# SCH_wordclocksmall_2023-02-03.net
KiCad netlist of a schematic drawn in EasyEDA
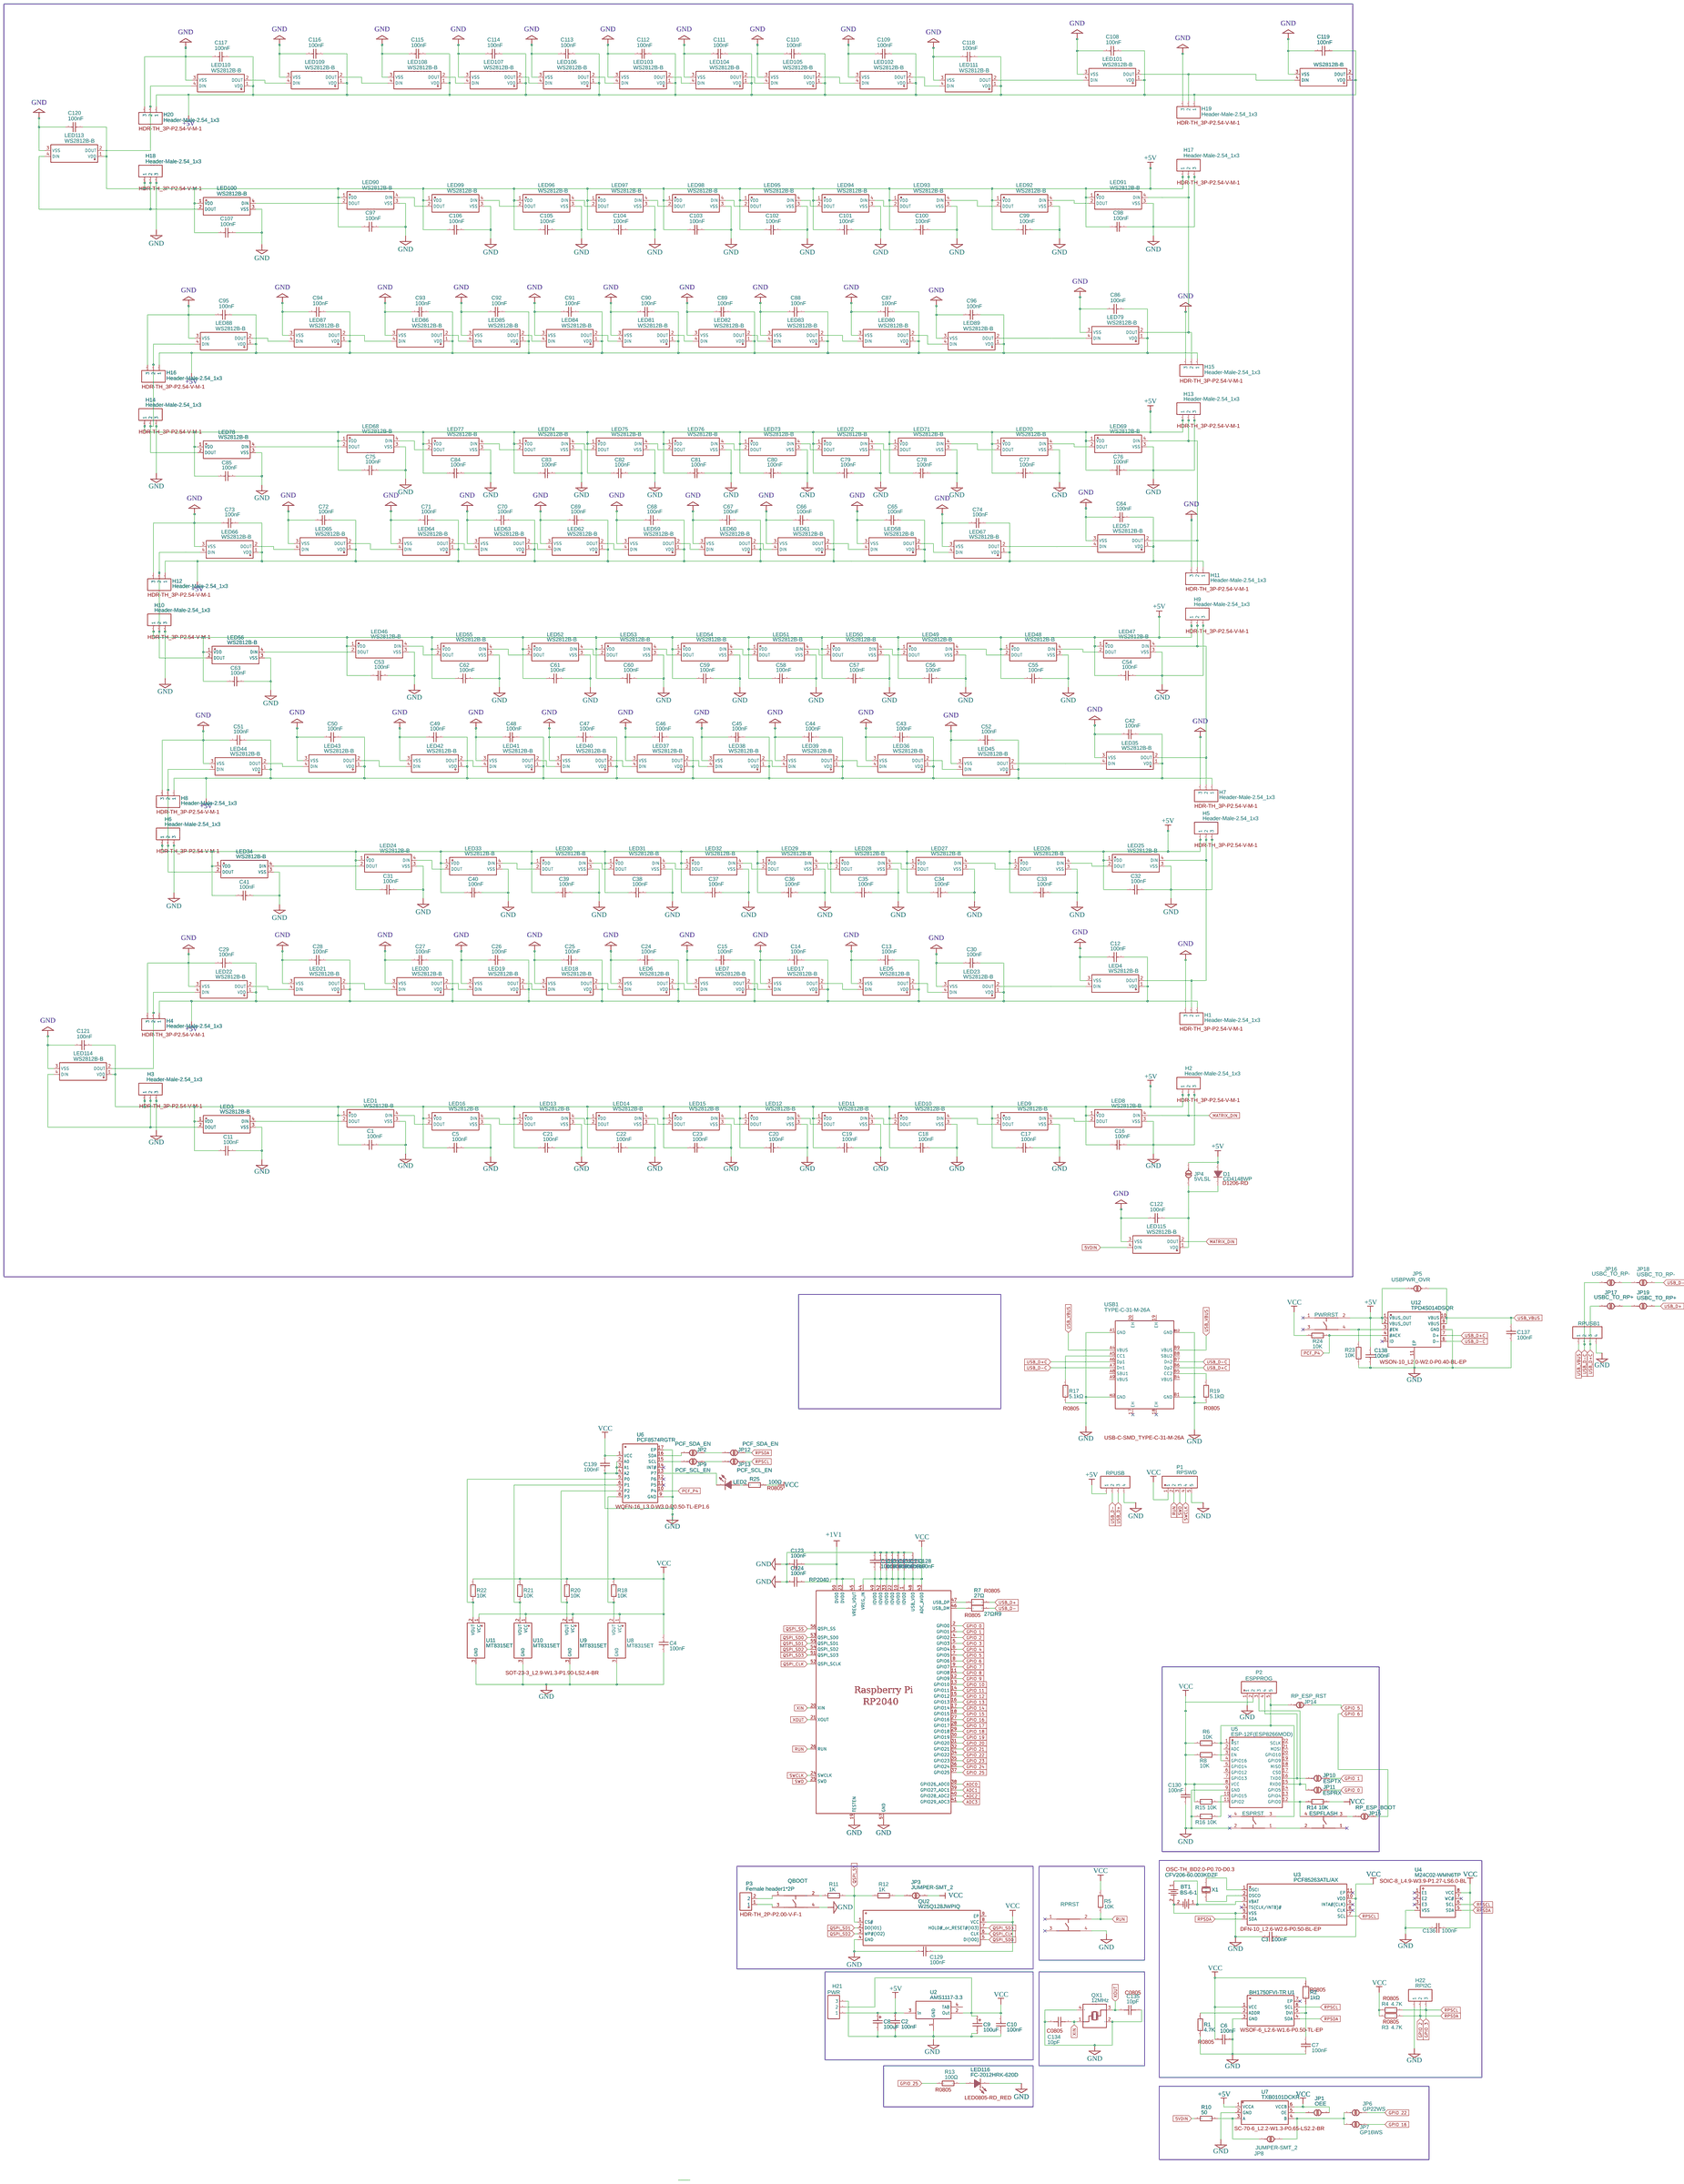
[diagram p0: schematic sheet]

(export (version "E")
  (design (tool "Eeschema 10.0.6"))
  (components
    (comp (ref "BT1")
      (value "BS-6-1")
      (fields (field (name "BOM_Supplier Part") "C969909"))
      (libsource (lib "") (part "BS-6-1_1"))
    )
    (comp (ref "BT2")
      (value "BS-6-1")
      (fields (field (name "BOM_Supplier Part") "C969909"))
      (libsource (lib "") (part "BS-6-1"))
    )
    (comp (ref "C1")
      (value "100nF")
      (fields
        (field (name "BOM_Manufacturer Part") "CC0805KRX7R9BB104")
        (field (name "BOM_Supplier Part") "C49678")
      )
      (libsource (lib "") (part "CC0805KRX7R9BB104_1"))
    )
    (comp (ref "C2")
      (value "100nF")
      (fields
        (field (name "BOM_Manufacturer Part") "CC0805KRX7R9BB104")
        (field (name "BOM_Supplier Part") "C49678")
      )
      (libsource (lib "") (part "CC0805KRX7R9BB104_3"))
    )
    (comp (ref "C3")
      (value "100nF")
      (fields
        (field (name "BOM_Manufacturer Part") "CC0805KRX7R9BB104")
        (field (name "BOM_Supplier Part") "C49678")
      )
      (libsource (lib "") (part "CC0805KRX7R9BB104"))
    )
    (comp (ref "C4")
      (value "100nF")
      (fields
        (field (name "BOM_Manufacturer Part") "CC0805KRX7R9BB104")
        (field (name "BOM_Supplier Part") "C49678")
      )
      (libsource (lib "") (part "CC0805KRX7R9BB104_2"))
    )
    (comp (ref "C5")
      (value "100nF")
      (fields
        (field (name "BOM_Manufacturer Part") "CC0805KRX7R9BB104")
        (field (name "BOM_Supplier Part") "C49678")
      )
      (libsource (lib "") (part "CC0805KRX7R9BB104_1"))
    )
    (comp (ref "C6")
      (value "100nF")
      (fields
        (field (name "BOM_Manufacturer Part") "CC0805KRX7R9BB104")
        (field (name "BOM_Supplier Part") "C49678")
      )
      (libsource (lib "") (part "CC0805KRX7R9BB104"))
    )
    (comp (ref "C7")
      (value "100nF")
      (fields
        (field (name "BOM_Manufacturer Part") "CC0805KRX7R9BB104")
        (field (name "BOM_Supplier Part") "C49678")
      )
      (libsource (lib "") (part "CC0805KRX7R9BB104_2"))
    )
    (comp (ref "C8")
      (value "100uF")
      (fields
        (field (name "BOM_Manufacturer Part") "TAJB107K006RNJ")
        (field (name "BOM_Supplier Part") "C16133")
      )
      (libsource (lib "") (part "TAJB107K006RNJ"))
    )
    (comp (ref "C9")
      (value "100uF")
      (fields
        (field (name "BOM_Manufacturer Part") "TAJB107K006RNJ")
        (field (name "BOM_Supplier Part") "C16133")
      )
      (libsource (lib "") (part "TAJB107K006RNJ"))
    )
    (comp (ref "C10")
      (value "100nF")
      (fields
        (field (name "BOM_Manufacturer Part") "CC0805KRX7R9BB104")
        (field (name "BOM_Supplier Part") "C49678")
      )
      (libsource (lib "") (part "CC0805KRX7R9BB104_3"))
    )
    (comp (ref "C11")
      (value "100nF")
      (fields
        (field (name "BOM_Manufacturer Part") "CC0805KRX7R9BB104")
        (field (name "BOM_Supplier Part") "C49678")
      )
      (libsource (lib "") (part "CC0805KRX7R9BB104_1"))
    )
    (comp (ref "C12")
      (value "100nF")
      (fields
        (field (name "BOM_Manufacturer Part") "CC0805KRX7R9BB104")
        (field (name "BOM_Supplier Part") "C49678")
      )
      (libsource (lib "") (part "CC0805KRX7R9BB104"))
    )
    (comp (ref "C13")
      (value "100nF")
      (fields
        (field (name "BOM_Manufacturer Part") "CC0805KRX7R9BB104")
        (field (name "BOM_Supplier Part") "C49678")
      )
      (libsource (lib "") (part "CC0805KRX7R9BB104"))
    )
    (comp (ref "C14")
      (value "100nF")
      (fields
        (field (name "BOM_Manufacturer Part") "CC0805KRX7R9BB104")
        (field (name "BOM_Supplier Part") "C49678")
      )
      (libsource (lib "") (part "CC0805KRX7R9BB104"))
    )
    (comp (ref "C15")
      (value "100nF")
      (fields
        (field (name "BOM_Manufacturer Part") "CC0805KRX7R9BB104")
        (field (name "BOM_Supplier Part") "C49678")
      )
      (libsource (lib "") (part "CC0805KRX7R9BB104"))
    )
    (comp (ref "C16")
      (value "100nF")
      (fields
        (field (name "BOM_Manufacturer Part") "CC0805KRX7R9BB104")
        (field (name "BOM_Supplier Part") "C49678")
      )
      (libsource (lib "") (part "CC0805KRX7R9BB104_1"))
    )
    (comp (ref "C17")
      (value "100nF")
      (fields
        (field (name "BOM_Manufacturer Part") "CC0805KRX7R9BB104")
        (field (name "BOM_Supplier Part") "C49678")
      )
      (libsource (lib "") (part "CC0805KRX7R9BB104_1"))
    )
    (comp (ref "C18")
      (value "100nF")
      (fields
        (field (name "BOM_Manufacturer Part") "CC0805KRX7R9BB104")
        (field (name "BOM_Supplier Part") "C49678")
      )
      (libsource (lib "") (part "CC0805KRX7R9BB104_1"))
    )
    (comp (ref "C19")
      (value "100nF")
      (fields
        (field (name "BOM_Manufacturer Part") "CC0805KRX7R9BB104")
        (field (name "BOM_Supplier Part") "C49678")
      )
      (libsource (lib "") (part "CC0805KRX7R9BB104_1"))
    )
    (comp (ref "C20")
      (value "100nF")
      (fields
        (field (name "BOM_Manufacturer Part") "CC0805KRX7R9BB104")
        (field (name "BOM_Supplier Part") "C49678")
      )
      (libsource (lib "") (part "CC0805KRX7R9BB104_1"))
    )
    (comp (ref "C21")
      (value "100nF")
      (fields
        (field (name "BOM_Manufacturer Part") "CC0805KRX7R9BB104")
        (field (name "BOM_Supplier Part") "C49678")
      )
      (libsource (lib "") (part "CC0805KRX7R9BB104_1"))
    )
    (comp (ref "C22")
      (value "100nF")
      (fields
        (field (name "BOM_Manufacturer Part") "CC0805KRX7R9BB104")
        (field (name "BOM_Supplier Part") "C49678")
      )
      (libsource (lib "") (part "CC0805KRX7R9BB104_1"))
    )
    (comp (ref "C23")
      (value "100nF")
      (fields
        (field (name "BOM_Manufacturer Part") "CC0805KRX7R9BB104")
        (field (name "BOM_Supplier Part") "C49678")
      )
      (libsource (lib "") (part "CC0805KRX7R9BB104_1"))
    )
    (comp (ref "C24")
      (value "100nF")
      (fields
        (field (name "BOM_Manufacturer Part") "CC0805KRX7R9BB104")
        (field (name "BOM_Supplier Part") "C49678")
      )
      (libsource (lib "") (part "CC0805KRX7R9BB104"))
    )
    (comp (ref "C25")
      (value "100nF")
      (fields
        (field (name "BOM_Manufacturer Part") "CC0805KRX7R9BB104")
        (field (name "BOM_Supplier Part") "C49678")
      )
      (libsource (lib "") (part "CC0805KRX7R9BB104"))
    )
    (comp (ref "C26")
      (value "100nF")
      (fields
        (field (name "BOM_Manufacturer Part") "CC0805KRX7R9BB104")
        (field (name "BOM_Supplier Part") "C49678")
      )
      (libsource (lib "") (part "CC0805KRX7R9BB104"))
    )
    (comp (ref "C27")
      (value "100nF")
      (fields
        (field (name "BOM_Manufacturer Part") "CC0805KRX7R9BB104")
        (field (name "BOM_Supplier Part") "C49678")
      )
      (libsource (lib "") (part "CC0805KRX7R9BB104"))
    )
    (comp (ref "C28")
      (value "100nF")
      (fields
        (field (name "BOM_Manufacturer Part") "CC0805KRX7R9BB104")
        (field (name "BOM_Supplier Part") "C49678")
      )
      (libsource (lib "") (part "CC0805KRX7R9BB104"))
    )
    (comp (ref "C29")
      (value "100nF")
      (fields
        (field (name "BOM_Manufacturer Part") "CC0805KRX7R9BB104")
        (field (name "BOM_Supplier Part") "C49678")
      )
      (libsource (lib "") (part "CC0805KRX7R9BB104"))
    )
    (comp (ref "C30")
      (value "100nF")
      (fields
        (field (name "BOM_Manufacturer Part") "CC0805KRX7R9BB104")
        (field (name "BOM_Supplier Part") "C49678")
      )
      (libsource (lib "") (part "CC0805KRX7R9BB104"))
    )
    (comp (ref "C31")
      (value "100nF")
      (fields
        (field (name "BOM_Manufacturer Part") "CC0805KRX7R9BB104")
        (field (name "BOM_Supplier Part") "C49678")
      )
      (libsource (lib "") (part "CC0805KRX7R9BB104_1"))
    )
    (comp (ref "C32")
      (value "100nF")
      (fields
        (field (name "BOM_Manufacturer Part") "CC0805KRX7R9BB104")
        (field (name "BOM_Supplier Part") "C49678")
      )
      (libsource (lib "") (part "CC0805KRX7R9BB104_1"))
    )
    (comp (ref "C33")
      (value "100nF")
      (fields
        (field (name "BOM_Manufacturer Part") "CC0805KRX7R9BB104")
        (field (name "BOM_Supplier Part") "C49678")
      )
      (libsource (lib "") (part "CC0805KRX7R9BB104_1"))
    )
    (comp (ref "C34")
      (value "100nF")
      (fields
        (field (name "BOM_Manufacturer Part") "CC0805KRX7R9BB104")
        (field (name "BOM_Supplier Part") "C49678")
      )
      (libsource (lib "") (part "CC0805KRX7R9BB104_1"))
    )
    (comp (ref "C35")
      (value "100nF")
      (fields
        (field (name "BOM_Manufacturer Part") "CC0805KRX7R9BB104")
        (field (name "BOM_Supplier Part") "C49678")
      )
      (libsource (lib "") (part "CC0805KRX7R9BB104_1"))
    )
    (comp (ref "C36")
      (value "100nF")
      (fields
        (field (name "BOM_Manufacturer Part") "CC0805KRX7R9BB104")
        (field (name "BOM_Supplier Part") "C49678")
      )
      (libsource (lib "") (part "CC0805KRX7R9BB104_1"))
    )
    (comp (ref "C37")
      (value "100nF")
      (fields
        (field (name "BOM_Manufacturer Part") "CC0805KRX7R9BB104")
        (field (name "BOM_Supplier Part") "C49678")
      )
      (libsource (lib "") (part "CC0805KRX7R9BB104_1"))
    )
    (comp (ref "C38")
      (value "100nF")
      (fields
        (field (name "BOM_Manufacturer Part") "CC0805KRX7R9BB104")
        (field (name "BOM_Supplier Part") "C49678")
      )
      (libsource (lib "") (part "CC0805KRX7R9BB104_1"))
    )
    (comp (ref "C39")
      (value "100nF")
      (fields
        (field (name "BOM_Manufacturer Part") "CC0805KRX7R9BB104")
        (field (name "BOM_Supplier Part") "C49678")
      )
      (libsource (lib "") (part "CC0805KRX7R9BB104_1"))
    )
    (comp (ref "C40")
      (value "100nF")
      (fields
        (field (name "BOM_Manufacturer Part") "CC0805KRX7R9BB104")
        (field (name "BOM_Supplier Part") "C49678")
      )
      (libsource (lib "") (part "CC0805KRX7R9BB104_1"))
    )
    (comp (ref "C41")
      (value "100nF")
      (fields
        (field (name "BOM_Manufacturer Part") "CC0805KRX7R9BB104")
        (field (name "BOM_Supplier Part") "C49678")
      )
      (libsource (lib "") (part "CC0805KRX7R9BB104_1"))
    )
    (comp (ref "C42")
      (value "100nF")
      (fields
        (field (name "BOM_Manufacturer Part") "CC0805KRX7R9BB104")
        (field (name "BOM_Supplier Part") "C49678")
      )
      (libsource (lib "") (part "CC0805KRX7R9BB104"))
    )
    (comp (ref "C43")
      (value "100nF")
      (fields
        (field (name "BOM_Manufacturer Part") "CC0805KRX7R9BB104")
        (field (name "BOM_Supplier Part") "C49678")
      )
      (libsource (lib "") (part "CC0805KRX7R9BB104"))
    )
    (comp (ref "C44")
      (value "100nF")
      (fields
        (field (name "BOM_Manufacturer Part") "CC0805KRX7R9BB104")
        (field (name "BOM_Supplier Part") "C49678")
      )
      (libsource (lib "") (part "CC0805KRX7R9BB104"))
    )
    (comp (ref "C45")
      (value "100nF")
      (fields
        (field (name "BOM_Manufacturer Part") "CC0805KRX7R9BB104")
        (field (name "BOM_Supplier Part") "C49678")
      )
      (libsource (lib "") (part "CC0805KRX7R9BB104"))
    )
    (comp (ref "C46")
      (value "100nF")
      (fields
        (field (name "BOM_Manufacturer Part") "CC0805KRX7R9BB104")
        (field (name "BOM_Supplier Part") "C49678")
      )
      (libsource (lib "") (part "CC0805KRX7R9BB104"))
    )
    (comp (ref "C47")
      (value "100nF")
      (fields
        (field (name "BOM_Manufacturer Part") "CC0805KRX7R9BB104")
        (field (name "BOM_Supplier Part") "C49678")
      )
      (libsource (lib "") (part "CC0805KRX7R9BB104"))
    )
    (comp (ref "C48")
      (value "100nF")
      (fields
        (field (name "BOM_Manufacturer Part") "CC0805KRX7R9BB104")
        (field (name "BOM_Supplier Part") "C49678")
      )
      (libsource (lib "") (part "CC0805KRX7R9BB104"))
    )
    (comp (ref "C49")
      (value "100nF")
      (fields
        (field (name "BOM_Manufacturer Part") "CC0805KRX7R9BB104")
        (field (name "BOM_Supplier Part") "C49678")
      )
      (libsource (lib "") (part "CC0805KRX7R9BB104"))
    )
    (comp (ref "C50")
      (value "100nF")
      (fields
        (field (name "BOM_Manufacturer Part") "CC0805KRX7R9BB104")
        (field (name "BOM_Supplier Part") "C49678")
      )
      (libsource (lib "") (part "CC0805KRX7R9BB104"))
    )
    (comp (ref "C51")
      (value "100nF")
      (fields
        (field (name "BOM_Manufacturer Part") "CC0805KRX7R9BB104")
        (field (name "BOM_Supplier Part") "C49678")
      )
      (libsource (lib "") (part "CC0805KRX7R9BB104"))
    )
    (comp (ref "C52")
      (value "100nF")
      (fields
        (field (name "BOM_Manufacturer Part") "CC0805KRX7R9BB104")
        (field (name "BOM_Supplier Part") "C49678")
      )
      (libsource (lib "") (part "CC0805KRX7R9BB104"))
    )
    (comp (ref "C53")
      (value "100nF")
      (fields
        (field (name "BOM_Manufacturer Part") "CC0805KRX7R9BB104")
        (field (name "BOM_Supplier Part") "C49678")
      )
      (libsource (lib "") (part "CC0805KRX7R9BB104_1"))
    )
    (comp (ref "C54")
      (value "100nF")
      (fields
        (field (name "BOM_Manufacturer Part") "CC0805KRX7R9BB104")
        (field (name "BOM_Supplier Part") "C49678")
      )
      (libsource (lib "") (part "CC0805KRX7R9BB104_1"))
    )
    (comp (ref "C55")
      (value "100nF")
      (fields
        (field (name "BOM_Manufacturer Part") "CC0805KRX7R9BB104")
        (field (name "BOM_Supplier Part") "C49678")
      )
      (libsource (lib "") (part "CC0805KRX7R9BB104_1"))
    )
    (comp (ref "C56")
      (value "100nF")
      (fields
        (field (name "BOM_Manufacturer Part") "CC0805KRX7R9BB104")
        (field (name "BOM_Supplier Part") "C49678")
      )
      (libsource (lib "") (part "CC0805KRX7R9BB104_1"))
    )
    (comp (ref "C57")
      (value "100nF")
      (fields
        (field (name "BOM_Manufacturer Part") "CC0805KRX7R9BB104")
        (field (name "BOM_Supplier Part") "C49678")
      )
      (libsource (lib "") (part "CC0805KRX7R9BB104_1"))
    )
    (comp (ref "C58")
      (value "100nF")
      (fields
        (field (name "BOM_Manufacturer Part") "CC0805KRX7R9BB104")
        (field (name "BOM_Supplier Part") "C49678")
      )
      (libsource (lib "") (part "CC0805KRX7R9BB104_1"))
    )
    (comp (ref "C59")
      (value "100nF")
      (fields
        (field (name "BOM_Manufacturer Part") "CC0805KRX7R9BB104")
        (field (name "BOM_Supplier Part") "C49678")
      )
      (libsource (lib "") (part "CC0805KRX7R9BB104_1"))
    )
    (comp (ref "C60")
      (value "100nF")
      (fields
        (field (name "BOM_Manufacturer Part") "CC0805KRX7R9BB104")
        (field (name "BOM_Supplier Part") "C49678")
      )
      (libsource (lib "") (part "CC0805KRX7R9BB104_1"))
    )
    (comp (ref "C61")
      (value "100nF")
      (fields
        (field (name "BOM_Manufacturer Part") "CC0805KRX7R9BB104")
        (field (name "BOM_Supplier Part") "C49678")
      )
      (libsource (lib "") (part "CC0805KRX7R9BB104_1"))
    )
    (comp (ref "C62")
      (value "100nF")
      (fields
        (field (name "BOM_Manufacturer Part") "CC0805KRX7R9BB104")
        (field (name "BOM_Supplier Part") "C49678")
      )
      (libsource (lib "") (part "CC0805KRX7R9BB104_1"))
    )
    (comp (ref "C63")
      (value "100nF")
      (fields
        (field (name "BOM_Manufacturer Part") "CC0805KRX7R9BB104")
        (field (name "BOM_Supplier Part") "C49678")
      )
      (libsource (lib "") (part "CC0805KRX7R9BB104_1"))
    )
    (comp (ref "C64")
      (value "100nF")
      (fields
        (field (name "BOM_Manufacturer Part") "CC0805KRX7R9BB104")
        (field (name "BOM_Supplier Part") "C49678")
      )
      (libsource (lib "") (part "CC0805KRX7R9BB104"))
    )
    (comp (ref "C65")
      (value "100nF")
      (fields
        (field (name "BOM_Manufacturer Part") "CC0805KRX7R9BB104")
        (field (name "BOM_Supplier Part") "C49678")
      )
      (libsource (lib "") (part "CC0805KRX7R9BB104"))
    )
    (comp (ref "C66")
      (value "100nF")
      (fields
        (field (name "BOM_Manufacturer Part") "CC0805KRX7R9BB104")
        (field (name "BOM_Supplier Part") "C49678")
      )
      (libsource (lib "") (part "CC0805KRX7R9BB104"))
    )
    (comp (ref "C67")
      (value "100nF")
      (fields
        (field (name "BOM_Manufacturer Part") "CC0805KRX7R9BB104")
        (field (name "BOM_Supplier Part") "C49678")
      )
      (libsource (lib "") (part "CC0805KRX7R9BB104"))
    )
    (comp (ref "C68")
      (value "100nF")
      (fields
        (field (name "BOM_Manufacturer Part") "CC0805KRX7R9BB104")
        (field (name "BOM_Supplier Part") "C49678")
      )
      (libsource (lib "") (part "CC0805KRX7R9BB104"))
    )
    (comp (ref "C69")
      (value "100nF")
      (fields
        (field (name "BOM_Manufacturer Part") "CC0805KRX7R9BB104")
        (field (name "BOM_Supplier Part") "C49678")
      )
      (libsource (lib "") (part "CC0805KRX7R9BB104"))
    )
    (comp (ref "C70")
      (value "100nF")
      (fields
        (field (name "BOM_Manufacturer Part") "CC0805KRX7R9BB104")
        (field (name "BOM_Supplier Part") "C49678")
      )
      (libsource (lib "") (part "CC0805KRX7R9BB104"))
    )
    (comp (ref "C71")
      (value "100nF")
      (fields
        (field (name "BOM_Manufacturer Part") "CC0805KRX7R9BB104")
        (field (name "BOM_Supplier Part") "C49678")
      )
      (libsource (lib "") (part "CC0805KRX7R9BB104"))
    )
    (comp (ref "C72")
      (value "100nF")
      (fields
        (field (name "BOM_Manufacturer Part") "CC0805KRX7R9BB104")
        (field (name "BOM_Supplier Part") "C49678")
      )
      (libsource (lib "") (part "CC0805KRX7R9BB104"))
    )
    (comp (ref "C73")
      (value "100nF")
      (fields
        (field (name "BOM_Manufacturer Part") "CC0805KRX7R9BB104")
        (field (name "BOM_Supplier Part") "C49678")
      )
      (libsource (lib "") (part "CC0805KRX7R9BB104"))
    )
    (comp (ref "C74")
      (value "100nF")
      (fields
        (field (name "BOM_Manufacturer Part") "CC0805KRX7R9BB104")
        (field (name "BOM_Supplier Part") "C49678")
      )
      (libsource (lib "") (part "CC0805KRX7R9BB104"))
    )
    (comp (ref "C75")
      (value "100nF")
      (fields
        (field (name "BOM_Manufacturer Part") "CC0805KRX7R9BB104")
        (field (name "BOM_Supplier Part") "C49678")
      )
      (libsource (lib "") (part "CC0805KRX7R9BB104_1"))
    )
    (comp (ref "C76")
      (value "100nF")
      (fields
        (field (name "BOM_Manufacturer Part") "CC0805KRX7R9BB104")
        (field (name "BOM_Supplier Part") "C49678")
      )
      (libsource (lib "") (part "CC0805KRX7R9BB104_1"))
    )
    (comp (ref "C77")
      (value "100nF")
      (fields
        (field (name "BOM_Manufacturer Part") "CC0805KRX7R9BB104")
        (field (name "BOM_Supplier Part") "C49678")
      )
      (libsource (lib "") (part "CC0805KRX7R9BB104_1"))
    )
    (comp (ref "C78")
      (value "100nF")
      (fields
        (field (name "BOM_Manufacturer Part") "CC0805KRX7R9BB104")
        (field (name "BOM_Supplier Part") "C49678")
      )
      (libsource (lib "") (part "CC0805KRX7R9BB104_1"))
    )
    (comp (ref "C79")
      (value "100nF")
      (fields
        (field (name "BOM_Manufacturer Part") "CC0805KRX7R9BB104")
        (field (name "BOM_Supplier Part") "C49678")
      )
      (libsource (lib "") (part "CC0805KRX7R9BB104_1"))
    )
    (comp (ref "C80")
      (value "100nF")
      (fields
        (field (name "BOM_Manufacturer Part") "CC0805KRX7R9BB104")
        (field (name "BOM_Supplier Part") "C49678")
      )
      (libsource (lib "") (part "CC0805KRX7R9BB104_1"))
    )
    (comp (ref "C81")
      (value "100nF")
      (fields
        (field (name "BOM_Manufacturer Part") "CC0805KRX7R9BB104")
        (field (name "BOM_Supplier Part") "C49678")
      )
      (libsource (lib "") (part "CC0805KRX7R9BB104_1"))
    )
    (comp (ref "C82")
      (value "100nF")
      (fields
        (field (name "BOM_Manufacturer Part") "CC0805KRX7R9BB104")
        (field (name "BOM_Supplier Part") "C49678")
      )
      (libsource (lib "") (part "CC0805KRX7R9BB104_1"))
    )
    (comp (ref "C83")
      (value "100nF")
      (fields
        (field (name "BOM_Manufacturer Part") "CC0805KRX7R9BB104")
        (field (name "BOM_Supplier Part") "C49678")
      )
      (libsource (lib "") (part "CC0805KRX7R9BB104_1"))
    )
    (comp (ref "C84")
      (value "100nF")
      (fields
        (field (name "BOM_Manufacturer Part") "CC0805KRX7R9BB104")
        (field (name "BOM_Supplier Part") "C49678")
      )
      (libsource (lib "") (part "CC0805KRX7R9BB104_1"))
    )
    (comp (ref "C85")
      (value "100nF")
      (fields
        (field (name "BOM_Manufacturer Part") "CC0805KRX7R9BB104")
        (field (name "BOM_Supplier Part") "C49678")
      )
      (libsource (lib "") (part "CC0805KRX7R9BB104_1"))
    )
    (comp (ref "C86")
      (value "100nF")
      (fields
        (field (name "BOM_Manufacturer Part") "CC0805KRX7R9BB104")
        (field (name "BOM_Supplier Part") "C49678")
      )
      (libsource (lib "") (part "CC0805KRX7R9BB104"))
    )
    (comp (ref "C87")
      (value "100nF")
      (fields
        (field (name "BOM_Manufacturer Part") "CC0805KRX7R9BB104")
        (field (name "BOM_Supplier Part") "C49678")
      )
      (libsource (lib "") (part "CC0805KRX7R9BB104"))
    )
    (comp (ref "C88")
      (value "100nF")
      (fields
        (field (name "BOM_Manufacturer Part") "CC0805KRX7R9BB104")
        (field (name "BOM_Supplier Part") "C49678")
      )
      (libsource (lib "") (part "CC0805KRX7R9BB104"))
    )
    (comp (ref "C89")
      (value "100nF")
      (fields
        (field (name "BOM_Manufacturer Part") "CC0805KRX7R9BB104")
        (field (name "BOM_Supplier Part") "C49678")
      )
      (libsource (lib "") (part "CC0805KRX7R9BB104"))
    )
    (comp (ref "C90")
      (value "100nF")
      (fields
        (field (name "BOM_Manufacturer Part") "CC0805KRX7R9BB104")
        (field (name "BOM_Supplier Part") "C49678")
      )
      (libsource (lib "") (part "CC0805KRX7R9BB104"))
    )
    (comp (ref "C91")
      (value "100nF")
      (fields
        (field (name "BOM_Manufacturer Part") "CC0805KRX7R9BB104")
        (field (name "BOM_Supplier Part") "C49678")
      )
      (libsource (lib "") (part "CC0805KRX7R9BB104"))
    )
    (comp (ref "C92")
      (value "100nF")
      (fields
        (field (name "BOM_Manufacturer Part") "CC0805KRX7R9BB104")
        (field (name "BOM_Supplier Part") "C49678")
      )
      (libsource (lib "") (part "CC0805KRX7R9BB104"))
    )
    (comp (ref "C93")
      (value "100nF")
      (fields
        (field (name "BOM_Manufacturer Part") "CC0805KRX7R9BB104")
        (field (name "BOM_Supplier Part") "C49678")
      )
      (libsource (lib "") (part "CC0805KRX7R9BB104"))
    )
    (comp (ref "C94")
      (value "100nF")
      (fields
        (field (name "BOM_Manufacturer Part") "CC0805KRX7R9BB104")
        (field (name "BOM_Supplier Part") "C49678")
      )
      (libsource (lib "") (part "CC0805KRX7R9BB104"))
    )
    (comp (ref "C95")
      (value "100nF")
      (fields
        (field (name "BOM_Manufacturer Part") "CC0805KRX7R9BB104")
        (field (name "BOM_Supplier Part") "C49678")
      )
      (libsource (lib "") (part "CC0805KRX7R9BB104"))
    )
    (comp (ref "C96")
      (value "100nF")
      (fields
        (field (name "BOM_Manufacturer Part") "CC0805KRX7R9BB104")
        (field (name "BOM_Supplier Part") "C49678")
      )
      (libsource (lib "") (part "CC0805KRX7R9BB104"))
    )
    (comp (ref "C97")
      (value "100nF")
      (fields
        (field (name "BOM_Manufacturer Part") "CC0805KRX7R9BB104")
        (field (name "BOM_Supplier Part") "C49678")
      )
      (libsource (lib "") (part "CC0805KRX7R9BB104_1"))
    )
    (comp (ref "C98")
      (value "100nF")
      (fields
        (field (name "BOM_Manufacturer Part") "CC0805KRX7R9BB104")
        (field (name "BOM_Supplier Part") "C49678")
      )
      (libsource (lib "") (part "CC0805KRX7R9BB104_1"))
    )
    (comp (ref "C99")
      (value "100nF")
      (fields
        (field (name "BOM_Manufacturer Part") "CC0805KRX7R9BB104")
        (field (name "BOM_Supplier Part") "C49678")
      )
      (libsource (lib "") (part "CC0805KRX7R9BB104_1"))
    )
    (comp (ref "C100")
      (value "100nF")
      (fields
        (field (name "BOM_Manufacturer Part") "CC0805KRX7R9BB104")
        (field (name "BOM_Supplier Part") "C49678")
      )
      (libsource (lib "") (part "CC0805KRX7R9BB104_1"))
    )
    (comp (ref "C101")
      (value "100nF")
      (fields
        (field (name "BOM_Manufacturer Part") "CC0805KRX7R9BB104")
        (field (name "BOM_Supplier Part") "C49678")
      )
      (libsource (lib "") (part "CC0805KRX7R9BB104_1"))
    )
    (comp (ref "C102")
      (value "100nF")
      (fields
        (field (name "BOM_Manufacturer Part") "CC0805KRX7R9BB104")
        (field (name "BOM_Supplier Part") "C49678")
      )
      (libsource (lib "") (part "CC0805KRX7R9BB104_1"))
    )
    (comp (ref "C103")
      (value "100nF")
      (fields
        (field (name "BOM_Manufacturer Part") "CC0805KRX7R9BB104")
        (field (name "BOM_Supplier Part") "C49678")
      )
      (libsource (lib "") (part "CC0805KRX7R9BB104_1"))
    )
    (comp (ref "C104")
      (value "100nF")
      (fields
        (field (name "BOM_Manufacturer Part") "CC0805KRX7R9BB104")
        (field (name "BOM_Supplier Part") "C49678")
      )
      (libsource (lib "") (part "CC0805KRX7R9BB104_1"))
    )
    (comp (ref "C105")
      (value "100nF")
      (fields
        (field (name "BOM_Manufacturer Part") "CC0805KRX7R9BB104")
        (field (name "BOM_Supplier Part") "C49678")
      )
      (libsource (lib "") (part "CC0805KRX7R9BB104_1"))
    )
    (comp (ref "C106")
      (value "100nF")
      (fields
        (field (name "BOM_Manufacturer Part") "CC0805KRX7R9BB104")
        (field (name "BOM_Supplier Part") "C49678")
      )
      (libsource (lib "") (part "CC0805KRX7R9BB104_1"))
    )
    (comp (ref "C107")
      (value "100nF")
      (fields
        (field (name "BOM_Manufacturer Part") "CC0805KRX7R9BB104")
        (field (name "BOM_Supplier Part") "C49678")
      )
      (libsource (lib "") (part "CC0805KRX7R9BB104_1"))
    )
    (comp (ref "C108")
      (value "100nF")
      (fields
        (field (name "BOM_Manufacturer Part") "CC0805KRX7R9BB104")
        (field (name "BOM_Supplier Part") "C49678")
      )
      (libsource (lib "") (part "CC0805KRX7R9BB104"))
    )
    (comp (ref "C109")
      (value "100nF")
      (fields
        (field (name "BOM_Manufacturer Part") "CC0805KRX7R9BB104")
        (field (name "BOM_Supplier Part") "C49678")
      )
      (libsource (lib "") (part "CC0805KRX7R9BB104"))
    )
    (comp (ref "C110")
      (value "100nF")
      (fields
        (field (name "BOM_Manufacturer Part") "CC0805KRX7R9BB104")
        (field (name "BOM_Supplier Part") "C49678")
      )
      (libsource (lib "") (part "CC0805KRX7R9BB104"))
    )
    (comp (ref "C111")
      (value "100nF")
      (fields
        (field (name "BOM_Manufacturer Part") "CC0805KRX7R9BB104")
        (field (name "BOM_Supplier Part") "C49678")
      )
      (libsource (lib "") (part "CC0805KRX7R9BB104"))
    )
    (comp (ref "C112")
      (value "100nF")
      (fields
        (field (name "BOM_Manufacturer Part") "CC0805KRX7R9BB104")
        (field (name "BOM_Supplier Part") "C49678")
      )
      (libsource (lib "") (part "CC0805KRX7R9BB104"))
    )
    (comp (ref "C113")
      (value "100nF")
      (fields
        (field (name "BOM_Manufacturer Part") "CC0805KRX7R9BB104")
        (field (name "BOM_Supplier Part") "C49678")
      )
      (libsource (lib "") (part "CC0805KRX7R9BB104"))
    )
    (comp (ref "C114")
      (value "100nF")
      (fields
        (field (name "BOM_Manufacturer Part") "CC0805KRX7R9BB104")
        (field (name "BOM_Supplier Part") "C49678")
      )
      (libsource (lib "") (part "CC0805KRX7R9BB104"))
    )
    (comp (ref "C115")
      (value "100nF")
      (fields
        (field (name "BOM_Manufacturer Part") "CC0805KRX7R9BB104")
        (field (name "BOM_Supplier Part") "C49678")
      )
      (libsource (lib "") (part "CC0805KRX7R9BB104"))
    )
    (comp (ref "C116")
      (value "100nF")
      (fields
        (field (name "BOM_Manufacturer Part") "CC0805KRX7R9BB104")
        (field (name "BOM_Supplier Part") "C49678")
      )
      (libsource (lib "") (part "CC0805KRX7R9BB104"))
    )
    (comp (ref "C117")
      (value "100nF")
      (fields
        (field (name "BOM_Manufacturer Part") "CC0805KRX7R9BB104")
        (field (name "BOM_Supplier Part") "C49678")
      )
      (libsource (lib "") (part "CC0805KRX7R9BB104"))
    )
    (comp (ref "C118")
      (value "100nF")
      (fields
        (field (name "BOM_Manufacturer Part") "CC0805KRX7R9BB104")
        (field (name "BOM_Supplier Part") "C49678")
      )
      (libsource (lib "") (part "CC0805KRX7R9BB104"))
    )
    (comp (ref "C119")
      (value "100nF")
      (fields
        (field (name "BOM_Manufacturer Part") "CC0805KRX7R9BB104")
        (field (name "BOM_Supplier Part") "C49678")
      )
      (libsource (lib "") (part "CC0805KRX7R9BB104"))
    )
    (comp (ref "C120")
      (value "100nF")
      (fields
        (field (name "BOM_Manufacturer Part") "CC0805KRX7R9BB104")
        (field (name "BOM_Supplier Part") "C49678")
      )
      (libsource (lib "") (part "CC0805KRX7R9BB104"))
    )
    (comp (ref "C121")
      (value "100nF")
      (fields
        (field (name "BOM_Manufacturer Part") "CC0805KRX7R9BB104")
        (field (name "BOM_Supplier Part") "C49678")
      )
      (libsource (lib "") (part "CC0805KRX7R9BB104"))
    )
    (comp (ref "C122")
      (value "100nF")
      (fields
        (field (name "BOM_Manufacturer Part") "CC0805KRX7R9BB104")
        (field (name "BOM_Supplier Part") "C49678")
      )
      (libsource (lib "") (part "CC0805KRX7R9BB104"))
    )
    (comp (ref "C123")
      (value "100nF")
      (fields
        (field (name "BOM_Manufacturer Part") "CC0805KRX7R9BB104")
        (field (name "BOM_Supplier Part") "C49678")
      )
      (libsource (lib "") (part "CC0805KRX7R9BB104"))
    )
    (comp (ref "C124")
      (value "100nF")
      (fields
        (field (name "BOM_Manufacturer Part") "CC0805KRX7R9BB104")
        (field (name "BOM_Supplier Part") "C49678")
      )
      (libsource (lib "") (part "CC0805KRX7R9BB104"))
    )
    (comp (ref "C125")
      (value "100nF")
      (fields
        (field (name "BOM_Manufacturer Part") "CC0805KRX7R9BB104")
        (field (name "BOM_Supplier Part") "C49678")
      )
      (libsource (lib "") (part "CC0805KRX7R9BB104_2"))
    )
    (comp (ref "C126")
      (value "100nF")
      (fields
        (field (name "BOM_Manufacturer Part") "CC0805KRX7R9BB104")
        (field (name "BOM_Supplier Part") "C49678")
      )
      (libsource (lib "") (part "CC0805KRX7R9BB104_2"))
    )
    (comp (ref "C127")
      (value "100nF")
      (fields
        (field (name "BOM_Manufacturer Part") "CC0805KRX7R9BB104")
        (field (name "BOM_Supplier Part") "C49678")
      )
      (libsource (lib "") (part "CC0805KRX7R9BB104_2"))
    )
    (comp (ref "C128")
      (value "100nF")
      (fields
        (field (name "BOM_Manufacturer Part") "CC0805KRX7R9BB104")
        (field (name "BOM_Supplier Part") "C49678")
      )
      (libsource (lib "") (part "CC0805KRX7R9BB104_2"))
    )
    (comp (ref "C129")
      (value "100nF")
      (fields
        (field (name "BOM_Manufacturer Part") "CC0805KRX7R9BB104")
        (field (name "BOM_Supplier Part") "C49678")
      )
      (libsource (lib "") (part "CC0805KRX7R9BB104"))
    )
    (comp (ref "C130")
      (value "100nF")
      (fields
        (field (name "BOM_Manufacturer Part") "CC0805KRX7R9BB104")
        (field (name "BOM_Supplier Part") "C49678")
      )
      (libsource (lib "") (part "CC0805KRX7R9BB104_2"))
    )
    (comp (ref "C131")
      (value "100nF")
      (fields
        (field (name "BOM_Manufacturer Part") "CC0805KRX7R9BB104")
        (field (name "BOM_Supplier Part") "C49678")
      )
      (libsource (lib "") (part "CC0805KRX7R9BB104_2"))
    )
    (comp (ref "C132")
      (value "100nF")
      (fields
        (field (name "BOM_Manufacturer Part") "CC0805KRX7R9BB104")
        (field (name "BOM_Supplier Part") "C49678")
      )
      (libsource (lib "") (part "CC0805KRX7R9BB104_2"))
    )
    (comp (ref "C133")
      (value "100nF")
      (fields
        (field (name "BOM_Manufacturer Part") "CC0805KRX7R9BB104")
        (field (name "BOM_Supplier Part") "C49678")
      )
      (libsource (lib "") (part "CC0805KRX7R9BB104_2"))
    )
    (comp (ref "C134")
      (value "10pF")
      (fields
        (field (name "BOM_Manufacturer Part") "CL21C100JBANNNC")
        (field (name "BOM_Supplier Part") "C1785")
      )
      (libsource (lib "") (part "CC0805JRNPOYBN100_1"))
    )
    (comp (ref "C135")
      (value "10pF")
      (fields
        (field (name "BOM_Manufacturer Part") "CL21C100JBANNNC")
        (field (name "BOM_Supplier Part") "C1785")
      )
      (libsource (lib "") (part "CC0805JRNPOYBN100"))
    )
    (comp (ref "C136")
      (value "100nF")
      (fields
        (field (name "BOM_Manufacturer Part") "CC0805KRX7R9BB104")
        (field (name "BOM_Supplier Part") "C49678")
      )
      (libsource (lib "") (part "CC0805KRX7R9BB104"))
    )
    (comp (ref "C137")
      (value "100nF")
      (fields
        (field (name "BOM_Manufacturer Part") "CC0805KRX7R9BB104")
        (field (name "BOM_Supplier Part") "C49678")
      )
      (libsource (lib "") (part "CC0805KRX7R9BB104_2"))
    )
    (comp (ref "C138")
      (value "100nF")
      (fields
        (field (name "BOM_Manufacturer Part") "CC0805KRX7R9BB104")
        (field (name "BOM_Supplier Part") "C49678")
      )
      (libsource (lib "") (part "CC0805KRX7R9BB104_2"))
    )
    (comp (ref "C139")
      (value "100nF")
      (fields
        (field (name "BOM_Manufacturer Part") "CC0805KRX7R9BB104")
        (field (name "BOM_Supplier Part") "C49678")
      )
      (libsource (lib "") (part "CC0805KRX7R9BB104_3"))
    )
    (comp (ref "D1")
      (value "CD4148WP")
      (fields (field (name "BOM_Supplier Part") "C109000"))
      (libsource (lib "") (part "CD4148WP"))
    )
    (comp (ref "ESPFLASH")
      (value "PTS810SJM250SMTRLFS")
      (fields (field (name "BOM_Supplier Part") "C116501"))
      (libsource (lib "") (part "PTS810SJM250SMTRLFS_1"))
    )
    (comp (ref "ESPRST")
      (value "PTS810SJM250SMTRLFS")
      (fields (field (name "BOM_Supplier Part") "C116501"))
      (libsource (lib "") (part "PTS810SJM250SMTRLFS"))
    )
    (comp (ref "H1")
      (value "Header-Male-2.54_1x3")
      (fields
        (field (name "BOM_Manufacturer Part") "Header2.54mm 1*3P")
        (field (name "BOM_Supplier Part") "C49257")
      )
      (libsource (lib "") (part "Header-Male-2.54_1x3_8"))
    )
    (comp (ref "H2")
      (value "Header-Male-2.54_1x3")
      (fields
        (field (name "BOM_Manufacturer Part") "Header2.54mm 1*3P")
        (field (name "BOM_Supplier Part") "C49257")
      )
      (libsource (lib "") (part "Header-Male-2.54_1x3_6"))
    )
    (comp (ref "H3")
      (value "Header-Male-2.54_1x3")
      (fields
        (field (name "BOM_Manufacturer Part") "Header2.54mm 1*3P")
        (field (name "BOM_Supplier Part") "C49257")
      )
      (libsource (lib "") (part "Header-Male-2.54_1x3_7"))
    )
    (comp (ref "H4")
      (value "Header-Male-2.54_1x3")
      (fields
        (field (name "BOM_Manufacturer Part") "Header2.54mm 1*3P")
        (field (name "BOM_Supplier Part") "C49257")
      )
      (libsource (lib "") (part "Header-Male-2.54_1x3_8"))
    )
    (comp (ref "H5")
      (value "Header-Male-2.54_1x3")
      (fields
        (field (name "BOM_Manufacturer Part") "Header2.54mm 1*3P")
        (field (name "BOM_Supplier Part") "C49257")
      )
      (libsource (lib "") (part "Header-Male-2.54_1x3_1"))
    )
    (comp (ref "H6")
      (value "Header-Male-2.54_1x3")
      (fields
        (field (name "BOM_Manufacturer Part") "Header2.54mm 1*3P")
        (field (name "BOM_Supplier Part") "C49257")
      )
      (libsource (lib "") (part "Header-Male-2.54_1x3_1"))
    )
    (comp (ref "H7")
      (value "Header-Male-2.54_1x3")
      (fields
        (field (name "BOM_Manufacturer Part") "Header2.54mm 1*3P")
        (field (name "BOM_Supplier Part") "C49257")
      )
      (libsource (lib "") (part "Header-Male-2.54_1x3"))
    )
    (comp (ref "H8")
      (value "Header-Male-2.54_1x3")
      (fields
        (field (name "BOM_Manufacturer Part") "Header2.54mm 1*3P")
        (field (name "BOM_Supplier Part") "C49257")
      )
      (libsource (lib "") (part "Header-Male-2.54_1x3"))
    )
    (comp (ref "H9")
      (value "Header-Male-2.54_1x3")
      (fields
        (field (name "BOM_Manufacturer Part") "Header2.54mm 1*3P")
        (field (name "BOM_Supplier Part") "C49257")
      )
      (libsource (lib "") (part "Header-Male-2.54_1x3_4"))
    )
    (comp (ref "H10")
      (value "Header-Male-2.54_1x3")
      (fields
        (field (name "BOM_Manufacturer Part") "Header2.54mm 1*3P")
        (field (name "BOM_Supplier Part") "C49257")
      )
      (libsource (lib "") (part "Header-Male-2.54_1x3_4"))
    )
    (comp (ref "H11")
      (value "Header-Male-2.54_1x3")
      (fields
        (field (name "BOM_Manufacturer Part") "Header2.54mm 1*3P")
        (field (name "BOM_Supplier Part") "C49257")
      )
      (libsource (lib "") (part "Header-Male-2.54_1x3"))
    )
    (comp (ref "H12")
      (value "Header-Male-2.54_1x3")
      (fields
        (field (name "BOM_Manufacturer Part") "Header2.54mm 1*3P")
        (field (name "BOM_Supplier Part") "C49257")
      )
      (libsource (lib "") (part "Header-Male-2.54_1x3"))
    )
    (comp (ref "H13")
      (value "Header-Male-2.54_1x3")
      (fields
        (field (name "BOM_Manufacturer Part") "Header2.54mm 1*3P")
        (field (name "BOM_Supplier Part") "C49257")
      )
      (libsource (lib "") (part "Header-Male-2.54_1x3_4"))
    )
    (comp (ref "H14")
      (value "Header-Male-2.54_1x3")
      (fields
        (field (name "BOM_Manufacturer Part") "Header2.54mm 1*3P")
        (field (name "BOM_Supplier Part") "C49257")
      )
      (libsource (lib "") (part "Header-Male-2.54_1x3_4"))
    )
    (comp (ref "H15")
      (value "Header-Male-2.54_1x3")
      (fields
        (field (name "BOM_Manufacturer Part") "Header2.54mm 1*3P")
        (field (name "BOM_Supplier Part") "C49257")
      )
      (libsource (lib "") (part "Header-Male-2.54_1x3_2"))
    )
    (comp (ref "H16")
      (value "Header-Male-2.54_1x3")
      (fields
        (field (name "BOM_Manufacturer Part") "Header2.54mm 1*3P")
        (field (name "BOM_Supplier Part") "C49257")
      )
      (libsource (lib "") (part "Header-Male-2.54_1x3_2"))
    )
    (comp (ref "H17")
      (value "Header-Male-2.54_1x3")
      (fields
        (field (name "BOM_Manufacturer Part") "Header2.54mm 1*3P")
        (field (name "BOM_Supplier Part") "C49257")
      )
      (libsource (lib "") (part "Header-Male-2.54_1x3_3"))
    )
    (comp (ref "H18")
      (value "Header-Male-2.54_1x3")
      (fields
        (field (name "BOM_Manufacturer Part") "Header2.54mm 1*3P")
        (field (name "BOM_Supplier Part") "C49257")
      )
      (libsource (lib "") (part "Header-Male-2.54_1x3_3"))
    )
    (comp (ref "H19")
      (value "Header-Male-2.54_1x3")
      (fields
        (field (name "BOM_Manufacturer Part") "Header2.54mm 1*3P")
        (field (name "BOM_Supplier Part") "C49257")
      )
      (libsource (lib "") (part "Header-Male-2.54_1x3_2"))
    )
    (comp (ref "H20")
      (value "Header-Male-2.54_1x3")
      (fields
        (field (name "BOM_Manufacturer Part") "Header2.54mm 1*3P")
        (field (name "BOM_Supplier Part") "C49257")
      )
      (libsource (lib "") (part "Header-Male-2.54_1x3_2"))
    )
    (comp (ref "H21")
      (value "PWR")
      (fields
        (field (name "BOM_Manufacturer Part") "Header2.54mm 1*3P")
        (field (name "BOM_Supplier Part") "C49257")
      )
      (libsource (lib "") (part "Header-Male-2.54_1x3_5"))
    )
    (comp (ref "H22")
      (value "RPI2C")
      (fields
        (field (name "BOM_Manufacturer Part") "Header2.54mm 1*3P")
        (field (name "BOM_Supplier Part") "C49257")
      )
      (libsource (lib "") (part "Header-Male-2.54_1x3_9"))
    )
    (comp (ref "JP1") (value "OEE") (libsource (lib "") (part "JUMPER-SMT_2_2")))
    (comp (ref "JP2") (value "PCF_SDA_EN") (libsource (lib "") (part "JUMPER-SMT_2")))
    (comp (ref "JP3") (value "JUMPER-SMT_2") (libsource (lib "") (part "JUMPER-SMT_2")))
    (comp (ref "JP4") (value "5VLSL") (libsource (lib "") (part "JUMPER-SMT_2_1")))
    (comp (ref "JP5") (value "USBPWR_OVR") (libsource (lib "") (part "JUMPER-SMT_2")))
    (comp (ref "JP6") (value "GP22WS") (libsource (lib "") (part "JUMPER-SMT_2_2")))
    (comp (ref "JP7") (value "GP16WS") (libsource (lib "") (part "JUMPER-SMT_2_2")))
    (comp (ref "JP8") (value "JUMPER-SMT_2") (libsource (lib "") (part "JUMPER-SMT_2")))
    (comp (ref "JP9") (value "PCF_SCL_EN") (libsource (lib "") (part "JUMPER-SMT_2")))
    (comp (ref "JP10") (value "ESPTX") (libsource (lib "") (part "JUMPER-SMT_2")))
    (comp (ref "JP11") (value "ESPRX") (libsource (lib "") (part "JUMPER-SMT_2")))
    (comp (ref "JP12") (value "PCF_SDA_EN") (libsource (lib "") (part "JUMPER-SMT_2")))
    (comp (ref "JP13") (value "PCF_SCL_EN") (libsource (lib "") (part "JUMPER-SMT_2")))
    (comp (ref "JP14") (value "RP_ESP_RST") (libsource (lib "") (part "JUMPER-SMT_2")))
    (comp (ref "JP15") (value "RP_ESP_BOOT") (libsource (lib "") (part "JUMPER-SMT_2")))
    (comp (ref "JP16") (value "USBC_TO_RP-") (libsource (lib "") (part "JUMPER-SMT_2")))
    (comp (ref "JP17") (value "USBC_TO_RP+") (libsource (lib "") (part "JUMPER-SMT_2")))
    (comp (ref "JP18") (value "USBC_TO_RP-") (libsource (lib "") (part "JUMPER-SMT_2")))
    (comp (ref "JP19") (value "USBC_TO_RP+") (libsource (lib "") (part "JUMPER-SMT_2")))
    (comp (ref "LED1")
      (value "WS2812B-B")
      (fields (field (name "BOM_Supplier Part") "C114586"))
      (libsource (lib "") (part "Unknown_1050_-1780"))
    )
    (comp (ref "LED2")
      (value "FC-2012HRK-620D")
      (fields (field (name "BOM_Supplier Part") "C84256"))
      (libsource (lib "") (part "FC-2012HRK-620D"))
    )
    (comp (ref "LED3")
      (value "WS2812B-B")
      (fields (field (name "BOM_Supplier Part") "C114586"))
      (libsource (lib "") (part "Unknown_805_-1770"))
    )
    (comp (ref "LED4")
      (value "WS2812B-B")
      (fields (field (name "BOM_Supplier Part") "C114586"))
      (libsource (lib "") (part "Unknown_2320_-2010"))
    )
    (comp (ref "LED5")
      (value "WS2812B-B")
      (fields (field (name "BOM_Supplier Part") "C114586"))
      (libsource (lib "") (part "Unknown_1930_-2005"))
    )
    (comp (ref "LED6")
      (value "WS2812B-B")
      (fields (field (name "BOM_Supplier Part") "C114586"))
      (libsource (lib "") (part "Unknown_1520_-2005"))
    )
    (comp (ref "LED7")
      (value "WS2812B-B")
      (fields (field (name "BOM_Supplier Part") "C114586"))
      (libsource (lib "") (part "Unknown_1650_-2005"))
    )
    (comp (ref "LED8")
      (value "WS2812B-B")
      (fields (field (name "BOM_Supplier Part") "C114586"))
      (libsource (lib "") (part "Unknown_2325_-1780"))
    )
    (comp (ref "LED9")
      (value "WS2812B-B")
      (fields (field (name "BOM_Supplier Part") "C114586"))
      (libsource (lib "") (part "Unknown_2165_-1775"))
    )
    (comp (ref "LED10")
      (value "WS2812B-B")
      (fields (field (name "BOM_Supplier Part") "C114586"))
      (libsource (lib "") (part "Unknown_1990_-1775"))
    )
    (comp (ref "LED11")
      (value "WS2812B-B")
      (fields (field (name "BOM_Supplier Part") "C114586"))
      (libsource (lib "") (part "Unknown_1860_-1775"))
    )
    (comp (ref "LED12")
      (value "WS2812B-B")
      (fields (field (name "BOM_Supplier Part") "C114586"))
      (libsource (lib "") (part "Unknown_1735_-1775"))
    )
    (comp (ref "LED13")
      (value "WS2812B-B")
      (fields (field (name "BOM_Supplier Part") "C114586"))
      (libsource (lib "") (part "Unknown_1350_-1775"))
    )
    (comp (ref "LED14")
      (value "WS2812B-B")
      (fields (field (name "BOM_Supplier Part") "C114586"))
      (libsource (lib "") (part "Unknown_1475_-1775"))
    )
    (comp (ref "LED15")
      (value "WS2812B-B")
      (fields (field (name "BOM_Supplier Part") "C114586"))
      (libsource (lib "") (part "Unknown_1605_-1775"))
    )
    (comp (ref "LED16")
      (value "WS2812B-B")
      (fields (field (name "BOM_Supplier Part") "C114586"))
      (libsource (lib "") (part "Unknown_1195_-1775"))
    )
    (comp (ref "LED17")
      (value "WS2812B-B")
      (fields (field (name "BOM_Supplier Part") "C114586"))
      (libsource (lib "") (part "Unknown_1775_-2005"))
    )
    (comp (ref "LED18")
      (value "WS2812B-B")
      (fields (field (name "BOM_Supplier Part") "C114586"))
      (libsource (lib "") (part "Unknown_1390_-2005"))
    )
    (comp (ref "LED19")
      (value "WS2812B-B")
      (fields (field (name "BOM_Supplier Part") "C114586"))
      (libsource (lib "") (part "Unknown_1265_-2005"))
    )
    (comp (ref "LED20")
      (value "WS2812B-B")
      (fields (field (name "BOM_Supplier Part") "C114586"))
      (libsource (lib "") (part "Unknown_1135_-2005"))
    )
    (comp (ref "LED21")
      (value "WS2812B-B")
      (fields (field (name "BOM_Supplier Part") "C114586"))
      (libsource (lib "") (part "Unknown_960_-2005"))
    )
    (comp (ref "LED22")
      (value "WS2812B-B")
      (fields (field (name "BOM_Supplier Part") "C114586"))
      (libsource (lib "") (part "Unknown_800_-2000"))
    )
    (comp (ref "LED23")
      (value "WS2812B-B")
      (fields (field (name "BOM_Supplier Part") "C114586"))
      (libsource (lib "") (part "Unknown_2075_-2000"))
    )
    (comp (ref "LED24")
      (value "WS2812B-B")
      (fields (field (name "BOM_Supplier Part") "C114586"))
      (libsource (lib "") (part "Unknown_1080_-2215"))
    )
    (comp (ref "LED25")
      (value "WS2812B-B")
      (fields (field (name "BOM_Supplier Part") "C114586"))
      (libsource (lib "") (part "Unknown_2355_-2215"))
    )
    (comp (ref "LED26")
      (value "WS2812B-B")
      (fields (field (name "BOM_Supplier Part") "C114586"))
      (libsource (lib "") (part "Unknown_2195_-2210"))
    )
    (comp (ref "LED27")
      (value "WS2812B-B")
      (fields (field (name "BOM_Supplier Part") "C114586"))
      (libsource (lib "") (part "Unknown_2020_-2210"))
    )
    (comp (ref "LED28")
      (value "WS2812B-B")
      (fields (field (name "BOM_Supplier Part") "C114586"))
      (libsource (lib "") (part "Unknown_1890_-2210"))
    )
    (comp (ref "LED29")
      (value "WS2812B-B")
      (fields (field (name "BOM_Supplier Part") "C114586"))
      (libsource (lib "") (part "Unknown_1765_-2210"))
    )
    (comp (ref "LED30")
      (value "WS2812B-B")
      (fields (field (name "BOM_Supplier Part") "C114586"))
      (libsource (lib "") (part "Unknown_1380_-2210"))
    )
    (comp (ref "LED31")
      (value "WS2812B-B")
      (fields (field (name "BOM_Supplier Part") "C114586"))
      (libsource (lib "") (part "Unknown_1505_-2210"))
    )
    (comp (ref "LED32")
      (value "WS2812B-B")
      (fields (field (name "BOM_Supplier Part") "C114586"))
      (libsource (lib "") (part "Unknown_1635_-2210"))
    )
    (comp (ref "LED33")
      (value "WS2812B-B")
      (fields (field (name "BOM_Supplier Part") "C114586"))
      (libsource (lib "") (part "Unknown_1225_-2210"))
    )
    (comp (ref "LED34")
      (value "WS2812B-B")
      (fields (field (name "BOM_Supplier Part") "C114586"))
      (libsource (lib "") (part "Unknown_835_-2205"))
    )
    (comp (ref "LED35")
      (value "WS2812B-B")
      (fields (field (name "BOM_Supplier Part") "C114586"))
      (libsource (lib "") (part "Unknown_2345_-2390"))
    )
    (comp (ref "LED36")
      (value "WS2812B-B")
      (fields (field (name "BOM_Supplier Part") "C114586"))
      (libsource (lib "") (part "Unknown_1955_-2385"))
    )
    (comp (ref "LED37")
      (value "WS2812B-B")
      (fields (field (name "BOM_Supplier Part") "C114586"))
      (libsource (lib "") (part "Unknown_1545_-2385"))
    )
    (comp (ref "LED38")
      (value "WS2812B-B")
      (fields (field (name "BOM_Supplier Part") "C114586"))
      (libsource (lib "") (part "Unknown_1675_-2385"))
    )
    (comp (ref "LED39")
      (value "WS2812B-B")
      (fields (field (name "BOM_Supplier Part") "C114586"))
      (libsource (lib "") (part "Unknown_1800_-2385"))
    )
    (comp (ref "LED40")
      (value "WS2812B-B")
      (fields (field (name "BOM_Supplier Part") "C114586"))
      (libsource (lib "") (part "Unknown_1415_-2385"))
    )
    (comp (ref "LED41")
      (value "WS2812B-B")
      (fields (field (name "BOM_Supplier Part") "C114586"))
      (libsource (lib "") (part "Unknown_1290_-2385"))
    )
    (comp (ref "LED42")
      (value "WS2812B-B")
      (fields (field (name "BOM_Supplier Part") "C114586"))
      (libsource (lib "") (part "Unknown_1160_-2385"))
    )
    (comp (ref "LED43")
      (value "WS2812B-B")
      (fields (field (name "BOM_Supplier Part") "C114586"))
      (libsource (lib "") (part "Unknown_985_-2385"))
    )
    (comp (ref "LED44")
      (value "WS2812B-B")
      (fields (field (name "BOM_Supplier Part") "C114586"))
      (libsource (lib "") (part "Unknown_825_-2380"))
    )
    (comp (ref "LED45")
      (value "WS2812B-B")
      (fields (field (name "BOM_Supplier Part") "C114586"))
      (libsource (lib "") (part "Unknown_2100_-2380"))
    )
    (comp (ref "LED46")
      (value "WS2812B-B")
      (fields (field (name "BOM_Supplier Part") "C114586"))
      (libsource (lib "") (part "Unknown_1065_-2580"))
    )
    (comp (ref "LED47")
      (value "WS2812B-B")
      (fields (field (name "BOM_Supplier Part") "C114586"))
      (libsource (lib "") (part "Unknown_2340_-2580"))
    )
    (comp (ref "LED48")
      (value "WS2812B-B")
      (fields (field (name "BOM_Supplier Part") "C114586"))
      (libsource (lib "") (part "Unknown_2180_-2575"))
    )
    (comp (ref "LED49")
      (value "WS2812B-B")
      (fields (field (name "BOM_Supplier Part") "C114586"))
      (libsource (lib "") (part "Unknown_2005_-2575"))
    )
    (comp (ref "LED50")
      (value "WS2812B-B")
      (fields (field (name "BOM_Supplier Part") "C114586"))
      (libsource (lib "") (part "Unknown_1875_-2575"))
    )
    (comp (ref "LED51")
      (value "WS2812B-B")
      (fields (field (name "BOM_Supplier Part") "C114586"))
      (libsource (lib "") (part "Unknown_1750_-2575"))
    )
    (comp (ref "LED52")
      (value "WS2812B-B")
      (fields (field (name "BOM_Supplier Part") "C114586"))
      (libsource (lib "") (part "Unknown_1365_-2575"))
    )
    (comp (ref "LED53")
      (value "WS2812B-B")
      (fields (field (name "BOM_Supplier Part") "C114586"))
      (libsource (lib "") (part "Unknown_1490_-2575"))
    )
    (comp (ref "LED54")
      (value "WS2812B-B")
      (fields (field (name "BOM_Supplier Part") "C114586"))
      (libsource (lib "") (part "Unknown_1620_-2575"))
    )
    (comp (ref "LED55")
      (value "WS2812B-B")
      (fields (field (name "BOM_Supplier Part") "C114586"))
      (libsource (lib "") (part "Unknown_1210_-2575"))
    )
    (comp (ref "LED56")
      (value "WS2812B-B")
      (fields (field (name "BOM_Supplier Part") "C114586"))
      (libsource (lib "") (part "Unknown_820_-2570"))
    )
    (comp (ref "LED57")
      (value "WS2812B-B")
      (fields (field (name "BOM_Supplier Part") "C114586"))
      (libsource (lib "") (part "Unknown_2330_-2760"))
    )
    (comp (ref "LED58")
      (value "WS2812B-B")
      (fields (field (name "BOM_Supplier Part") "C114586"))
      (libsource (lib "") (part "Unknown_1940_-2755"))
    )
    (comp (ref "LED59")
      (value "WS2812B-B")
      (fields (field (name "BOM_Supplier Part") "C114586"))
      (libsource (lib "") (part "Unknown_1530_-2755"))
    )
    (comp (ref "LED60")
      (value "WS2812B-B")
      (fields (field (name "BOM_Supplier Part") "C114586"))
      (libsource (lib "") (part "Unknown_1660_-2755"))
    )
    (comp (ref "LED61")
      (value "WS2812B-B")
      (fields (field (name "BOM_Supplier Part") "C114586"))
      (libsource (lib "") (part "Unknown_1785_-2755"))
    )
    (comp (ref "LED62")
      (value "WS2812B-B")
      (fields (field (name "BOM_Supplier Part") "C114586"))
      (libsource (lib "") (part "Unknown_1400_-2755"))
    )
    (comp (ref "LED63")
      (value "WS2812B-B")
      (fields (field (name "BOM_Supplier Part") "C114586"))
      (libsource (lib "") (part "Unknown_1275_-2755"))
    )
    (comp (ref "LED64")
      (value "WS2812B-B")
      (fields (field (name "BOM_Supplier Part") "C114586"))
      (libsource (lib "") (part "Unknown_1145_-2755"))
    )
    (comp (ref "LED65")
      (value "WS2812B-B")
      (fields (field (name "BOM_Supplier Part") "C114586"))
      (libsource (lib "") (part "Unknown_970_-2755"))
    )
    (comp (ref "LED66")
      (value "WS2812B-B")
      (fields (field (name "BOM_Supplier Part") "C114586"))
      (libsource (lib "") (part "Unknown_810_-2750"))
    )
    (comp (ref "LED67")
      (value "WS2812B-B")
      (fields (field (name "BOM_Supplier Part") "C114586"))
      (libsource (lib "") (part "Unknown_2085_-2750"))
    )
    (comp (ref "LED68")
      (value "WS2812B-B")
      (fields (field (name "BOM_Supplier Part") "C114586"))
      (libsource (lib "") (part "Unknown_1050_-2930"))
    )
    (comp (ref "LED69")
      (value "WS2812B-B")
      (fields (field (name "BOM_Supplier Part") "C114586"))
      (libsource (lib "") (part "Unknown_2325_-2930"))
    )
    (comp (ref "LED70")
      (value "WS2812B-B")
      (fields (field (name "BOM_Supplier Part") "C114586"))
      (libsource (lib "") (part "Unknown_2165_-2925"))
    )
    (comp (ref "LED71")
      (value "WS2812B-B")
      (fields (field (name "BOM_Supplier Part") "C114586"))
      (libsource (lib "") (part "Unknown_1990_-2925"))
    )
    (comp (ref "LED72")
      (value "WS2812B-B")
      (fields (field (name "BOM_Supplier Part") "C114586"))
      (libsource (lib "") (part "Unknown_1860_-2925"))
    )
    (comp (ref "LED73")
      (value "WS2812B-B")
      (fields (field (name "BOM_Supplier Part") "C114586"))
      (libsource (lib "") (part "Unknown_1735_-2925"))
    )
    (comp (ref "LED74")
      (value "WS2812B-B")
      (fields (field (name "BOM_Supplier Part") "C114586"))
      (libsource (lib "") (part "Unknown_1350_-2925"))
    )
    (comp (ref "LED75")
      (value "WS2812B-B")
      (fields (field (name "BOM_Supplier Part") "C114586"))
      (libsource (lib "") (part "Unknown_1475_-2925"))
    )
    (comp (ref "LED76")
      (value "WS2812B-B")
      (fields (field (name "BOM_Supplier Part") "C114586"))
      (libsource (lib "") (part "Unknown_1605_-2925"))
    )
    (comp (ref "LED77")
      (value "WS2812B-B")
      (fields (field (name "BOM_Supplier Part") "C114586"))
      (libsource (lib "") (part "Unknown_1195_-2925"))
    )
    (comp (ref "LED78")
      (value "WS2812B-B")
      (fields (field (name "BOM_Supplier Part") "C114586"))
      (libsource (lib "") (part "Unknown_805_-2920"))
    )
    (comp (ref "LED79")
      (value "WS2812B-B")
      (fields (field (name "BOM_Supplier Part") "C114586"))
      (libsource (lib "") (part "Unknown_2320_-3115"))
    )
    (comp (ref "LED80")
      (value "WS2812B-B")
      (fields (field (name "BOM_Supplier Part") "C114586"))
      (libsource (lib "") (part "Unknown_1930_-3110"))
    )
    (comp (ref "LED81")
      (value "WS2812B-B")
      (fields (field (name "BOM_Supplier Part") "C114586"))
      (libsource (lib "") (part "Unknown_1520_-3110"))
    )
    (comp (ref "LED82")
      (value "WS2812B-B")
      (fields (field (name "BOM_Supplier Part") "C114586"))
      (libsource (lib "") (part "Unknown_1650_-3110"))
    )
    (comp (ref "LED83")
      (value "WS2812B-B")
      (fields (field (name "BOM_Supplier Part") "C114586"))
      (libsource (lib "") (part "Unknown_1775_-3110"))
    )
    (comp (ref "LED84")
      (value "WS2812B-B")
      (fields (field (name "BOM_Supplier Part") "C114586"))
      (libsource (lib "") (part "Unknown_1390_-3110"))
    )
    (comp (ref "LED85")
      (value "WS2812B-B")
      (fields (field (name "BOM_Supplier Part") "C114586"))
      (libsource (lib "") (part "Unknown_1265_-3110"))
    )
    (comp (ref "LED86")
      (value "WS2812B-B")
      (fields (field (name "BOM_Supplier Part") "C114586"))
      (libsource (lib "") (part "Unknown_1135_-3110"))
    )
    (comp (ref "LED87")
      (value "WS2812B-B")
      (fields (field (name "BOM_Supplier Part") "C114586"))
      (libsource (lib "") (part "Unknown_960_-3110"))
    )
    (comp (ref "LED88")
      (value "WS2812B-B")
      (fields (field (name "BOM_Supplier Part") "C114586"))
      (libsource (lib "") (part "Unknown_800_-3105"))
    )
    (comp (ref "LED89")
      (value "WS2812B-B")
      (fields (field (name "BOM_Supplier Part") "C114586"))
      (libsource (lib "") (part "Unknown_2075_-3105"))
    )
    (comp (ref "LED90")
      (value "WS2812B-B")
      (fields (field (name "BOM_Supplier Part") "C114586"))
      (libsource (lib "") (part "Unknown_1050_-3345"))
    )
    (comp (ref "LED91")
      (value "WS2812B-B")
      (fields (field (name "BOM_Supplier Part") "C114586"))
      (libsource (lib "") (part "Unknown_2325_-3345"))
    )
    (comp (ref "LED92")
      (value "WS2812B-B")
      (fields (field (name "BOM_Supplier Part") "C114586"))
      (libsource (lib "") (part "Unknown_2165_-3340"))
    )
    (comp (ref "LED93")
      (value "WS2812B-B")
      (fields (field (name "BOM_Supplier Part") "C114586"))
      (libsource (lib "") (part "Unknown_1990_-3340"))
    )
    (comp (ref "LED94")
      (value "WS2812B-B")
      (fields (field (name "BOM_Supplier Part") "C114586"))
      (libsource (lib "") (part "Unknown_1860_-3340"))
    )
    (comp (ref "LED95")
      (value "WS2812B-B")
      (fields (field (name "BOM_Supplier Part") "C114586"))
      (libsource (lib "") (part "Unknown_1735_-3340"))
    )
    (comp (ref "LED96")
      (value "WS2812B-B")
      (fields (field (name "BOM_Supplier Part") "C114586"))
      (libsource (lib "") (part "Unknown_1350_-3340"))
    )
    (comp (ref "LED97")
      (value "WS2812B-B")
      (fields (field (name "BOM_Supplier Part") "C114586"))
      (libsource (lib "") (part "Unknown_1475_-3340"))
    )
    (comp (ref "LED98")
      (value "WS2812B-B")
      (fields (field (name "BOM_Supplier Part") "C114586"))
      (libsource (lib "") (part "Unknown_1605_-3340"))
    )
    (comp (ref "LED99")
      (value "WS2812B-B")
      (fields (field (name "BOM_Supplier Part") "C114586"))
      (libsource (lib "") (part "Unknown_1195_-3340"))
    )
    (comp (ref "LED100")
      (value "WS2812B-B")
      (fields (field (name "BOM_Supplier Part") "C114586"))
      (libsource (lib "") (part "Unknown_805_-3335"))
    )
    (comp (ref "LED101")
      (value "WS2812B-B")
      (fields (field (name "BOM_Supplier Part") "C114586"))
      (libsource (lib "") (part "Unknown_2315_-3555"))
    )
    (comp (ref "LED102")
      (value "WS2812B-B")
      (fields (field (name "BOM_Supplier Part") "C114586"))
      (libsource (lib "") (part "Unknown_1925_-3550"))
    )
    (comp (ref "LED103")
      (value "WS2812B-B")
      (fields (field (name "BOM_Supplier Part") "C114586"))
      (libsource (lib "") (part "Unknown_1515_-3550"))
    )
    (comp (ref "LED104")
      (value "WS2812B-B")
      (fields (field (name "BOM_Supplier Part") "C114586"))
      (libsource (lib "") (part "Unknown_1645_-3550"))
    )
    (comp (ref "LED105")
      (value "WS2812B-B")
      (fields (field (name "BOM_Supplier Part") "C114586"))
      (libsource (lib "") (part "Unknown_1770_-3550"))
    )
    (comp (ref "LED106")
      (value "WS2812B-B")
      (fields (field (name "BOM_Supplier Part") "C114586"))
      (libsource (lib "") (part "Unknown_1385_-3550"))
    )
    (comp (ref "LED107")
      (value "WS2812B-B")
      (fields (field (name "BOM_Supplier Part") "C114586"))
      (libsource (lib "") (part "Unknown_1260_-3550"))
    )
    (comp (ref "LED108")
      (value "WS2812B-B")
      (fields (field (name "BOM_Supplier Part") "C114586"))
      (libsource (lib "") (part "Unknown_1130_-3550"))
    )
    (comp (ref "LED109")
      (value "WS2812B-B")
      (fields (field (name "BOM_Supplier Part") "C114586"))
      (libsource (lib "") (part "Unknown_955_-3550"))
    )
    (comp (ref "LED110")
      (value "WS2812B-B")
      (fields (field (name "BOM_Supplier Part") "C114586"))
      (libsource (lib "") (part "Unknown_795_-3545"))
    )
    (comp (ref "LED111")
      (value "WS2812B-B")
      (fields (field (name "BOM_Supplier Part") "C114586"))
      (libsource (lib "") (part "Unknown_2070_-3545"))
    )
    (comp (ref "LED112")
      (value "WS2812B-B")
      (fields (field (name "BOM_Supplier Part") "C114586"))
      (libsource (lib "") (part "Unknown_2675_-3555"))
    )
    (comp (ref "LED113")
      (value "WS2812B-B")
      (fields (field (name "BOM_Supplier Part") "C114586"))
      (libsource (lib "") (part "Unknown_545_-3425"))
    )
    (comp (ref "LED114")
      (value "WS2812B-B")
      (fields (field (name "BOM_Supplier Part") "C114586"))
      (libsource (lib "") (part "Unknown_560_-1860"))
    )
    (comp (ref "LED115")
      (value "WS2812B-B")
      (fields (field (name "BOM_Supplier Part") "C114586"))
      (libsource (lib "") (part "Unknown_2390_-1565"))
    )
    (comp (ref "LED116")
      (value "FC-2012HRK-620D")
      (fields (field (name "BOM_Supplier Part") "C84256"))
      (libsource (lib "") (part "FC-2012HRK-620D_1"))
    )
    (comp (ref "P1")
      (value "RPSWD")
      (fields
        (field (name "BOM_Manufacturer Part") "Female header1*5P")
        (field (name "BOM_Supplier Part") "C66508")
      )
      (libsource (lib "") (part "Female header1*5P"))
    )
    (comp (ref "P2")
      (value "ESPPROG")
      (fields
        (field (name "BOM_Manufacturer Part") "Female header1*5P")
        (field (name "BOM_Supplier Part") "C66508")
      )
      (libsource (lib "") (part "Female header1*5P"))
    )
    (comp (ref "P3")
      (value "Female header1*2P")
      (fields (field (name "BOM_Supplier Part") "C66509"))
      (libsource (lib "") (part "Female header1*2P"))
    )
    (comp (ref "PWRRST")
      (value "PTS810SJM250SMTRLFS")
      (fields (field (name "BOM_Supplier Part") "C116501"))
      (libsource (lib "") (part "PTS810SJM250SMTRLFS_4"))
    )
    (comp (ref "QBOOT")
      (value "PTS810SJM250SMTRLFS")
      (fields (field (name "BOM_Supplier Part") "C116501"))
      (libsource (lib "") (part "PTS810SJM250SMTRLFS_3"))
    )
    (comp (ref "QU1")
      (value "RP2040")
      (fields (field (name "BOM_Supplier Part") "C2040"))
      (libsource (lib "") (part "RP2040"))
    )
    (comp (ref "QU2")
      (value "W25Q128JWPIQ")
      (fields (field (name "BOM_Supplier Part") "C2689660"))
      (libsource (lib "") (part "W25Q128JWPIQ"))
    )
    (comp (ref "QX1")
      (value "12MHz")
      (fields
        (field (name "BOM_Manufacturer Part") "X322512MSB4SI")
        (field (name "BOM_Supplier Part") "C9002")
      )
      (libsource (lib "") (part "SMD-3225_4P12M12PF10PPM"))
    )
    (comp (ref "R1")
      (value "4.7K")
      (fields
        (field (name "BOM_Manufacturer Part") "0805W8F4701T5E")
        (field (name "BOM_Supplier Part") "C17673")
      )
      (libsource (lib "") (part "CR0805F4K7P05_1"))
    )
    (comp (ref "R2")
      (value "1kΩ")
      (fields
        (field (name "BOM_Manufacturer Part") "0805W8F1001T5E")
        (field (name "BOM_Supplier Part") "C17513")
      )
      (libsource (lib "") (part "PTFR0805D1K00P9"))
    )
    (comp (ref "R3")
      (value "4.7K")
      (fields
        (field (name "BOM_Manufacturer Part") "0805W8F4701T5E")
        (field (name "BOM_Supplier Part") "C17673")
      )
      (libsource (lib "") (part "CR0805F4K7P05"))
    )
    (comp (ref "R4")
      (value "4.7K")
      (fields
        (field (name "BOM_Manufacturer Part") "0805W8F4701T5E")
        (field (name "BOM_Supplier Part") "C17673")
      )
      (libsource (lib "") (part "CR0805F4K7P05_2"))
    )
    (comp (ref "R5")
      (value "10K")
      (fields
        (field (name "BOM_Manufacturer Part") "0805W8F1002T5E")
        (field (name "BOM_Supplier Part") "C17414")
      )
      (libsource (lib "") (part "0805W8F1002T5E"))
    )
    (comp (ref "R6")
      (value "10K")
      (fields
        (field (name "BOM_Manufacturer Part") "0805W8F1002T5E")
        (field (name "BOM_Supplier Part") "C17414")
      )
      (libsource (lib "") (part "0805W8F1002T5E_2"))
    )
    (comp (ref "R7")
      (value "27Ω")
      (fields
        (field (name "BOM_Manufacturer Part") "0805W8F270JT5E")
        (field (name "BOM_Supplier Part") "C17594")
      )
      (libsource (lib "") (part "CR0805F24RP05_1"))
    )
    (comp (ref "R8")
      (value "10K")
      (fields
        (field (name "BOM_Manufacturer Part") "0805W8F1002T5E")
        (field (name "BOM_Supplier Part") "C17414")
      )
      (libsource (lib "") (part "0805W8F1002T5E_2"))
    )
    (comp (ref "R9")
      (value "27Ω")
      (fields
        (field (name "BOM_Manufacturer Part") "0805W8F270JT5E")
        (field (name "BOM_Supplier Part") "C17594")
      )
      (libsource (lib "") (part "CR0805F24RP05"))
    )
    (comp (ref "R10")
      (value "50")
      (fields
        (field (name "BOM_Manufacturer Part") "0805W8F1002T5E")
        (field (name "BOM_Supplier Part") "C17414")
      )
      (libsource (lib "") (part "0805W8F1002T5E_1"))
    )
    (comp (ref "R11")
      (value "1K")
      (fields
        (field (name "BOM_Manufacturer Part") "0805W8F1001T5E")
        (field (name "BOM_Supplier Part") "C17513")
      )
      (libsource (lib "") (part "0805W8F1002T5E_2"))
    )
    (comp (ref "R12")
      (value "1K")
      (fields
        (field (name "BOM_Manufacturer Part") "0805W8F1001T5E")
        (field (name "BOM_Supplier Part") "C17513")
      )
      (libsource (lib "") (part "0805W8F1002T5E_2"))
    )
    (comp (ref "R13")
      (value "100Ω")
      (fields
        (field (name "BOM_Manufacturer Part") "0805W8F1000T5E")
        (field (name "BOM_Supplier Part") "C17408")
      )
      (libsource (lib "") (part "PTFR0805B100RN9_1"))
    )
    (comp (ref "R14")
      (value "10K")
      (fields
        (field (name "BOM_Manufacturer Part") "0805W8F1002T5E")
        (field (name "BOM_Supplier Part") "C17414")
      )
      (libsource (lib "") (part "0805W8F1002T5E_2"))
    )
    (comp (ref "R15")
      (value "10K")
      (fields
        (field (name "BOM_Manufacturer Part") "0805W8F1002T5E")
        (field (name "BOM_Supplier Part") "C17414")
      )
      (libsource (lib "") (part "0805W8F1002T5E_1"))
    )
    (comp (ref "R16")
      (value "10K")
      (fields
        (field (name "BOM_Manufacturer Part") "0805W8F1002T5E")
        (field (name "BOM_Supplier Part") "C17414")
      )
      (libsource (lib "") (part "0805W8F1002T5E_1"))
    )
    (comp (ref "R17")
      (value "5.1kΩ")
      (fields
        (field (name "BOM_Manufacturer Part") "0805W8F5101T5E")
        (field (name "BOM_Supplier Part") "C27834")
      )
      (libsource (lib "") (part "0805W8F5101T5E"))
    )
    (comp (ref "R18")
      (value "10K")
      (fields
        (field (name "BOM_Manufacturer Part") "0805W8F1002T5E")
        (field (name "BOM_Supplier Part") "C17414")
      )
      (libsource (lib "") (part "0805W8F1002T5E"))
    )
    (comp (ref "R19")
      (value "5.1kΩ")
      (fields
        (field (name "BOM_Manufacturer Part") "0805W8F5101T5E")
        (field (name "BOM_Supplier Part") "C27834")
      )
      (libsource (lib "") (part "0805W8F5101T5E_1"))
    )
    (comp (ref "R20")
      (value "10K")
      (fields
        (field (name "BOM_Manufacturer Part") "0805W8F1002T5E")
        (field (name "BOM_Supplier Part") "C17414")
      )
      (libsource (lib "") (part "0805W8F1002T5E"))
    )
    (comp (ref "R21")
      (value "10K")
      (fields
        (field (name "BOM_Manufacturer Part") "0805W8F1002T5E")
        (field (name "BOM_Supplier Part") "C17414")
      )
      (libsource (lib "") (part "0805W8F1002T5E"))
    )
    (comp (ref "R22")
      (value "10K")
      (fields
        (field (name "BOM_Manufacturer Part") "0805W8F1002T5E")
        (field (name "BOM_Supplier Part") "C17414")
      )
      (libsource (lib "") (part "0805W8F1002T5E"))
    )
    (comp (ref "R23")
      (value "10K")
      (fields
        (field (name "BOM_Manufacturer Part") "0805W8F1002T5E")
        (field (name "BOM_Supplier Part") "C17414")
      )
      (libsource (lib "") (part "0805W8F1002T5E"))
    )
    (comp (ref "R24")
      (value "10K")
      (fields
        (field (name "BOM_Manufacturer Part") "0805W8F1002T5E")
        (field (name "BOM_Supplier Part") "C17414")
      )
      (libsource (lib "") (part "0805W8F1002T5E_2"))
    )
    (comp (ref "R25")
      (value "100Ω")
      (fields
        (field (name "BOM_Manufacturer Part") "0805W8F1000T5E")
        (field (name "BOM_Supplier Part") "C17408")
      )
      (libsource (lib "") (part "PTFR0805B100RN9"))
    )
    (comp (ref "RPRST")
      (value "PTS810SJM250SMTRLFS")
      (fields (field (name "BOM_Supplier Part") "C116501"))
      (libsource (lib "") (part "PTS810SJM250SMTRLFS_2"))
    )
    (comp (ref "RPUSB")
      (value "HDR-M-2.54_1x4")
      (fields (field (name "BOM_Supplier Part") "C124378"))
      (libsource (lib "") (part "HDR-M-2.54_1x4"))
    )
    (comp (ref "RPUSB1")
      (value "HDR-M-2.54_1x4")
      (fields (field (name "BOM_Supplier Part") "C124378"))
      (libsource (lib "") (part "HDR-M-2.54_1x4"))
    )
    (comp (ref "U1")
      (value "BH1750FVI-TR")
      (fields (field (name "BOM_Supplier Part") "C78960"))
      (libsource (lib "") (part "BH1750FVI-TR"))
    )
    (comp (ref "U2")
      (value "AMS1117-3.3")
      (fields (field (name "BOM_Supplier Part") "C6186"))
      (libsource (lib "") (part "Unknown_2010_-250"))
    )
    (comp (ref "U3")
      (value "PCF85263ATL/AX")
      (fields (field (name "BOM_Supplier Part") "C2651523"))
      (libsource (lib "") (part "PCF85263ATL/AX"))
    )
    (comp (ref "U4")
      (value "M24C02-WMN6TP")
      (fields (field (name "BOM_Supplier Part") "C7562"))
      (libsource (lib "") (part "M24C02-WMN6TP"))
    )
    (comp (ref "U5")
      (value "ESP-12F(ESP8266MOD)")
      (fields (field (name "BOM_Supplier Part") "C82891"))
      (libsource (lib "") (part "ESP-12F(ESP8266MOD)"))
    )
    (comp (ref "U6")
      (value "PCF8574RGTR")
      (fields (field (name "BOM_Supplier Part") "C2652270"))
      (libsource (lib "") (part "PCF8574RGTR"))
    )
    (comp (ref "U7")
      (value "TXB0101DCKR")
      (fields (field (name "BOM_Supplier Part") "C324081"))
      (libsource (lib "") (part "TXB0101DCKR"))
    )
    (comp (ref "U8")
      (value "MT8315ET")
      (fields (field (name "BOM_Supplier Part") "C879584"))
      (libsource (lib "") (part "MT8315ET_1"))
    )
    (comp (ref "U9")
      (value "MT8315ET")
      (fields (field (name "BOM_Supplier Part") "C879584"))
      (libsource (lib "") (part "MT8315ET_1"))
    )
    (comp (ref "U10")
      (value "MT8315ET")
      (fields (field (name "BOM_Supplier Part") "C879584"))
      (libsource (lib "") (part "MT8315ET"))
    )
    (comp (ref "U11")
      (value "MT8315ET")
      (fields (field (name "BOM_Supplier Part") "C879584"))
      (libsource (lib "") (part "MT8315ET_1"))
    )
    (comp (ref "U12")
      (value "TPD4S014DSQR")
      (fields (field (name "BOM_Supplier Part") "C202244"))
      (libsource (lib "") (part "TPD4S014DSQR"))
    )
    (comp (ref "USB1")
      (value "TYPE-C-31-M-26A")
      (fields (field (name "BOM_Supplier Part") "C2848621"))
      (libsource (lib "") (part "TYPE-C-31-M-26A"))
    )
    (comp (ref "X1")
      (value "CFV206-60.003KDZF")
      (fields (field (name "BOM_Supplier Part") "C389957"))
      (libsource (lib "") (part "CFV206-60.003KDZF"))
    )
  )
  (nets
    (net (code "1") (name "+1V1") (class "Default")
      (node (ref "C123") (pin "1") (pinfunction "1_1") (pintype "input"))
      (node (ref "C124") (pin "1") (pinfunction "1_1") (pintype "input"))
      (node (ref "QU1") (pin "23") (pinfunction "DVDD_23") (pintype "bidirectional"))
      (node (ref "QU1") (pin "45") (pinfunction "VREG_VOUT_45") (pintype "bidirectional"))
      (node (ref "QU1") (pin "50") (pinfunction "DVDD_50") (pintype "bidirectional"))
    )
    (net (code "2") (name "+5V") (class "Default")
      (node (ref "C1") (pin "1") (pinfunction "1_1") (pintype "input"))
      (node (ref "C100") (pin "1") (pinfunction "1_1") (pintype "input"))
      (node (ref "C101") (pin "1") (pinfunction "1_1") (pintype "input"))
      (node (ref "C102") (pin "1") (pinfunction "1_1") (pintype "input"))
      (node (ref "C103") (pin "1") (pinfunction "1_1") (pintype "input"))
      (node (ref "C104") (pin "1") (pinfunction "1_1") (pintype "input"))
      (node (ref "C105") (pin "1") (pinfunction "1_1") (pintype "input"))
      (node (ref "C106") (pin "1") (pinfunction "1_1") (pintype "input"))
      (node (ref "C107") (pin "1") (pinfunction "1_1") (pintype "input"))
      (node (ref "C108") (pin "1") (pinfunction "1_1") (pintype "input"))
      (node (ref "C109") (pin "1") (pinfunction "1_1") (pintype "input"))
      (node (ref "C11") (pin "1") (pinfunction "1_1") (pintype "input"))
      (node (ref "C110") (pin "1") (pinfunction "1_1") (pintype "input"))
      (node (ref "C111") (pin "1") (pinfunction "1_1") (pintype "input"))
      (node (ref "C112") (pin "1") (pinfunction "1_1") (pintype "input"))
      (node (ref "C113") (pin "1") (pinfunction "1_1") (pintype "input"))
      (node (ref "C114") (pin "1") (pinfunction "1_1") (pintype "input"))
      (node (ref "C115") (pin "1") (pinfunction "1_1") (pintype "input"))
      (node (ref "C116") (pin "1") (pinfunction "1_1") (pintype "input"))
      (node (ref "C117") (pin "1") (pinfunction "1_1") (pintype "input"))
      (node (ref "C118") (pin "1") (pinfunction "1_1") (pintype "input"))
      (node (ref "C119") (pin "1") (pinfunction "1_1") (pintype "input"))
      (node (ref "C12") (pin "1") (pinfunction "1_1") (pintype "input"))
      (node (ref "C120") (pin "1") (pinfunction "1_1") (pintype "input"))
      (node (ref "C121") (pin "1") (pinfunction "1_1") (pintype "input"))
      (node (ref "C13") (pin "1") (pinfunction "1_1") (pintype "input"))
      (node (ref "C138") (pin "1") (pinfunction "1_1") (pintype "input"))
      (node (ref "C14") (pin "1") (pinfunction "1_1") (pintype "input"))
      (node (ref "C15") (pin "1") (pinfunction "1_1") (pintype "input"))
      (node (ref "C16") (pin "1") (pinfunction "1_1") (pintype "input"))
      (node (ref "C17") (pin "1") (pinfunction "1_1") (pintype "input"))
      (node (ref "C18") (pin "1") (pinfunction "1_1") (pintype "input"))
      (node (ref "C19") (pin "1") (pinfunction "1_1") (pintype "input"))
      (node (ref "C2") (pin "2") (pinfunction "2_2") (pintype "input"))
      (node (ref "C20") (pin "1") (pinfunction "1_1") (pintype "input"))
      (node (ref "C21") (pin "1") (pinfunction "1_1") (pintype "input"))
      (node (ref "C22") (pin "1") (pinfunction "1_1") (pintype "input"))
      (node (ref "C23") (pin "1") (pinfunction "1_1") (pintype "input"))
      (node (ref "C24") (pin "1") (pinfunction "1_1") (pintype "input"))
      (node (ref "C25") (pin "1") (pinfunction "1_1") (pintype "input"))
      (node (ref "C26") (pin "1") (pinfunction "1_1") (pintype "input"))
      (node (ref "C27") (pin "1") (pinfunction "1_1") (pintype "input"))
      (node (ref "C28") (pin "1") (pinfunction "1_1") (pintype "input"))
      (node (ref "C29") (pin "1") (pinfunction "1_1") (pintype "input"))
      (node (ref "C30") (pin "1") (pinfunction "1_1") (pintype "input"))
      (node (ref "C31") (pin "1") (pinfunction "1_1") (pintype "input"))
      (node (ref "C32") (pin "1") (pinfunction "1_1") (pintype "input"))
      (node (ref "C33") (pin "1") (pinfunction "1_1") (pintype "input"))
      (node (ref "C34") (pin "1") (pinfunction "1_1") (pintype "input"))
      (node (ref "C35") (pin "1") (pinfunction "1_1") (pintype "input"))
      (node (ref "C36") (pin "1") (pinfunction "1_1") (pintype "input"))
      (node (ref "C37") (pin "1") (pinfunction "1_1") (pintype "input"))
      (node (ref "C38") (pin "1") (pinfunction "1_1") (pintype "input"))
      (node (ref "C39") (pin "1") (pinfunction "1_1") (pintype "input"))
      (node (ref "C40") (pin "1") (pinfunction "1_1") (pintype "input"))
      (node (ref "C41") (pin "1") (pinfunction "1_1") (pintype "input"))
      (node (ref "C42") (pin "1") (pinfunction "1_1") (pintype "input"))
      (node (ref "C43") (pin "1") (pinfunction "1_1") (pintype "input"))
      (node (ref "C44") (pin "1") (pinfunction "1_1") (pintype "input"))
      (node (ref "C45") (pin "1") (pinfunction "1_1") (pintype "input"))
      (node (ref "C46") (pin "1") (pinfunction "1_1") (pintype "input"))
      (node (ref "C47") (pin "1") (pinfunction "1_1") (pintype "input"))
      (node (ref "C48") (pin "1") (pinfunction "1_1") (pintype "input"))
      (node (ref "C49") (pin "1") (pinfunction "1_1") (pintype "input"))
      (node (ref "C5") (pin "1") (pinfunction "1_1") (pintype "input"))
      (node (ref "C50") (pin "1") (pinfunction "1_1") (pintype "input"))
      (node (ref "C51") (pin "1") (pinfunction "1_1") (pintype "input"))
      (node (ref "C52") (pin "1") (pinfunction "1_1") (pintype "input"))
      (node (ref "C53") (pin "1") (pinfunction "1_1") (pintype "input"))
      (node (ref "C54") (pin "1") (pinfunction "1_1") (pintype "input"))
      (node (ref "C55") (pin "1") (pinfunction "1_1") (pintype "input"))
      (node (ref "C56") (pin "1") (pinfunction "1_1") (pintype "input"))
      (node (ref "C57") (pin "1") (pinfunction "1_1") (pintype "input"))
      (node (ref "C58") (pin "1") (pinfunction "1_1") (pintype "input"))
      (node (ref "C59") (pin "1") (pinfunction "1_1") (pintype "input"))
      (node (ref "C60") (pin "1") (pinfunction "1_1") (pintype "input"))
      (node (ref "C61") (pin "1") (pinfunction "1_1") (pintype "input"))
      (node (ref "C62") (pin "1") (pinfunction "1_1") (pintype "input"))
      (node (ref "C63") (pin "1") (pinfunction "1_1") (pintype "input"))
      (node (ref "C64") (pin "1") (pinfunction "1_1") (pintype "input"))
      (node (ref "C65") (pin "1") (pinfunction "1_1") (pintype "input"))
      (node (ref "C66") (pin "1") (pinfunction "1_1") (pintype "input"))
      (node (ref "C67") (pin "1") (pinfunction "1_1") (pintype "input"))
      (node (ref "C68") (pin "1") (pinfunction "1_1") (pintype "input"))
      (node (ref "C69") (pin "1") (pinfunction "1_1") (pintype "input"))
      (node (ref "C70") (pin "1") (pinfunction "1_1") (pintype "input"))
      (node (ref "C71") (pin "1") (pinfunction "1_1") (pintype "input"))
      (node (ref "C72") (pin "1") (pinfunction "1_1") (pintype "input"))
      (node (ref "C73") (pin "1") (pinfunction "1_1") (pintype "input"))
      (node (ref "C74") (pin "1") (pinfunction "1_1") (pintype "input"))
      (node (ref "C75") (pin "1") (pinfunction "1_1") (pintype "input"))
      (node (ref "C76") (pin "1") (pinfunction "1_1") (pintype "input"))
      (node (ref "C77") (pin "1") (pinfunction "1_1") (pintype "input"))
      (node (ref "C78") (pin "1") (pinfunction "1_1") (pintype "input"))
      (node (ref "C79") (pin "1") (pinfunction "1_1") (pintype "input"))
      (node (ref "C8") (pin "1") (pinfunction "1_1") (pintype "input"))
      (node (ref "C80") (pin "1") (pinfunction "1_1") (pintype "input"))
      (node (ref "C81") (pin "1") (pinfunction "1_1") (pintype "input"))
      (node (ref "C82") (pin "1") (pinfunction "1_1") (pintype "input"))
      (node (ref "C83") (pin "1") (pinfunction "1_1") (pintype "input"))
      (node (ref "C84") (pin "1") (pinfunction "1_1") (pintype "input"))
      (node (ref "C85") (pin "1") (pinfunction "1_1") (pintype "input"))
      (node (ref "C86") (pin "1") (pinfunction "1_1") (pintype "input"))
      (node (ref "C87") (pin "1") (pinfunction "1_1") (pintype "input"))
      (node (ref "C88") (pin "1") (pinfunction "1_1") (pintype "input"))
      (node (ref "C89") (pin "1") (pinfunction "1_1") (pintype "input"))
      (node (ref "C90") (pin "1") (pinfunction "1_1") (pintype "input"))
      (node (ref "C91") (pin "1") (pinfunction "1_1") (pintype "input"))
      (node (ref "C92") (pin "1") (pinfunction "1_1") (pintype "input"))
      (node (ref "C93") (pin "1") (pinfunction "1_1") (pintype "input"))
      (node (ref "C94") (pin "1") (pinfunction "1_1") (pintype "input"))
      (node (ref "C95") (pin "1") (pinfunction "1_1") (pintype "input"))
      (node (ref "C96") (pin "1") (pinfunction "1_1") (pintype "input"))
      (node (ref "C97") (pin "1") (pinfunction "1_1") (pintype "input"))
      (node (ref "C98") (pin "1") (pinfunction "1_1") (pintype "input"))
      (node (ref "C99") (pin "1") (pinfunction "1_1") (pintype "input"))
      (node (ref "D1") (pin "2") (pinfunction "A_2") (pintype "unspecified"))
      (node (ref "H1") (pin "1") (pinfunction "1_1") (pintype "input"))
      (node (ref "H10") (pin "1") (pinfunction "1_1") (pintype "input"))
      (node (ref "H11") (pin "1") (pinfunction "1_1") (pintype "input"))
      (node (ref "H12") (pin "1") (pinfunction "1_1") (pintype "input"))
      (node (ref "H13") (pin "1") (pinfunction "1_1") (pintype "input"))
      (node (ref "H14") (pin "1") (pinfunction "1_1") (pintype "input"))
      (node (ref "H15") (pin "1") (pinfunction "1_1") (pintype "input"))
      (node (ref "H16") (pin "1") (pinfunction "1_1") (pintype "input"))
      (node (ref "H17") (pin "1") (pinfunction "1_1") (pintype "input"))
      (node (ref "H18") (pin "1") (pinfunction "1_1") (pintype "input"))
      (node (ref "H19") (pin "1") (pinfunction "1_1") (pintype "input"))
      (node (ref "H2") (pin "1") (pinfunction "1_1") (pintype "input"))
      (node (ref "H20") (pin "1") (pinfunction "1_1") (pintype "input"))
      (node (ref "H21") (pin "1") (pinfunction "1_1") (pintype "input"))
      (node (ref "H3") (pin "1") (pinfunction "1_1") (pintype "input"))
      (node (ref "H4") (pin "1") (pinfunction "1_1") (pintype "input"))
      (node (ref "H5") (pin "1") (pinfunction "1_1") (pintype "input"))
      (node (ref "H6") (pin "1") (pinfunction "1_1") (pintype "input"))
      (node (ref "H7") (pin "1") (pinfunction "1_1") (pintype "input"))
      (node (ref "H8") (pin "1") (pinfunction "1_1") (pintype "input"))
      (node (ref "H9") (pin "1") (pinfunction "1_1") (pintype "input"))
      (node (ref "JP4") (pin "1") (pinfunction "1_1") (pintype "bidirectional"))
      (node (ref "JP5") (pin "1") (pinfunction "1_1") (pintype "bidirectional"))
      (node (ref "LED1") (pin "1") (pinfunction "VDD_1") (pintype "unspecified"))
      (node (ref "LED10") (pin "1") (pinfunction "VDD_1") (pintype "unspecified"))
      (node (ref "LED100") (pin "1") (pinfunction "VDD_1") (pintype "unspecified"))
      (node (ref "LED101") (pin "1") (pinfunction "VDD_1") (pintype "unspecified"))
      (node (ref "LED102") (pin "1") (pinfunction "VDD_1") (pintype "unspecified"))
      (node (ref "LED103") (pin "1") (pinfunction "VDD_1") (pintype "unspecified"))
      (node (ref "LED104") (pin "1") (pinfunction "VDD_1") (pintype "unspecified"))
      (node (ref "LED105") (pin "1") (pinfunction "VDD_1") (pintype "unspecified"))
      (node (ref "LED106") (pin "1") (pinfunction "VDD_1") (pintype "unspecified"))
      (node (ref "LED107") (pin "1") (pinfunction "VDD_1") (pintype "unspecified"))
      (node (ref "LED108") (pin "1") (pinfunction "VDD_1") (pintype "unspecified"))
      (node (ref "LED109") (pin "1") (pinfunction "VDD_1") (pintype "unspecified"))
      (node (ref "LED11") (pin "1") (pinfunction "VDD_1") (pintype "unspecified"))
      (node (ref "LED110") (pin "1") (pinfunction "VDD_1") (pintype "unspecified"))
      (node (ref "LED111") (pin "1") (pinfunction "VDD_1") (pintype "unspecified"))
      (node (ref "LED112") (pin "1") (pinfunction "VDD_1") (pintype "unspecified"))
      (node (ref "LED113") (pin "1") (pinfunction "VDD_1") (pintype "unspecified"))
      (node (ref "LED114") (pin "1") (pinfunction "VDD_1") (pintype "unspecified"))
      (node (ref "LED12") (pin "1") (pinfunction "VDD_1") (pintype "unspecified"))
      (node (ref "LED13") (pin "1") (pinfunction "VDD_1") (pintype "unspecified"))
      (node (ref "LED14") (pin "1") (pinfunction "VDD_1") (pintype "unspecified"))
      (node (ref "LED15") (pin "1") (pinfunction "VDD_1") (pintype "unspecified"))
      (node (ref "LED16") (pin "1") (pinfunction "VDD_1") (pintype "unspecified"))
      (node (ref "LED17") (pin "1") (pinfunction "VDD_1") (pintype "unspecified"))
      (node (ref "LED18") (pin "1") (pinfunction "VDD_1") (pintype "unspecified"))
      (node (ref "LED19") (pin "1") (pinfunction "VDD_1") (pintype "unspecified"))
      (node (ref "LED20") (pin "1") (pinfunction "VDD_1") (pintype "unspecified"))
      (node (ref "LED21") (pin "1") (pinfunction "VDD_1") (pintype "unspecified"))
      (node (ref "LED22") (pin "1") (pinfunction "VDD_1") (pintype "unspecified"))
      (node (ref "LED23") (pin "1") (pinfunction "VDD_1") (pintype "unspecified"))
      (node (ref "LED24") (pin "1") (pinfunction "VDD_1") (pintype "unspecified"))
      (node (ref "LED25") (pin "1") (pinfunction "VDD_1") (pintype "unspecified"))
      (node (ref "LED26") (pin "1") (pinfunction "VDD_1") (pintype "unspecified"))
      (node (ref "LED27") (pin "1") (pinfunction "VDD_1") (pintype "unspecified"))
      (node (ref "LED28") (pin "1") (pinfunction "VDD_1") (pintype "unspecified"))
      (node (ref "LED29") (pin "1") (pinfunction "VDD_1") (pintype "unspecified"))
      (node (ref "LED3") (pin "1") (pinfunction "VDD_1") (pintype "unspecified"))
      (node (ref "LED30") (pin "1") (pinfunction "VDD_1") (pintype "unspecified"))
      (node (ref "LED31") (pin "1") (pinfunction "VDD_1") (pintype "unspecified"))
      (node (ref "LED32") (pin "1") (pinfunction "VDD_1") (pintype "unspecified"))
      (node (ref "LED33") (pin "1") (pinfunction "VDD_1") (pintype "unspecified"))
      (node (ref "LED34") (pin "1") (pinfunction "VDD_1") (pintype "unspecified"))
      (node (ref "LED35") (pin "1") (pinfunction "VDD_1") (pintype "unspecified"))
      (node (ref "LED36") (pin "1") (pinfunction "VDD_1") (pintype "unspecified"))
      (node (ref "LED37") (pin "1") (pinfunction "VDD_1") (pintype "unspecified"))
      (node (ref "LED38") (pin "1") (pinfunction "VDD_1") (pintype "unspecified"))
      (node (ref "LED39") (pin "1") (pinfunction "VDD_1") (pintype "unspecified"))
      (node (ref "LED4") (pin "1") (pinfunction "VDD_1") (pintype "unspecified"))
      (node (ref "LED40") (pin "1") (pinfunction "VDD_1") (pintype "unspecified"))
      (node (ref "LED41") (pin "1") (pinfunction "VDD_1") (pintype "unspecified"))
      (node (ref "LED42") (pin "1") (pinfunction "VDD_1") (pintype "unspecified"))
      (node (ref "LED43") (pin "1") (pinfunction "VDD_1") (pintype "unspecified"))
      (node (ref "LED44") (pin "1") (pinfunction "VDD_1") (pintype "unspecified"))
      (node (ref "LED45") (pin "1") (pinfunction "VDD_1") (pintype "unspecified"))
      (node (ref "LED46") (pin "1") (pinfunction "VDD_1") (pintype "unspecified"))
      (node (ref "LED47") (pin "1") (pinfunction "VDD_1") (pintype "unspecified"))
      (node (ref "LED48") (pin "1") (pinfunction "VDD_1") (pintype "unspecified"))
      (node (ref "LED49") (pin "1") (pinfunction "VDD_1") (pintype "unspecified"))
      (node (ref "LED5") (pin "1") (pinfunction "VDD_1") (pintype "unspecified"))
      (node (ref "LED50") (pin "1") (pinfunction "VDD_1") (pintype "unspecified"))
      (node (ref "LED51") (pin "1") (pinfunction "VDD_1") (pintype "unspecified"))
      (node (ref "LED52") (pin "1") (pinfunction "VDD_1") (pintype "unspecified"))
      (node (ref "LED53") (pin "1") (pinfunction "VDD_1") (pintype "unspecified"))
      (node (ref "LED54") (pin "1") (pinfunction "VDD_1") (pintype "unspecified"))
      (node (ref "LED55") (pin "1") (pinfunction "VDD_1") (pintype "unspecified"))
      (node (ref "LED56") (pin "1") (pinfunction "VDD_1") (pintype "unspecified"))
      (node (ref "LED57") (pin "1") (pinfunction "VDD_1") (pintype "unspecified"))
      (node (ref "LED58") (pin "1") (pinfunction "VDD_1") (pintype "unspecified"))
      (node (ref "LED59") (pin "1") (pinfunction "VDD_1") (pintype "unspecified"))
      (node (ref "LED6") (pin "1") (pinfunction "VDD_1") (pintype "unspecified"))
      (node (ref "LED60") (pin "1") (pinfunction "VDD_1") (pintype "unspecified"))
      (node (ref "LED61") (pin "1") (pinfunction "VDD_1") (pintype "unspecified"))
      (node (ref "LED62") (pin "1") (pinfunction "VDD_1") (pintype "unspecified"))
      (node (ref "LED63") (pin "1") (pinfunction "VDD_1") (pintype "unspecified"))
      (node (ref "LED64") (pin "1") (pinfunction "VDD_1") (pintype "unspecified"))
      (node (ref "LED65") (pin "1") (pinfunction "VDD_1") (pintype "unspecified"))
      (node (ref "LED66") (pin "1") (pinfunction "VDD_1") (pintype "unspecified"))
      (node (ref "LED67") (pin "1") (pinfunction "VDD_1") (pintype "unspecified"))
      (node (ref "LED68") (pin "1") (pinfunction "VDD_1") (pintype "unspecified"))
      (node (ref "LED69") (pin "1") (pinfunction "VDD_1") (pintype "unspecified"))
      (node (ref "LED7") (pin "1") (pinfunction "VDD_1") (pintype "unspecified"))
      (node (ref "LED70") (pin "1") (pinfunction "VDD_1") (pintype "unspecified"))
      (node (ref "LED71") (pin "1") (pinfunction "VDD_1") (pintype "unspecified"))
      (node (ref "LED72") (pin "1") (pinfunction "VDD_1") (pintype "unspecified"))
      (node (ref "LED73") (pin "1") (pinfunction "VDD_1") (pintype "unspecified"))
      (node (ref "LED74") (pin "1") (pinfunction "VDD_1") (pintype "unspecified"))
      (node (ref "LED75") (pin "1") (pinfunction "VDD_1") (pintype "unspecified"))
      (node (ref "LED76") (pin "1") (pinfunction "VDD_1") (pintype "unspecified"))
      (node (ref "LED77") (pin "1") (pinfunction "VDD_1") (pintype "unspecified"))
      (node (ref "LED78") (pin "1") (pinfunction "VDD_1") (pintype "unspecified"))
      (node (ref "LED79") (pin "1") (pinfunction "VDD_1") (pintype "unspecified"))
      (node (ref "LED8") (pin "1") (pinfunction "VDD_1") (pintype "unspecified"))
      (node (ref "LED80") (pin "1") (pinfunction "VDD_1") (pintype "unspecified"))
      (node (ref "LED81") (pin "1") (pinfunction "VDD_1") (pintype "unspecified"))
      (node (ref "LED82") (pin "1") (pinfunction "VDD_1") (pintype "unspecified"))
      (node (ref "LED83") (pin "1") (pinfunction "VDD_1") (pintype "unspecified"))
      (node (ref "LED84") (pin "1") (pinfunction "VDD_1") (pintype "unspecified"))
      (node (ref "LED85") (pin "1") (pinfunction "VDD_1") (pintype "unspecified"))
      (node (ref "LED86") (pin "1") (pinfunction "VDD_1") (pintype "unspecified"))
      (node (ref "LED87") (pin "1") (pinfunction "VDD_1") (pintype "unspecified"))
      (node (ref "LED88") (pin "1") (pinfunction "VDD_1") (pintype "unspecified"))
      (node (ref "LED89") (pin "1") (pinfunction "VDD_1") (pintype "unspecified"))
      (node (ref "LED9") (pin "1") (pinfunction "VDD_1") (pintype "unspecified"))
      (node (ref "LED90") (pin "1") (pinfunction "VDD_1") (pintype "unspecified"))
      (node (ref "LED91") (pin "1") (pinfunction "VDD_1") (pintype "unspecified"))
      (node (ref "LED92") (pin "1") (pinfunction "VDD_1") (pintype "unspecified"))
      (node (ref "LED93") (pin "1") (pinfunction "VDD_1") (pintype "unspecified"))
      (node (ref "LED94") (pin "1") (pinfunction "VDD_1") (pintype "unspecified"))
      (node (ref "LED95") (pin "1") (pinfunction "VDD_1") (pintype "unspecified"))
      (node (ref "LED96") (pin "1") (pinfunction "VDD_1") (pintype "unspecified"))
      (node (ref "LED97") (pin "1") (pinfunction "VDD_1") (pintype "unspecified"))
      (node (ref "LED98") (pin "1") (pinfunction "VDD_1") (pintype "unspecified"))
      (node (ref "LED99") (pin "1") (pinfunction "VDD_1") (pintype "unspecified"))
      (node (ref "PWRRST") (pin "2") (pinfunction "2_2") (pintype "unspecified"))
      (node (ref "RPUSB") (pin "1") (pinfunction "1_1") (pintype "unspecified"))
      (node (ref "U12") (pin "1") (pinfunction "VBUS_OUT_1") (pintype "unspecified"))
      (node (ref "U12") (pin "2") (pinfunction "VBUS_OUT_2") (pintype "unspecified"))
      (node (ref "U2") (pin "3") (pinfunction "In_3") (pintype "unspecified"))
      (node (ref "U7") (pin "1") (pinfunction "VCCA_1") (pintype "unspecified"))
    )
    (net (code "3") (name "5VDIN") (class "Default")
      (node (ref "LED115") (pin "4") (pinfunction "DIN_4") (pintype "unspecified"))
      (node (ref "R10") (pin "1") (pinfunction "1_1") (pintype "input"))
    )
    (net (code "4") (name "ADC0") (class "Default")
      (node (ref "QU1") (pin "38") (pinfunction "GPIO26_ADC0_38") (pintype "bidirectional"))
    )
    (net (code "5") (name "ADC1") (class "Default")
      (node (ref "QU1") (pin "39") (pinfunction "GPIO27_ADC1_39") (pintype "bidirectional"))
    )
    (net (code "6") (name "ADC2") (class "Default")
      (node (ref "QU1") (pin "40") (pinfunction "GPIO28_ADC2_40") (pintype "bidirectional"))
    )
    (net (code "7") (name "ADC3") (class "Default")
      (node (ref "QU1") (pin "41") (pinfunction "GPIO29_ADC3_41") (pintype "bidirectional"))
    )
    (net (code "8") (name "GND") (class "Default")
      (node (ref "BT1") (pin "2") (pinfunction "2_2") (pintype "input"))
      (node (ref "BT2") (pin "2") (pinfunction "2_2") (pintype "input"))
      (node (ref "C1") (pin "2") (pinfunction "2_2") (pintype "input"))
      (node (ref "C10") (pin "1") (pinfunction "1_1") (pintype "input"))
      (node (ref "C100") (pin "2") (pinfunction "2_2") (pintype "input"))
      (node (ref "C101") (pin "2") (pinfunction "2_2") (pintype "input"))
      (node (ref "C102") (pin "2") (pinfunction "2_2") (pintype "input"))
      (node (ref "C103") (pin "2") (pinfunction "2_2") (pintype "input"))
      (node (ref "C104") (pin "2") (pinfunction "2_2") (pintype "input"))
      (node (ref "C105") (pin "2") (pinfunction "2_2") (pintype "input"))
      (node (ref "C106") (pin "2") (pinfunction "2_2") (pintype "input"))
      (node (ref "C107") (pin "2") (pinfunction "2_2") (pintype "input"))
      (node (ref "C108") (pin "2") (pinfunction "2_2") (pintype "input"))
      (node (ref "C109") (pin "2") (pinfunction "2_2") (pintype "input"))
      (node (ref "C11") (pin "2") (pinfunction "2_2") (pintype "input"))
      (node (ref "C110") (pin "2") (pinfunction "2_2") (pintype "input"))
      (node (ref "C111") (pin "2") (pinfunction "2_2") (pintype "input"))
      (node (ref "C112") (pin "2") (pinfunction "2_2") (pintype "input"))
      (node (ref "C113") (pin "2") (pinfunction "2_2") (pintype "input"))
      (node (ref "C114") (pin "2") (pinfunction "2_2") (pintype "input"))
      (node (ref "C115") (pin "2") (pinfunction "2_2") (pintype "input"))
      (node (ref "C116") (pin "2") (pinfunction "2_2") (pintype "input"))
      (node (ref "C117") (pin "2") (pinfunction "2_2") (pintype "input"))
      (node (ref "C118") (pin "2") (pinfunction "2_2") (pintype "input"))
      (node (ref "C119") (pin "2") (pinfunction "2_2") (pintype "input"))
      (node (ref "C12") (pin "2") (pinfunction "2_2") (pintype "input"))
      (node (ref "C120") (pin "2") (pinfunction "2_2") (pintype "input"))
      (node (ref "C121") (pin "2") (pinfunction "2_2") (pintype "input"))
      (node (ref "C122") (pin "2") (pinfunction "2_2") (pintype "input"))
      (node (ref "C123") (pin "2") (pinfunction "2_2") (pintype "input"))
      (node (ref "C124") (pin "2") (pinfunction "2_2") (pintype "input"))
      (node (ref "C125") (pin "1") (pinfunction "1_1") (pintype "input"))
      (node (ref "C126") (pin "1") (pinfunction "1_1") (pintype "input"))
      (node (ref "C127") (pin "1") (pinfunction "1_1") (pintype "input"))
      (node (ref "C128") (pin "1") (pinfunction "1_1") (pintype "input"))
      (node (ref "C129") (pin "2") (pinfunction "2_2") (pintype "input"))
      (node (ref "C13") (pin "2") (pinfunction "2_2") (pintype "input"))
      (node (ref "C130") (pin "2") (pinfunction "2_2") (pintype "input"))
      (node (ref "C131") (pin "1") (pinfunction "1_1") (pintype "input"))
      (node (ref "C132") (pin "1") (pinfunction "1_1") (pintype "input"))
      (node (ref "C133") (pin "1") (pinfunction "1_1") (pintype "input"))
      (node (ref "C134") (pin "2") (pinfunction "2_2") (pintype "unspecified"))
      (node (ref "C135") (pin "1") (pinfunction "1_1") (pintype "unspecified"))
      (node (ref "C136") (pin "2") (pinfunction "2_2") (pintype "input"))
      (node (ref "C137") (pin "2") (pinfunction "2_2") (pintype "input"))
      (node (ref "C138") (pin "2") (pinfunction "2_2") (pintype "input"))
      (node (ref "C139") (pin "1") (pinfunction "1_1") (pintype "input"))
      (node (ref "C14") (pin "2") (pinfunction "2_2") (pintype "input"))
      (node (ref "C15") (pin "2") (pinfunction "2_2") (pintype "input"))
      (node (ref "C16") (pin "2") (pinfunction "2_2") (pintype "input"))
      (node (ref "C17") (pin "2") (pinfunction "2_2") (pintype "input"))
      (node (ref "C18") (pin "2") (pinfunction "2_2") (pintype "input"))
      (node (ref "C19") (pin "2") (pinfunction "2_2") (pintype "input"))
      (node (ref "C2") (pin "1") (pinfunction "1_1") (pintype "input"))
      (node (ref "C20") (pin "2") (pinfunction "2_2") (pintype "input"))
      (node (ref "C21") (pin "2") (pinfunction "2_2") (pintype "input"))
      (node (ref "C22") (pin "2") (pinfunction "2_2") (pintype "input"))
      (node (ref "C23") (pin "2") (pinfunction "2_2") (pintype "input"))
      (node (ref "C24") (pin "2") (pinfunction "2_2") (pintype "input"))
      (node (ref "C25") (pin "2") (pinfunction "2_2") (pintype "input"))
      (node (ref "C26") (pin "2") (pinfunction "2_2") (pintype "input"))
      (node (ref "C27") (pin "2") (pinfunction "2_2") (pintype "input"))
      (node (ref "C28") (pin "2") (pinfunction "2_2") (pintype "input"))
      (node (ref "C29") (pin "2") (pinfunction "2_2") (pintype "input"))
      (node (ref "C3") (pin "2") (pinfunction "2_2") (pintype "input"))
      (node (ref "C30") (pin "2") (pinfunction "2_2") (pintype "input"))
      (node (ref "C31") (pin "2") (pinfunction "2_2") (pintype "input"))
      (node (ref "C32") (pin "2") (pinfunction "2_2") (pintype "input"))
      (node (ref "C33") (pin "2") (pinfunction "2_2") (pintype "input"))
      (node (ref "C34") (pin "2") (pinfunction "2_2") (pintype "input"))
      (node (ref "C35") (pin "2") (pinfunction "2_2") (pintype "input"))
      (node (ref "C36") (pin "2") (pinfunction "2_2") (pintype "input"))
      (node (ref "C37") (pin "2") (pinfunction "2_2") (pintype "input"))
      (node (ref "C38") (pin "2") (pinfunction "2_2") (pintype "input"))
      (node (ref "C39") (pin "2") (pinfunction "2_2") (pintype "input"))
      (node (ref "C4") (pin "2") (pinfunction "2_2") (pintype "input"))
      (node (ref "C40") (pin "2") (pinfunction "2_2") (pintype "input"))
      (node (ref "C41") (pin "2") (pinfunction "2_2") (pintype "input"))
      (node (ref "C42") (pin "2") (pinfunction "2_2") (pintype "input"))
      (node (ref "C43") (pin "2") (pinfunction "2_2") (pintype "input"))
      (node (ref "C44") (pin "2") (pinfunction "2_2") (pintype "input"))
      (node (ref "C45") (pin "2") (pinfunction "2_2") (pintype "input"))
      (node (ref "C46") (pin "2") (pinfunction "2_2") (pintype "input"))
      (node (ref "C47") (pin "2") (pinfunction "2_2") (pintype "input"))
      (node (ref "C48") (pin "2") (pinfunction "2_2") (pintype "input"))
      (node (ref "C49") (pin "2") (pinfunction "2_2") (pintype "input"))
      (node (ref "C5") (pin "2") (pinfunction "2_2") (pintype "input"))
      (node (ref "C50") (pin "2") (pinfunction "2_2") (pintype "input"))
      (node (ref "C51") (pin "2") (pinfunction "2_2") (pintype "input"))
      (node (ref "C52") (pin "2") (pinfunction "2_2") (pintype "input"))
      (node (ref "C53") (pin "2") (pinfunction "2_2") (pintype "input"))
      (node (ref "C54") (pin "2") (pinfunction "2_2") (pintype "input"))
      (node (ref "C55") (pin "2") (pinfunction "2_2") (pintype "input"))
      (node (ref "C56") (pin "2") (pinfunction "2_2") (pintype "input"))
      (node (ref "C57") (pin "2") (pinfunction "2_2") (pintype "input"))
      (node (ref "C58") (pin "2") (pinfunction "2_2") (pintype "input"))
      (node (ref "C59") (pin "2") (pinfunction "2_2") (pintype "input"))
      (node (ref "C6") (pin "1") (pinfunction "1_1") (pintype "input"))
      (node (ref "C60") (pin "2") (pinfunction "2_2") (pintype "input"))
      (node (ref "C61") (pin "2") (pinfunction "2_2") (pintype "input"))
      (node (ref "C62") (pin "2") (pinfunction "2_2") (pintype "input"))
      (node (ref "C63") (pin "2") (pinfunction "2_2") (pintype "input"))
      (node (ref "C64") (pin "2") (pinfunction "2_2") (pintype "input"))
      (node (ref "C65") (pin "2") (pinfunction "2_2") (pintype "input"))
      (node (ref "C66") (pin "2") (pinfunction "2_2") (pintype "input"))
      (node (ref "C67") (pin "2") (pinfunction "2_2") (pintype "input"))
      (node (ref "C68") (pin "2") (pinfunction "2_2") (pintype "input"))
      (node (ref "C69") (pin "2") (pinfunction "2_2") (pintype "input"))
      (node (ref "C7") (pin "2") (pinfunction "2_2") (pintype "input"))
      (node (ref "C70") (pin "2") (pinfunction "2_2") (pintype "input"))
      (node (ref "C71") (pin "2") (pinfunction "2_2") (pintype "input"))
      (node (ref "C72") (pin "2") (pinfunction "2_2") (pintype "input"))
      (node (ref "C73") (pin "2") (pinfunction "2_2") (pintype "input"))
      (node (ref "C74") (pin "2") (pinfunction "2_2") (pintype "input"))
      (node (ref "C75") (pin "2") (pinfunction "2_2") (pintype "input"))
      (node (ref "C76") (pin "2") (pinfunction "2_2") (pintype "input"))
      (node (ref "C77") (pin "2") (pinfunction "2_2") (pintype "input"))
      (node (ref "C78") (pin "2") (pinfunction "2_2") (pintype "input"))
      (node (ref "C79") (pin "2") (pinfunction "2_2") (pintype "input"))
      (node (ref "C8") (pin "2") (pinfunction "2_2") (pintype "input"))
      (node (ref "C80") (pin "2") (pinfunction "2_2") (pintype "input"))
      (node (ref "C81") (pin "2") (pinfunction "2_2") (pintype "input"))
      (node (ref "C82") (pin "2") (pinfunction "2_2") (pintype "input"))
      (node (ref "C83") (pin "2") (pinfunction "2_2") (pintype "input"))
      (node (ref "C84") (pin "2") (pinfunction "2_2") (pintype "input"))
      (node (ref "C85") (pin "2") (pinfunction "2_2") (pintype "input"))
      (node (ref "C86") (pin "2") (pinfunction "2_2") (pintype "input"))
      (node (ref "C87") (pin "2") (pinfunction "2_2") (pintype "input"))
      (node (ref "C88") (pin "2") (pinfunction "2_2") (pintype "input"))
      (node (ref "C89") (pin "2") (pinfunction "2_2") (pintype "input"))
      (node (ref "C9") (pin "2") (pinfunction "2_2") (pintype "input"))
      (node (ref "C90") (pin "2") (pinfunction "2_2") (pintype "input"))
      (node (ref "C91") (pin "2") (pinfunction "2_2") (pintype "input"))
      (node (ref "C92") (pin "2") (pinfunction "2_2") (pintype "input"))
      (node (ref "C93") (pin "2") (pinfunction "2_2") (pintype "input"))
      (node (ref "C94") (pin "2") (pinfunction "2_2") (pintype "input"))
      (node (ref "C95") (pin "2") (pinfunction "2_2") (pintype "input"))
      (node (ref "C96") (pin "2") (pinfunction "2_2") (pintype "input"))
      (node (ref "C97") (pin "2") (pinfunction "2_2") (pintype "input"))
      (node (ref "C98") (pin "2") (pinfunction "2_2") (pintype "input"))
      (node (ref "C99") (pin "2") (pinfunction "2_2") (pintype "input"))
      (node (ref "ESPRST") (pin "2") (pinfunction "2_2") (pintype "unspecified"))
      (node (ref "H1") (pin "3") (pinfunction "3_3") (pintype "input"))
      (node (ref "H10") (pin "3") (pinfunction "3_3") (pintype "input"))
      (node (ref "H11") (pin "3") (pinfunction "3_3") (pintype "input"))
      (node (ref "H12") (pin "3") (pinfunction "3_3") (pintype "input"))
      (node (ref "H13") (pin "3") (pinfunction "3_3") (pintype "input"))
      (node (ref "H14") (pin "3") (pinfunction "3_3") (pintype "input"))
      (node (ref "H15") (pin "3") (pinfunction "3_3") (pintype "input"))
      (node (ref "H16") (pin "3") (pinfunction "3_3") (pintype "input"))
      (node (ref "H17") (pin "3") (pinfunction "3_3") (pintype "input"))
      (node (ref "H18") (pin "3") (pinfunction "3_3") (pintype "input"))
      (node (ref "H19") (pin "3") (pinfunction "3_3") (pintype "input"))
      (node (ref "H2") (pin "3") (pinfunction "3_3") (pintype "input"))
      (node (ref "H20") (pin "3") (pinfunction "3_3") (pintype "input"))
      (node (ref "H21") (pin "3") (pinfunction "3_3") (pintype "input"))
      (node (ref "H22") (pin "1") (pinfunction "1_1") (pintype "input"))
      (node (ref "H3") (pin "3") (pinfunction "3_3") (pintype "input"))
      (node (ref "H4") (pin "3") (pinfunction "3_3") (pintype "input"))
      (node (ref "H5") (pin "3") (pinfunction "3_3") (pintype "input"))
      (node (ref "H6") (pin "3") (pinfunction "3_3") (pintype "input"))
      (node (ref "H7") (pin "3") (pinfunction "3_3") (pintype "input"))
      (node (ref "H8") (pin "3") (pinfunction "3_3") (pintype "input"))
      (node (ref "H9") (pin "3") (pinfunction "3_3") (pintype "input"))
      (node (ref "LED1") (pin "3") (pinfunction "VSS_3") (pintype "unspecified"))
      (node (ref "LED10") (pin "3") (pinfunction "VSS_3") (pintype "unspecified"))
      (node (ref "LED100") (pin "3") (pinfunction "VSS_3") (pintype "unspecified"))
      (node (ref "LED101") (pin "3") (pinfunction "VSS_3") (pintype "unspecified"))
      (node (ref "LED102") (pin "3") (pinfunction "VSS_3") (pintype "unspecified"))
      (node (ref "LED103") (pin "3") (pinfunction "VSS_3") (pintype "unspecified"))
      (node (ref "LED104") (pin "3") (pinfunction "VSS_3") (pintype "unspecified"))
      (node (ref "LED105") (pin "3") (pinfunction "VSS_3") (pintype "unspecified"))
      (node (ref "LED106") (pin "3") (pinfunction "VSS_3") (pintype "unspecified"))
      (node (ref "LED107") (pin "3") (pinfunction "VSS_3") (pintype "unspecified"))
      (node (ref "LED108") (pin "3") (pinfunction "VSS_3") (pintype "unspecified"))
      (node (ref "LED109") (pin "3") (pinfunction "VSS_3") (pintype "unspecified"))
      (node (ref "LED11") (pin "3") (pinfunction "VSS_3") (pintype "unspecified"))
      (node (ref "LED110") (pin "3") (pinfunction "VSS_3") (pintype "unspecified"))
      (node (ref "LED111") (pin "3") (pinfunction "VSS_3") (pintype "unspecified"))
      (node (ref "LED112") (pin "3") (pinfunction "VSS_3") (pintype "unspecified"))
      (node (ref "LED113") (pin "3") (pinfunction "VSS_3") (pintype "unspecified"))
      (node (ref "LED114") (pin "3") (pinfunction "VSS_3") (pintype "unspecified"))
      (node (ref "LED115") (pin "3") (pinfunction "VSS_3") (pintype "unspecified"))
      (node (ref "LED116") (pin "1") (pinfunction "-_1") (pintype "unspecified"))
      (node (ref "LED12") (pin "3") (pinfunction "VSS_3") (pintype "unspecified"))
      (node (ref "LED13") (pin "3") (pinfunction "VSS_3") (pintype "unspecified"))
      (node (ref "LED14") (pin "3") (pinfunction "VSS_3") (pintype "unspecified"))
      (node (ref "LED15") (pin "3") (pinfunction "VSS_3") (pintype "unspecified"))
      (node (ref "LED16") (pin "3") (pinfunction "VSS_3") (pintype "unspecified"))
      (node (ref "LED17") (pin "3") (pinfunction "VSS_3") (pintype "unspecified"))
      (node (ref "LED18") (pin "3") (pinfunction "VSS_3") (pintype "unspecified"))
      (node (ref "LED19") (pin "3") (pinfunction "VSS_3") (pintype "unspecified"))
      (node (ref "LED20") (pin "3") (pinfunction "VSS_3") (pintype "unspecified"))
      (node (ref "LED21") (pin "3") (pinfunction "VSS_3") (pintype "unspecified"))
      (node (ref "LED22") (pin "3") (pinfunction "VSS_3") (pintype "unspecified"))
      (node (ref "LED23") (pin "3") (pinfunction "VSS_3") (pintype "unspecified"))
      (node (ref "LED24") (pin "3") (pinfunction "VSS_3") (pintype "unspecified"))
      (node (ref "LED25") (pin "3") (pinfunction "VSS_3") (pintype "unspecified"))
      (node (ref "LED26") (pin "3") (pinfunction "VSS_3") (pintype "unspecified"))
      (node (ref "LED27") (pin "3") (pinfunction "VSS_3") (pintype "unspecified"))
      (node (ref "LED28") (pin "3") (pinfunction "VSS_3") (pintype "unspecified"))
      (node (ref "LED29") (pin "3") (pinfunction "VSS_3") (pintype "unspecified"))
      (node (ref "LED3") (pin "3") (pinfunction "VSS_3") (pintype "unspecified"))
      (node (ref "LED30") (pin "3") (pinfunction "VSS_3") (pintype "unspecified"))
      (node (ref "LED31") (pin "3") (pinfunction "VSS_3") (pintype "unspecified"))
      (node (ref "LED32") (pin "3") (pinfunction "VSS_3") (pintype "unspecified"))
      (node (ref "LED33") (pin "3") (pinfunction "VSS_3") (pintype "unspecified"))
      (node (ref "LED34") (pin "3") (pinfunction "VSS_3") (pintype "unspecified"))
      (node (ref "LED35") (pin "3") (pinfunction "VSS_3") (pintype "unspecified"))
      (node (ref "LED36") (pin "3") (pinfunction "VSS_3") (pintype "unspecified"))
      (node (ref "LED37") (pin "3") (pinfunction "VSS_3") (pintype "unspecified"))
      (node (ref "LED38") (pin "3") (pinfunction "VSS_3") (pintype "unspecified"))
      (node (ref "LED39") (pin "3") (pinfunction "VSS_3") (pintype "unspecified"))
      (node (ref "LED4") (pin "3") (pinfunction "VSS_3") (pintype "unspecified"))
      (node (ref "LED40") (pin "3") (pinfunction "VSS_3") (pintype "unspecified"))
      (node (ref "LED41") (pin "3") (pinfunction "VSS_3") (pintype "unspecified"))
      (node (ref "LED42") (pin "3") (pinfunction "VSS_3") (pintype "unspecified"))
      (node (ref "LED43") (pin "3") (pinfunction "VSS_3") (pintype "unspecified"))
      (node (ref "LED44") (pin "3") (pinfunction "VSS_3") (pintype "unspecified"))
      (node (ref "LED45") (pin "3") (pinfunction "VSS_3") (pintype "unspecified"))
      (node (ref "LED46") (pin "3") (pinfunction "VSS_3") (pintype "unspecified"))
      (node (ref "LED47") (pin "3") (pinfunction "VSS_3") (pintype "unspecified"))
      (node (ref "LED48") (pin "3") (pinfunction "VSS_3") (pintype "unspecified"))
      (node (ref "LED49") (pin "3") (pinfunction "VSS_3") (pintype "unspecified"))
      (node (ref "LED5") (pin "3") (pinfunction "VSS_3") (pintype "unspecified"))
      (node (ref "LED50") (pin "3") (pinfunction "VSS_3") (pintype "unspecified"))
      (node (ref "LED51") (pin "3") (pinfunction "VSS_3") (pintype "unspecified"))
      (node (ref "LED52") (pin "3") (pinfunction "VSS_3") (pintype "unspecified"))
      (node (ref "LED53") (pin "3") (pinfunction "VSS_3") (pintype "unspecified"))
      (node (ref "LED54") (pin "3") (pinfunction "VSS_3") (pintype "unspecified"))
      (node (ref "LED55") (pin "3") (pinfunction "VSS_3") (pintype "unspecified"))
      (node (ref "LED56") (pin "3") (pinfunction "VSS_3") (pintype "unspecified"))
      (node (ref "LED57") (pin "3") (pinfunction "VSS_3") (pintype "unspecified"))
      (node (ref "LED58") (pin "3") (pinfunction "VSS_3") (pintype "unspecified"))
      (node (ref "LED59") (pin "3") (pinfunction "VSS_3") (pintype "unspecified"))
      (node (ref "LED6") (pin "3") (pinfunction "VSS_3") (pintype "unspecified"))
      (node (ref "LED60") (pin "3") (pinfunction "VSS_3") (pintype "unspecified"))
      (node (ref "LED61") (pin "3") (pinfunction "VSS_3") (pintype "unspecified"))
      (node (ref "LED62") (pin "3") (pinfunction "VSS_3") (pintype "unspecified"))
      (node (ref "LED63") (pin "3") (pinfunction "VSS_3") (pintype "unspecified"))
      (node (ref "LED64") (pin "3") (pinfunction "VSS_3") (pintype "unspecified"))
      (node (ref "LED65") (pin "3") (pinfunction "VSS_3") (pintype "unspecified"))
      (node (ref "LED66") (pin "3") (pinfunction "VSS_3") (pintype "unspecified"))
      (node (ref "LED67") (pin "3") (pinfunction "VSS_3") (pintype "unspecified"))
      (node (ref "LED68") (pin "3") (pinfunction "VSS_3") (pintype "unspecified"))
      (node (ref "LED69") (pin "3") (pinfunction "VSS_3") (pintype "unspecified"))
      (node (ref "LED7") (pin "3") (pinfunction "VSS_3") (pintype "unspecified"))
      (node (ref "LED70") (pin "3") (pinfunction "VSS_3") (pintype "unspecified"))
      (node (ref "LED71") (pin "3") (pinfunction "VSS_3") (pintype "unspecified"))
      (node (ref "LED72") (pin "3") (pinfunction "VSS_3") (pintype "unspecified"))
      (node (ref "LED73") (pin "3") (pinfunction "VSS_3") (pintype "unspecified"))
      (node (ref "LED74") (pin "3") (pinfunction "VSS_3") (pintype "unspecified"))
      (node (ref "LED75") (pin "3") (pinfunction "VSS_3") (pintype "unspecified"))
      (node (ref "LED76") (pin "3") (pinfunction "VSS_3") (pintype "unspecified"))
      (node (ref "LED77") (pin "3") (pinfunction "VSS_3") (pintype "unspecified"))
      (node (ref "LED78") (pin "3") (pinfunction "VSS_3") (pintype "unspecified"))
      (node (ref "LED79") (pin "3") (pinfunction "VSS_3") (pintype "unspecified"))
      (node (ref "LED8") (pin "3") (pinfunction "VSS_3") (pintype "unspecified"))
      (node (ref "LED80") (pin "3") (pinfunction "VSS_3") (pintype "unspecified"))
      (node (ref "LED81") (pin "3") (pinfunction "VSS_3") (pintype "unspecified"))
      (node (ref "LED82") (pin "3") (pinfunction "VSS_3") (pintype "unspecified"))
      (node (ref "LED83") (pin "3") (pinfunction "VSS_3") (pintype "unspecified"))
      (node (ref "LED84") (pin "3") (pinfunction "VSS_3") (pintype "unspecified"))
      (node (ref "LED85") (pin "3") (pinfunction "VSS_3") (pintype "unspecified"))
      (node (ref "LED86") (pin "3") (pinfunction "VSS_3") (pintype "unspecified"))
      (node (ref "LED87") (pin "3") (pinfunction "VSS_3") (pintype "unspecified"))
      (node (ref "LED88") (pin "3") (pinfunction "VSS_3") (pintype "unspecified"))
      (node (ref "LED89") (pin "3") (pinfunction "VSS_3") (pintype "unspecified"))
      (node (ref "LED9") (pin "3") (pinfunction "VSS_3") (pintype "unspecified"))
      (node (ref "LED90") (pin "3") (pinfunction "VSS_3") (pintype "unspecified"))
      (node (ref "LED91") (pin "3") (pinfunction "VSS_3") (pintype "unspecified"))
      (node (ref "LED92") (pin "3") (pinfunction "VSS_3") (pintype "unspecified"))
      (node (ref "LED93") (pin "3") (pinfunction "VSS_3") (pintype "unspecified"))
      (node (ref "LED94") (pin "3") (pinfunction "VSS_3") (pintype "unspecified"))
      (node (ref "LED95") (pin "3") (pinfunction "VSS_3") (pintype "unspecified"))
      (node (ref "LED96") (pin "3") (pinfunction "VSS_3") (pintype "unspecified"))
      (node (ref "LED97") (pin "3") (pinfunction "VSS_3") (pintype "unspecified"))
      (node (ref "LED98") (pin "3") (pinfunction "VSS_3") (pintype "unspecified"))
      (node (ref "LED99") (pin "3") (pinfunction "VSS_3") (pintype "unspecified"))
      (node (ref "P1") (pin "5") (pinfunction "5_5") (pintype "unspecified"))
      (node (ref "P2") (pin "1") (pinfunction "1_1") (pintype "unspecified"))
      (node (ref "QBOOT") (pin "4") (pinfunction "4_4") (pintype "unspecified"))
      (node (ref "QU1") (pin "19") (pinfunction "TESTEN_19") (pintype "unspecified"))
      (node (ref "QU1") (pin "57") (pinfunction "GND_57") (pintype "bidirectional"))
      (node (ref "QU2") (pin "4") (pinfunction "GND_4") (pintype "unspecified"))
      (node (ref "QX1") (pin "2") (pinfunction "GND_2") (pintype "unspecified"))
      (node (ref "QX1") (pin "4") (pinfunction "GND_4") (pintype "unspecified"))
      (node (ref "R1") (pin "2") (pinfunction "2_2") (pintype "unspecified"))
      (node (ref "R16") (pin "1") (pinfunction "1_1") (pintype "input"))
      (node (ref "R17") (pin "1") (pinfunction "1_1") (pintype "input"))
      (node (ref "R19") (pin "1") (pinfunction "1_1") (pintype "input"))
      (node (ref "R23") (pin "1") (pinfunction "1_1") (pintype "input"))
      (node (ref "RPRST") (pin "4") (pinfunction "4_4") (pintype "unspecified"))
      (node (ref "RPUSB") (pin "4") (pinfunction "4_4") (pintype "unspecified"))
      (node (ref "RPUSB1") (pin "4") (pinfunction "4_4") (pintype "unspecified"))
      (node (ref "U1") (pin "3") (pinfunction "GND_3") (pintype "unspecified"))
      (node (ref "U10") (pin "3") (pinfunction "GND_3") (pintype "unspecified"))
      (node (ref "U11") (pin "3") (pinfunction "GND_3") (pintype "unspecified"))
      (node (ref "U12") (pin "11") (pinfunction "EP_11") (pintype "unspecified"))
      (node (ref "U12") (pin "8") (pinfunction "GND_8") (pintype "unspecified"))
      (node (ref "U2") (pin "1") (pinfunction "GND_1") (pintype "unspecified"))
      (node (ref "U3") (pin "5") (pinfunction "VSS_5") (pintype "unspecified"))
      (node (ref "U4") (pin "4") (pinfunction "VSS_4") (pintype "unspecified"))
      (node (ref "U5") (pin "9") (pinfunction "GND_9") (pintype "unspecified"))
      (node (ref "U6") (pin "17") (pinfunction "EP_17") (pintype "unspecified"))
      (node (ref "U6") (pin "2") (pinfunction "A0_2") (pintype "unspecified"))
      (node (ref "U6") (pin "3") (pinfunction "A1_3") (pintype "unspecified"))
      (node (ref "U6") (pin "4") (pinfunction "A2_4") (pintype "unspecified"))
      (node (ref "U6") (pin "9") (pinfunction "GND_9") (pintype "unspecified"))
      (node (ref "U7") (pin "2") (pinfunction "GND_2") (pintype "unspecified"))
      (node (ref "U8") (pin "3") (pinfunction "GND_3") (pintype "unspecified"))
      (node (ref "U9") (pin "3") (pinfunction "GND_3") (pintype "unspecified"))
      (node (ref "USB1") (pin "A1") (pinfunction "GND_A1") (pintype "unspecified"))
      (node (ref "USB1") (pin "A12") (pinfunction "GND_A12") (pintype "unspecified"))
      (node (ref "USB1") (pin "B1") (pinfunction "GND_B1") (pintype "unspecified"))
      (node (ref "USB1") (pin "B12") (pinfunction "GND_B12") (pintype "unspecified"))
    )
    (net (code "9") (name "GPIO 0") (class "Default")
      (node (ref "JP11") (pin "2") (pinfunction "2_2") (pintype "bidirectional"))
      (node (ref "QU1") (pin "2") (pinfunction "GPIO0_2") (pintype "bidirectional"))
    )
    (net (code "10") (name "GPIO 1") (class "Default")
      (node (ref "JP10") (pin "2") (pinfunction "2_2") (pintype "bidirectional"))
      (node (ref "QU1") (pin "3") (pinfunction "GPIO1_3") (pintype "bidirectional"))
    )
    (net (code "11") (name "GPIO 2") (class "Default")
      (node (ref "H22") (pin "2") (pinfunction "2_2") (pintype "input"))
      (node (ref "JP12") (pin "2") (pinfunction "2_2") (pintype "bidirectional"))
      (node (ref "QU1") (pin "4") (pinfunction "GPIO2_4") (pintype "bidirectional"))
      (node (ref "R3") (pin "2") (pinfunction "2_2") (pintype "unspecified"))
      (node (ref "U1") (pin "4") (pinfunction "SDA_4") (pintype "unspecified"))
      (node (ref "U3") (pin "6") (pinfunction "SDA_6") (pintype "unspecified"))
      (node (ref "U4") (pin "5") (pinfunction "SDA_5") (pintype "unspecified"))
    )
    (net (code "12") (name "GPIO 3") (class "Default")
      (node (ref "H22") (pin "3") (pinfunction "3_3") (pintype "input"))
      (node (ref "JP13") (pin "2") (pinfunction "2_2") (pintype "bidirectional"))
      (node (ref "QU1") (pin "5") (pinfunction "GPIO3_5") (pintype "bidirectional"))
      (node (ref "R4") (pin "2") (pinfunction "2_2") (pintype "unspecified"))
      (node (ref "U1") (pin "6") (pinfunction "SCL_6") (pintype "unspecified"))
      (node (ref "U3") (pin "7") (pinfunction "SCL_7") (pintype "unspecified"))
      (node (ref "U4") (pin "6") (pinfunction "SCL_6") (pintype "unspecified"))
    )
    (net (code "13") (name "GPIO 4") (class "Default")
      (node (ref "QU1") (pin "6") (pinfunction "GPIO4_6") (pintype "bidirectional"))
    )
    (net (code "14") (name "GPIO 5") (class "Default")
      (node (ref "JP14") (pin "2") (pinfunction "2_2") (pintype "bidirectional"))
      (node (ref "QU1") (pin "7") (pinfunction "GPIO5_7") (pintype "bidirectional"))
    )
    (net (code "15") (name "GPIO 6") (class "Default")
      (node (ref "JP15") (pin "2") (pinfunction "2_2") (pintype "bidirectional"))
      (node (ref "QU1") (pin "8") (pinfunction "GPIO6_8") (pintype "bidirectional"))
    )
    (net (code "16") (name "GPIO 7") (class "Default")
      (node (ref "QU1") (pin "9") (pinfunction "GPIO7_9") (pintype "bidirectional"))
    )
    (net (code "17") (name "GPIO 8") (class "Default")
      (node (ref "QU1") (pin "11") (pinfunction "GPIO8_11") (pintype "bidirectional"))
    )
    (net (code "18") (name "GPIO 9") (class "Default")
      (node (ref "QU1") (pin "12") (pinfunction "GPIO9_12") (pintype "bidirectional"))
    )
    (net (code "19") (name "GPIO 10") (class "Default")
      (node (ref "QU1") (pin "13") (pinfunction "GPIO10_13") (pintype "bidirectional"))
    )
    (net (code "20") (name "GPIO 11") (class "Default")
      (node (ref "QU1") (pin "14") (pinfunction "GPIO11_14") (pintype "bidirectional"))
    )
    (net (code "21") (name "GPIO 12") (class "Default")
      (node (ref "QU1") (pin "15") (pinfunction "GPIO12_15") (pintype "bidirectional"))
    )
    (net (code "22") (name "GPIO 13") (class "Default")
      (node (ref "QU1") (pin "16") (pinfunction "GPIO13_16") (pintype "bidirectional"))
    )
    (net (code "23") (name "GPIO 14") (class "Default")
      (node (ref "QU1") (pin "17") (pinfunction "GPIO14_17") (pintype "bidirectional"))
    )
    (net (code "24") (name "GPIO 15") (class "Default")
      (node (ref "QU1") (pin "18") (pinfunction "GPIO15_18") (pintype "bidirectional"))
    )
    (net (code "25") (name "GPIO 16") (class "Default")
      (node (ref "JP7") (pin "1") (pinfunction "1_1") (pintype "bidirectional"))
      (node (ref "QU1") (pin "27") (pinfunction "GPIO16_27") (pintype "bidirectional"))
    )
    (net (code "26") (name "GPIO 17") (class "Default")
      (node (ref "QU1") (pin "28") (pinfunction "GPIO17_28") (pintype "bidirectional"))
    )
    (net (code "27") (name "GPIO 18") (class "Default")
      (node (ref "QU1") (pin "29") (pinfunction "GPIO18_29") (pintype "bidirectional"))
    )
    (net (code "28") (name "GPIO 19") (class "Default")
      (node (ref "QU1") (pin "30") (pinfunction "GPIO19_30") (pintype "bidirectional"))
    )
    (net (code "29") (name "GPIO 20") (class "Default")
      (node (ref "QU1") (pin "31") (pinfunction "GPIO20_31") (pintype "bidirectional"))
    )
    (net (code "30") (name "GPIO 21") (class "Default")
      (node (ref "QU1") (pin "32") (pinfunction "GPIO21_32") (pintype "bidirectional"))
    )
    (net (code "31") (name "GPIO 22") (class "Default")
      (node (ref "JP6") (pin "1") (pinfunction "1_1") (pintype "bidirectional"))
      (node (ref "QU1") (pin "34") (pinfunction "GPIO22_34") (pintype "bidirectional"))
    )
    (net (code "32") (name "GPIO 23") (class "Default")
      (node (ref "QU1") (pin "35") (pinfunction "GPIO23_35") (pintype "bidirectional"))
    )
    (net (code "33") (name "GPIO 24") (class "Default")
      (node (ref "QU1") (pin "36") (pinfunction "GPIO24_36") (pintype "bidirectional"))
    )
    (net (code "34") (name "GPIO 25") (class "Default")
      (node (ref "QU1") (pin "37") (pinfunction "GPIO25_37") (pintype "bidirectional"))
      (node (ref "R13") (pin "1") (pinfunction "1_1") (pintype "unspecified"))
    )
    (net (code "35") (name "MATRIX_DIN") (class "Default")
      (node (ref "H2") (pin "2") (pinfunction "2_2") (pintype "input"))
      (node (ref "LED115") (pin "2") (pinfunction "DOUT_2") (pintype "unspecified"))
      (node (ref "LED8") (pin "4") (pinfunction "DIN_4") (pintype "unspecified"))
    )
    (net (code "36") (name "Net-(D1-C)") (class "Default")
      (node (ref "C122") (pin "1") (pinfunction "1_1") (pintype "input"))
      (node (ref "D1") (pin "1") (pinfunction "C_1") (pintype "unspecified"))
      (node (ref "JP4") (pin "2") (pinfunction "2_2") (pintype "bidirectional"))
      (node (ref "LED115") (pin "1") (pinfunction "VDD_1") (pintype "unspecified"))
    )
    (net (code "37") (name "Net-(ESPFLASH-Pad2)") (class "Default")
      (node (ref "ESPFLASH") (pin "2") (pinfunction "2_2") (pintype "unspecified"))
      (node (ref "ESPRST") (pin "1") (pinfunction "1_1") (pintype "unspecified"))
    )
    (net (code "38") (name "Net-(ESPFLASH-Pad3)") (class "Default")
      (node (ref "ESPFLASH") (pin "3") (pinfunction "3_3") (pintype "unspecified"))
      (node (ref "JP15") (pin "1") (pinfunction "1_1") (pintype "bidirectional"))
    )
    (net (code "39") (name "Net-(JP3-Pad1)") (class "Default")
      (node (ref "JP3") (pin "1") (pinfunction "1_1") (pintype "bidirectional"))
      (node (ref "R12") (pin "1") (pinfunction "1_1") (pintype "input"))
    )
    (net (code "40") (name "Net-(JP12-Pad1)") (class "Default")
      (node (ref "JP12") (pin "1") (pinfunction "1_1") (pintype "bidirectional"))
      (node (ref "JP2") (pin "2") (pinfunction "2_2") (pintype "bidirectional"))
    )
    (net (code "41") (name "Net-(JP13-Pad1)") (class "Default")
      (node (ref "JP13") (pin "1") (pinfunction "1_1") (pintype "bidirectional"))
      (node (ref "JP9") (pin "2") (pinfunction "2_2") (pintype "bidirectional"))
    )
    (net (code "42") (name "Net-(JP16-Pad2)") (class "Default")
      (node (ref "JP16") (pin "2") (pinfunction "2_2") (pintype "bidirectional"))
      (node (ref "JP18") (pin "1") (pinfunction "1_1") (pintype "bidirectional"))
    )
    (net (code "43") (name "Net-(JP17-Pad2)") (class "Default")
      (node (ref "JP17") (pin "2") (pinfunction "2_2") (pintype "bidirectional"))
      (node (ref "JP19") (pin "1") (pinfunction "1_1") (pintype "bidirectional"))
    )
    (net (code "44") (name "Net-(LED1-DIN)") (class "Default")
      (node (ref "LED1") (pin "4") (pinfunction "DIN_4") (pintype "unspecified"))
      (node (ref "LED16") (pin "2") (pinfunction "DOUT_2") (pintype "unspecified"))
    )
    (net (code "45") (name "Net-(LED1-DOUT)") (class "Default")
      (node (ref "LED1") (pin "2") (pinfunction "DOUT_2") (pintype "unspecified"))
      (node (ref "LED3") (pin "4") (pinfunction "DIN_4") (pintype "unspecified"))
    )
    (net (code "46") (name "Net-(LED2-+)") (class "Default")
      (node (ref "LED2") (pin "2") (pinfunction "+_2") (pintype "unspecified"))
      (node (ref "R25") (pin "2") (pinfunction "2_2") (pintype "unspecified"))
    )
    (net (code "47") (name "Net-(LED2--)") (class "Default")
      (node (ref "LED2") (pin "1") (pinfunction "-_1") (pintype "unspecified"))
      (node (ref "U6") (pin "13") (pinfunction "P7_13") (pintype "unspecified"))
    )
    (net (code "48") (name "Net-(LED6-DOUT)") (class "Default")
      (node (ref "LED6") (pin "2") (pinfunction "DOUT_2") (pintype "unspecified"))
      (node (ref "LED7") (pin "4") (pinfunction "DIN_4") (pintype "unspecified"))
    )
    (net (code "49") (name "Net-(LED8-DOUT)") (class "Default")
      (node (ref "LED8") (pin "2") (pinfunction "DOUT_2") (pintype "unspecified"))
      (node (ref "LED9") (pin "4") (pinfunction "DIN_4") (pintype "unspecified"))
    )
    (net (code "50") (name "Net-(LED10-DIN)") (class "Default")
      (node (ref "LED10") (pin "4") (pinfunction "DIN_4") (pintype "unspecified"))
      (node (ref "LED9") (pin "2") (pinfunction "DOUT_2") (pintype "unspecified"))
    )
    (net (code "51") (name "Net-(LED10-DOUT)") (class "Default")
      (node (ref "LED10") (pin "2") (pinfunction "DOUT_2") (pintype "unspecified"))
      (node (ref "LED11") (pin "4") (pinfunction "DIN_4") (pintype "unspecified"))
    )
    (net (code "52") (name "Net-(LED11-DOUT)") (class "Default")
      (node (ref "LED11") (pin "2") (pinfunction "DOUT_2") (pintype "unspecified"))
      (node (ref "LED12") (pin "4") (pinfunction "DIN_4") (pintype "unspecified"))
    )
    (net (code "53") (name "Net-(LED12-DOUT)") (class "Default")
      (node (ref "LED12") (pin "2") (pinfunction "DOUT_2") (pintype "unspecified"))
      (node (ref "LED15") (pin "4") (pinfunction "DIN_4") (pintype "unspecified"))
    )
    (net (code "54") (name "Net-(LED13-DIN)") (class "Default")
      (node (ref "LED13") (pin "4") (pinfunction "DIN_4") (pintype "unspecified"))
      (node (ref "LED14") (pin "2") (pinfunction "DOUT_2") (pintype "unspecified"))
    )
    (net (code "55") (name "Net-(LED13-DOUT)") (class "Default")
      (node (ref "LED13") (pin "2") (pinfunction "DOUT_2") (pintype "unspecified"))
      (node (ref "LED16") (pin "4") (pinfunction "DIN_4") (pintype "unspecified"))
    )
    (net (code "56") (name "Net-(LED14-DIN)") (class "Default")
      (node (ref "LED14") (pin "4") (pinfunction "DIN_4") (pintype "unspecified"))
      (node (ref "LED15") (pin "2") (pinfunction "DOUT_2") (pintype "unspecified"))
    )
    (net (code "57") (name "Net-(LED17-DIN)") (class "Default")
      (node (ref "LED17") (pin "4") (pinfunction "DIN_4") (pintype "unspecified"))
      (node (ref "LED7") (pin "2") (pinfunction "DOUT_2") (pintype "unspecified"))
    )
    (net (code "58") (name "Net-(LED17-DOUT)") (class "Default")
      (node (ref "LED17") (pin "2") (pinfunction "DOUT_2") (pintype "unspecified"))
      (node (ref "LED5") (pin "4") (pinfunction "DIN_4") (pintype "unspecified"))
    )
    (net (code "59") (name "Net-(LED18-DIN)") (class "Default")
      (node (ref "LED18") (pin "4") (pinfunction "DIN_4") (pintype "unspecified"))
      (node (ref "LED19") (pin "2") (pinfunction "DOUT_2") (pintype "unspecified"))
    )
    (net (code "60") (name "Net-(LED18-DOUT)") (class "Default")
      (node (ref "LED18") (pin "2") (pinfunction "DOUT_2") (pintype "unspecified"))
      (node (ref "LED6") (pin "4") (pinfunction "DIN_4") (pintype "unspecified"))
    )
    (net (code "61") (name "Net-(LED19-DIN)") (class "Default")
      (node (ref "LED19") (pin "4") (pinfunction "DIN_4") (pintype "unspecified"))
      (node (ref "LED20") (pin "2") (pinfunction "DOUT_2") (pintype "unspecified"))
    )
    (net (code "62") (name "Net-(LED20-DIN)") (class "Default")
      (node (ref "LED20") (pin "4") (pinfunction "DIN_4") (pintype "unspecified"))
      (node (ref "LED21") (pin "2") (pinfunction "DOUT_2") (pintype "unspecified"))
    )
    (net (code "63") (name "Net-(LED21-DIN)") (class "Default")
      (node (ref "LED21") (pin "4") (pinfunction "DIN_4") (pintype "unspecified"))
      (node (ref "LED22") (pin "2") (pinfunction "DOUT_2") (pintype "unspecified"))
    )
    (net (code "64") (name "Net-(LED23-DIN)") (class "Default")
      (node (ref "LED23") (pin "4") (pinfunction "DIN_4") (pintype "unspecified"))
      (node (ref "LED5") (pin "2") (pinfunction "DOUT_2") (pintype "unspecified"))
    )
    (net (code "65") (name "Net-(LED23-DOUT)") (class "Default")
      (node (ref "LED23") (pin "2") (pinfunction "DOUT_2") (pintype "unspecified"))
      (node (ref "LED4") (pin "4") (pinfunction "DIN_4") (pintype "unspecified"))
    )
    (net (code "66") (name "Net-(LED24-DIN)") (class "Default")
      (node (ref "LED24") (pin "4") (pinfunction "DIN_4") (pintype "unspecified"))
      (node (ref "LED33") (pin "2") (pinfunction "DOUT_2") (pintype "unspecified"))
    )
    (net (code "67") (name "Net-(LED24-DOUT)") (class "Default")
      (node (ref "LED24") (pin "2") (pinfunction "DOUT_2") (pintype "unspecified"))
      (node (ref "LED34") (pin "4") (pinfunction "DIN_4") (pintype "unspecified"))
    )
    (net (code "68") (name "Net-(LED25-DIN)") (class "Default")
      (node (ref "H1") (pin "2") (pinfunction "2_2") (pintype "input"))
      (node (ref "H5") (pin "2") (pinfunction "2_2") (pintype "input"))
      (node (ref "LED25") (pin "4") (pinfunction "DIN_4") (pintype "unspecified"))
      (node (ref "LED4") (pin "2") (pinfunction "DOUT_2") (pintype "unspecified"))
    )
    (net (code "69") (name "Net-(LED25-DOUT)") (class "Default")
      (node (ref "LED25") (pin "2") (pinfunction "DOUT_2") (pintype "unspecified"))
      (node (ref "LED26") (pin "4") (pinfunction "DIN_4") (pintype "unspecified"))
    )
    (net (code "70") (name "Net-(LED26-DOUT)") (class "Default")
      (node (ref "LED26") (pin "2") (pinfunction "DOUT_2") (pintype "unspecified"))
      (node (ref "LED27") (pin "4") (pinfunction "DIN_4") (pintype "unspecified"))
    )
    (net (code "71") (name "Net-(LED27-DOUT)") (class "Default")
      (node (ref "LED27") (pin "2") (pinfunction "DOUT_2") (pintype "unspecified"))
      (node (ref "LED28") (pin "4") (pinfunction "DIN_4") (pintype "unspecified"))
    )
    (net (code "72") (name "Net-(LED28-DOUT)") (class "Default")
      (node (ref "LED28") (pin "2") (pinfunction "DOUT_2") (pintype "unspecified"))
      (node (ref "LED29") (pin "4") (pinfunction "DIN_4") (pintype "unspecified"))
    )
    (net (code "73") (name "Net-(LED29-DOUT)") (class "Default")
      (node (ref "LED29") (pin "2") (pinfunction "DOUT_2") (pintype "unspecified"))
      (node (ref "LED32") (pin "4") (pinfunction "DIN_4") (pintype "unspecified"))
    )
    (net (code "74") (name "Net-(LED30-DIN)") (class "Default")
      (node (ref "LED30") (pin "4") (pinfunction "DIN_4") (pintype "unspecified"))
      (node (ref "LED31") (pin "2") (pinfunction "DOUT_2") (pintype "unspecified"))
    )
    (net (code "75") (name "Net-(LED30-DOUT)") (class "Default")
      (node (ref "LED30") (pin "2") (pinfunction "DOUT_2") (pintype "unspecified"))
      (node (ref "LED33") (pin "4") (pinfunction "DIN_4") (pintype "unspecified"))
    )
    (net (code "76") (name "Net-(LED31-DIN)") (class "Default")
      (node (ref "LED31") (pin "4") (pinfunction "DIN_4") (pintype "unspecified"))
      (node (ref "LED32") (pin "2") (pinfunction "DOUT_2") (pintype "unspecified"))
    )
    (net (code "77") (name "Net-(LED34-DOUT)") (class "Default")
      (node (ref "H6") (pin "2") (pinfunction "2_2") (pintype "input"))
      (node (ref "H8") (pin "2") (pinfunction "2_2") (pintype "input"))
      (node (ref "LED34") (pin "2") (pinfunction "DOUT_2") (pintype "unspecified"))
      (node (ref "LED44") (pin "4") (pinfunction "DIN_4") (pintype "unspecified"))
    )
    (net (code "78") (name "Net-(LED35-DIN)") (class "Default")
      (node (ref "LED35") (pin "4") (pinfunction "DIN_4") (pintype "unspecified"))
      (node (ref "LED45") (pin "2") (pinfunction "DOUT_2") (pintype "unspecified"))
    )
    (net (code "79") (name "Net-(LED35-DOUT)") (class "Default")
      (node (ref "H7") (pin "2") (pinfunction "2_2") (pintype "input"))
      (node (ref "H9") (pin "2") (pinfunction "2_2") (pintype "input"))
      (node (ref "LED35") (pin "2") (pinfunction "DOUT_2") (pintype "unspecified"))
      (node (ref "LED47") (pin "4") (pinfunction "DIN_4") (pintype "unspecified"))
    )
    (net (code "80") (name "Net-(LED36-DIN)") (class "Default")
      (node (ref "LED36") (pin "4") (pinfunction "DIN_4") (pintype "unspecified"))
      (node (ref "LED39") (pin "2") (pinfunction "DOUT_2") (pintype "unspecified"))
    )
    (net (code "81") (name "Net-(LED36-DOUT)") (class "Default")
      (node (ref "LED36") (pin "2") (pinfunction "DOUT_2") (pintype "unspecified"))
      (node (ref "LED45") (pin "4") (pinfunction "DIN_4") (pintype "unspecified"))
    )
    (net (code "82") (name "Net-(LED37-DIN)") (class "Default")
      (node (ref "LED37") (pin "4") (pinfunction "DIN_4") (pintype "unspecified"))
      (node (ref "LED40") (pin "2") (pinfunction "DOUT_2") (pintype "unspecified"))
    )
    (net (code "83") (name "Net-(LED37-DOUT)") (class "Default")
      (node (ref "LED37") (pin "2") (pinfunction "DOUT_2") (pintype "unspecified"))
      (node (ref "LED38") (pin "4") (pinfunction "DIN_4") (pintype "unspecified"))
    )
    (net (code "84") (name "Net-(LED38-DOUT)") (class "Default")
      (node (ref "LED38") (pin "2") (pinfunction "DOUT_2") (pintype "unspecified"))
      (node (ref "LED39") (pin "4") (pinfunction "DIN_4") (pintype "unspecified"))
    )
    (net (code "85") (name "Net-(LED40-DIN)") (class "Default")
      (node (ref "LED40") (pin "4") (pinfunction "DIN_4") (pintype "unspecified"))
      (node (ref "LED41") (pin "2") (pinfunction "DOUT_2") (pintype "unspecified"))
    )
    (net (code "86") (name "Net-(LED41-DIN)") (class "Default")
      (node (ref "LED41") (pin "4") (pinfunction "DIN_4") (pintype "unspecified"))
      (node (ref "LED42") (pin "2") (pinfunction "DOUT_2") (pintype "unspecified"))
    )
    (net (code "87") (name "Net-(LED42-DIN)") (class "Default")
      (node (ref "LED42") (pin "4") (pinfunction "DIN_4") (pintype "unspecified"))
      (node (ref "LED43") (pin "2") (pinfunction "DOUT_2") (pintype "unspecified"))
    )
    (net (code "88") (name "Net-(LED43-DIN)") (class "Default")
      (node (ref "LED43") (pin "4") (pinfunction "DIN_4") (pintype "unspecified"))
      (node (ref "LED44") (pin "2") (pinfunction "DOUT_2") (pintype "unspecified"))
    )
    (net (code "89") (name "Net-(LED46-DIN)") (class "Default")
      (node (ref "LED46") (pin "4") (pinfunction "DIN_4") (pintype "unspecified"))
      (node (ref "LED55") (pin "2") (pinfunction "DOUT_2") (pintype "unspecified"))
    )
    (net (code "90") (name "Net-(LED46-DOUT)") (class "Default")
      (node (ref "LED46") (pin "2") (pinfunction "DOUT_2") (pintype "unspecified"))
      (node (ref "LED56") (pin "4") (pinfunction "DIN_4") (pintype "unspecified"))
    )
    (net (code "91") (name "Net-(LED47-DOUT)") (class "Default")
      (node (ref "LED47") (pin "2") (pinfunction "DOUT_2") (pintype "unspecified"))
      (node (ref "LED48") (pin "4") (pinfunction "DIN_4") (pintype "unspecified"))
    )
    (net (code "92") (name "Net-(LED48-DOUT)") (class "Default")
      (node (ref "LED48") (pin "2") (pinfunction "DOUT_2") (pintype "unspecified"))
      (node (ref "LED49") (pin "4") (pinfunction "DIN_4") (pintype "unspecified"))
    )
    (net (code "93") (name "Net-(LED49-DOUT)") (class "Default")
      (node (ref "LED49") (pin "2") (pinfunction "DOUT_2") (pintype "unspecified"))
      (node (ref "LED50") (pin "4") (pinfunction "DIN_4") (pintype "unspecified"))
    )
    (net (code "94") (name "Net-(LED50-DOUT)") (class "Default")
      (node (ref "LED50") (pin "2") (pinfunction "DOUT_2") (pintype "unspecified"))
      (node (ref "LED51") (pin "4") (pinfunction "DIN_4") (pintype "unspecified"))
    )
    (net (code "95") (name "Net-(LED51-DOUT)") (class "Default")
      (node (ref "LED51") (pin "2") (pinfunction "DOUT_2") (pintype "unspecified"))
      (node (ref "LED54") (pin "4") (pinfunction "DIN_4") (pintype "unspecified"))
    )
    (net (code "96") (name "Net-(LED52-DIN)") (class "Default")
      (node (ref "LED52") (pin "4") (pinfunction "DIN_4") (pintype "unspecified"))
      (node (ref "LED53") (pin "2") (pinfunction "DOUT_2") (pintype "unspecified"))
    )
    (net (code "97") (name "Net-(LED52-DOUT)") (class "Default")
      (node (ref "LED52") (pin "2") (pinfunction "DOUT_2") (pintype "unspecified"))
      (node (ref "LED55") (pin "4") (pinfunction "DIN_4") (pintype "unspecified"))
    )
    (net (code "98") (name "Net-(LED53-DIN)") (class "Default")
      (node (ref "LED53") (pin "4") (pinfunction "DIN_4") (pintype "unspecified"))
      (node (ref "LED54") (pin "2") (pinfunction "DOUT_2") (pintype "unspecified"))
    )
    (net (code "99") (name "Net-(LED56-DOUT)") (class "Default")
      (node (ref "H10") (pin "2") (pinfunction "2_2") (pintype "input"))
      (node (ref "H12") (pin "2") (pinfunction "2_2") (pintype "input"))
      (node (ref "LED56") (pin "2") (pinfunction "DOUT_2") (pintype "unspecified"))
      (node (ref "LED66") (pin "4") (pinfunction "DIN_4") (pintype "unspecified"))
    )
    (net (code "100") (name "Net-(LED57-DIN)") (class "Default")
      (node (ref "LED57") (pin "4") (pinfunction "DIN_4") (pintype "unspecified"))
      (node (ref "LED67") (pin "2") (pinfunction "DOUT_2") (pintype "unspecified"))
    )
    (net (code "101") (name "Net-(LED57-DOUT)") (class "Default")
      (node (ref "H11") (pin "2") (pinfunction "2_2") (pintype "input"))
      (node (ref "H13") (pin "2") (pinfunction "2_2") (pintype "input"))
      (node (ref "LED57") (pin "2") (pinfunction "DOUT_2") (pintype "unspecified"))
      (node (ref "LED69") (pin "4") (pinfunction "DIN_4") (pintype "unspecified"))
    )
    (net (code "102") (name "Net-(LED58-DIN)") (class "Default")
      (node (ref "LED58") (pin "4") (pinfunction "DIN_4") (pintype "unspecified"))
      (node (ref "LED61") (pin "2") (pinfunction "DOUT_2") (pintype "unspecified"))
    )
    (net (code "103") (name "Net-(LED58-DOUT)") (class "Default")
      (node (ref "LED58") (pin "2") (pinfunction "DOUT_2") (pintype "unspecified"))
      (node (ref "LED67") (pin "4") (pinfunction "DIN_4") (pintype "unspecified"))
    )
    (net (code "104") (name "Net-(LED59-DIN)") (class "Default")
      (node (ref "LED59") (pin "4") (pinfunction "DIN_4") (pintype "unspecified"))
      (node (ref "LED62") (pin "2") (pinfunction "DOUT_2") (pintype "unspecified"))
    )
    (net (code "105") (name "Net-(LED59-DOUT)") (class "Default")
      (node (ref "LED59") (pin "2") (pinfunction "DOUT_2") (pintype "unspecified"))
      (node (ref "LED60") (pin "4") (pinfunction "DIN_4") (pintype "unspecified"))
    )
    (net (code "106") (name "Net-(LED60-DOUT)") (class "Default")
      (node (ref "LED60") (pin "2") (pinfunction "DOUT_2") (pintype "unspecified"))
      (node (ref "LED61") (pin "4") (pinfunction "DIN_4") (pintype "unspecified"))
    )
    (net (code "107") (name "Net-(LED62-DIN)") (class "Default")
      (node (ref "LED62") (pin "4") (pinfunction "DIN_4") (pintype "unspecified"))
      (node (ref "LED63") (pin "2") (pinfunction "DOUT_2") (pintype "unspecified"))
    )
    (net (code "108") (name "Net-(LED63-DIN)") (class "Default")
      (node (ref "LED63") (pin "4") (pinfunction "DIN_4") (pintype "unspecified"))
      (node (ref "LED64") (pin "2") (pinfunction "DOUT_2") (pintype "unspecified"))
    )
    (net (code "109") (name "Net-(LED64-DIN)") (class "Default")
      (node (ref "LED64") (pin "4") (pinfunction "DIN_4") (pintype "unspecified"))
      (node (ref "LED65") (pin "2") (pinfunction "DOUT_2") (pintype "unspecified"))
    )
    (net (code "110") (name "Net-(LED65-DIN)") (class "Default")
      (node (ref "LED65") (pin "4") (pinfunction "DIN_4") (pintype "unspecified"))
      (node (ref "LED66") (pin "2") (pinfunction "DOUT_2") (pintype "unspecified"))
    )
    (net (code "111") (name "Net-(LED68-DIN)") (class "Default")
      (node (ref "LED68") (pin "4") (pinfunction "DIN_4") (pintype "unspecified"))
      (node (ref "LED77") (pin "2") (pinfunction "DOUT_2") (pintype "unspecified"))
    )
    (net (code "112") (name "Net-(LED68-DOUT)") (class "Default")
      (node (ref "LED68") (pin "2") (pinfunction "DOUT_2") (pintype "unspecified"))
      (node (ref "LED78") (pin "4") (pinfunction "DIN_4") (pintype "unspecified"))
    )
    (net (code "113") (name "Net-(LED69-DOUT)") (class "Default")
      (node (ref "LED69") (pin "2") (pinfunction "DOUT_2") (pintype "unspecified"))
      (node (ref "LED70") (pin "4") (pinfunction "DIN_4") (pintype "unspecified"))
    )
    (net (code "114") (name "Net-(LED70-DOUT)") (class "Default")
      (node (ref "LED70") (pin "2") (pinfunction "DOUT_2") (pintype "unspecified"))
      (node (ref "LED71") (pin "4") (pinfunction "DIN_4") (pintype "unspecified"))
    )
    (net (code "115") (name "Net-(LED71-DOUT)") (class "Default")
      (node (ref "LED71") (pin "2") (pinfunction "DOUT_2") (pintype "unspecified"))
      (node (ref "LED72") (pin "4") (pinfunction "DIN_4") (pintype "unspecified"))
    )
    (net (code "116") (name "Net-(LED72-DOUT)") (class "Default")
      (node (ref "LED72") (pin "2") (pinfunction "DOUT_2") (pintype "unspecified"))
      (node (ref "LED73") (pin "4") (pinfunction "DIN_4") (pintype "unspecified"))
    )
    (net (code "117") (name "Net-(LED73-DOUT)") (class "Default")
      (node (ref "LED73") (pin "2") (pinfunction "DOUT_2") (pintype "unspecified"))
      (node (ref "LED76") (pin "4") (pinfunction "DIN_4") (pintype "unspecified"))
    )
    (net (code "118") (name "Net-(LED74-DIN)") (class "Default")
      (node (ref "LED74") (pin "4") (pinfunction "DIN_4") (pintype "unspecified"))
      (node (ref "LED75") (pin "2") (pinfunction "DOUT_2") (pintype "unspecified"))
    )
    (net (code "119") (name "Net-(LED74-DOUT)") (class "Default")
      (node (ref "LED74") (pin "2") (pinfunction "DOUT_2") (pintype "unspecified"))
      (node (ref "LED77") (pin "4") (pinfunction "DIN_4") (pintype "unspecified"))
    )
    (net (code "120") (name "Net-(LED75-DIN)") (class "Default")
      (node (ref "LED75") (pin "4") (pinfunction "DIN_4") (pintype "unspecified"))
      (node (ref "LED76") (pin "2") (pinfunction "DOUT_2") (pintype "unspecified"))
    )
    (net (code "121") (name "Net-(LED78-DOUT)") (class "Default")
      (node (ref "H14") (pin "2") (pinfunction "2_2") (pintype "input"))
      (node (ref "H16") (pin "2") (pinfunction "2_2") (pintype "input"))
      (node (ref "LED78") (pin "2") (pinfunction "DOUT_2") (pintype "unspecified"))
      (node (ref "LED88") (pin "4") (pinfunction "DIN_4") (pintype "unspecified"))
    )
    (net (code "122") (name "Net-(LED79-DIN)") (class "Default")
      (node (ref "LED79") (pin "4") (pinfunction "DIN_4") (pintype "unspecified"))
      (node (ref "LED89") (pin "2") (pinfunction "DOUT_2") (pintype "unspecified"))
    )
    (net (code "123") (name "Net-(LED79-DOUT)") (class "Default")
      (node (ref "H15") (pin "2") (pinfunction "2_2") (pintype "input"))
      (node (ref "H17") (pin "2") (pinfunction "2_2") (pintype "input"))
      (node (ref "LED79") (pin "2") (pinfunction "DOUT_2") (pintype "unspecified"))
      (node (ref "LED91") (pin "4") (pinfunction "DIN_4") (pintype "unspecified"))
    )
    (net (code "124") (name "Net-(LED80-DIN)") (class "Default")
      (node (ref "LED80") (pin "4") (pinfunction "DIN_4") (pintype "unspecified"))
      (node (ref "LED83") (pin "2") (pinfunction "DOUT_2") (pintype "unspecified"))
    )
    (net (code "125") (name "Net-(LED80-DOUT)") (class "Default")
      (node (ref "LED80") (pin "2") (pinfunction "DOUT_2") (pintype "unspecified"))
      (node (ref "LED89") (pin "4") (pinfunction "DIN_4") (pintype "unspecified"))
    )
    (net (code "126") (name "Net-(LED81-DIN)") (class "Default")
      (node (ref "LED81") (pin "4") (pinfunction "DIN_4") (pintype "unspecified"))
      (node (ref "LED84") (pin "2") (pinfunction "DOUT_2") (pintype "unspecified"))
    )
    (net (code "127") (name "Net-(LED81-DOUT)") (class "Default")
      (node (ref "LED81") (pin "2") (pinfunction "DOUT_2") (pintype "unspecified"))
      (node (ref "LED82") (pin "4") (pinfunction "DIN_4") (pintype "unspecified"))
    )
    (net (code "128") (name "Net-(LED82-DOUT)") (class "Default")
      (node (ref "LED82") (pin "2") (pinfunction "DOUT_2") (pintype "unspecified"))
      (node (ref "LED83") (pin "4") (pinfunction "DIN_4") (pintype "unspecified"))
    )
    (net (code "129") (name "Net-(LED84-DIN)") (class "Default")
      (node (ref "LED84") (pin "4") (pinfunction "DIN_4") (pintype "unspecified"))
      (node (ref "LED85") (pin "2") (pinfunction "DOUT_2") (pintype "unspecified"))
    )
    (net (code "130") (name "Net-(LED85-DIN)") (class "Default")
      (node (ref "LED85") (pin "4") (pinfunction "DIN_4") (pintype "unspecified"))
      (node (ref "LED86") (pin "2") (pinfunction "DOUT_2") (pintype "unspecified"))
    )
    (net (code "131") (name "Net-(LED86-DIN)") (class "Default")
      (node (ref "LED86") (pin "4") (pinfunction "DIN_4") (pintype "unspecified"))
      (node (ref "LED87") (pin "2") (pinfunction "DOUT_2") (pintype "unspecified"))
    )
    (net (code "132") (name "Net-(LED87-DIN)") (class "Default")
      (node (ref "LED87") (pin "4") (pinfunction "DIN_4") (pintype "unspecified"))
      (node (ref "LED88") (pin "2") (pinfunction "DOUT_2") (pintype "unspecified"))
    )
    (net (code "133") (name "Net-(LED90-DIN)") (class "Default")
      (node (ref "LED90") (pin "4") (pinfunction "DIN_4") (pintype "unspecified"))
      (node (ref "LED99") (pin "2") (pinfunction "DOUT_2") (pintype "unspecified"))
    )
    (net (code "134") (name "Net-(LED91-DOUT)") (class "Default")
      (node (ref "LED91") (pin "2") (pinfunction "DOUT_2") (pintype "unspecified"))
      (node (ref "LED92") (pin "4") (pinfunction "DIN_4") (pintype "unspecified"))
    )
    (net (code "135") (name "Net-(LED92-DOUT)") (class "Default")
      (node (ref "LED92") (pin "2") (pinfunction "DOUT_2") (pintype "unspecified"))
      (node (ref "LED93") (pin "4") (pinfunction "DIN_4") (pintype "unspecified"))
    )
    (net (code "136") (name "Net-(LED93-DOUT)") (class "Default")
      (node (ref "LED93") (pin "2") (pinfunction "DOUT_2") (pintype "unspecified"))
      (node (ref "LED94") (pin "4") (pinfunction "DIN_4") (pintype "unspecified"))
    )
    (net (code "137") (name "Net-(LED94-DOUT)") (class "Default")
      (node (ref "LED94") (pin "2") (pinfunction "DOUT_2") (pintype "unspecified"))
      (node (ref "LED95") (pin "4") (pinfunction "DIN_4") (pintype "unspecified"))
    )
    (net (code "138") (name "Net-(LED95-DOUT)") (class "Default")
      (node (ref "LED95") (pin "2") (pinfunction "DOUT_2") (pintype "unspecified"))
      (node (ref "LED98") (pin "4") (pinfunction "DIN_4") (pintype "unspecified"))
    )
    (net (code "139") (name "Net-(LED96-DIN)") (class "Default")
      (node (ref "LED96") (pin "4") (pinfunction "DIN_4") (pintype "unspecified"))
      (node (ref "LED97") (pin "2") (pinfunction "DOUT_2") (pintype "unspecified"))
    )
    (net (code "140") (name "Net-(LED96-DOUT)") (class "Default")
      (node (ref "LED96") (pin "2") (pinfunction "DOUT_2") (pintype "unspecified"))
      (node (ref "LED99") (pin "4") (pinfunction "DIN_4") (pintype "unspecified"))
    )
    (net (code "141") (name "Net-(LED97-DIN)") (class "Default")
      (node (ref "LED97") (pin "4") (pinfunction "DIN_4") (pintype "unspecified"))
      (node (ref "LED98") (pin "2") (pinfunction "DOUT_2") (pintype "unspecified"))
    )
    (net (code "142") (name "Net-(LED100-DIN)") (class "Default")
      (node (ref "LED100") (pin "4") (pinfunction "DIN_4") (pintype "unspecified"))
      (node (ref "LED90") (pin "2") (pinfunction "DOUT_2") (pintype "unspecified"))
    )
    (net (code "143") (name "Net-(LED100-DOUT)") (class "Default")
      (node (ref "H18") (pin "2") (pinfunction "2_2") (pintype "input"))
      (node (ref "LED100") (pin "2") (pinfunction "DOUT_2") (pintype "unspecified"))
      (node (ref "LED113") (pin "4") (pinfunction "DIN_4") (pintype "unspecified"))
    )
    (net (code "144") (name "Net-(LED101-DIN)") (class "Default")
      (node (ref "LED101") (pin "4") (pinfunction "DIN_4") (pintype "unspecified"))
      (node (ref "LED111") (pin "2") (pinfunction "DOUT_2") (pintype "unspecified"))
    )
    (net (code "145") (name "Net-(LED101-DOUT)") (class "Default")
      (node (ref "H19") (pin "2") (pinfunction "2_2") (pintype "input"))
      (node (ref "LED101") (pin "2") (pinfunction "DOUT_2") (pintype "unspecified"))
      (node (ref "LED112") (pin "4") (pinfunction "DIN_4") (pintype "unspecified"))
    )
    (net (code "146") (name "Net-(LED102-DIN)") (class "Default")
      (node (ref "LED102") (pin "4") (pinfunction "DIN_4") (pintype "unspecified"))
      (node (ref "LED105") (pin "2") (pinfunction "DOUT_2") (pintype "unspecified"))
    )
    (net (code "147") (name "Net-(LED102-DOUT)") (class "Default")
      (node (ref "LED102") (pin "2") (pinfunction "DOUT_2") (pintype "unspecified"))
      (node (ref "LED111") (pin "4") (pinfunction "DIN_4") (pintype "unspecified"))
    )
    (net (code "148") (name "Net-(LED103-DIN)") (class "Default")
      (node (ref "LED103") (pin "4") (pinfunction "DIN_4") (pintype "unspecified"))
      (node (ref "LED106") (pin "2") (pinfunction "DOUT_2") (pintype "unspecified"))
    )
    (net (code "149") (name "Net-(LED103-DOUT)") (class "Default")
      (node (ref "LED103") (pin "2") (pinfunction "DOUT_2") (pintype "unspecified"))
      (node (ref "LED104") (pin "4") (pinfunction "DIN_4") (pintype "unspecified"))
    )
    (net (code "150") (name "Net-(LED104-DOUT)") (class "Default")
      (node (ref "LED104") (pin "2") (pinfunction "DOUT_2") (pintype "unspecified"))
      (node (ref "LED105") (pin "4") (pinfunction "DIN_4") (pintype "unspecified"))
    )
    (net (code "151") (name "Net-(LED106-DIN)") (class "Default")
      (node (ref "LED106") (pin "4") (pinfunction "DIN_4") (pintype "unspecified"))
      (node (ref "LED107") (pin "2") (pinfunction "DOUT_2") (pintype "unspecified"))
    )
    (net (code "152") (name "Net-(LED107-DIN)") (class "Default")
      (node (ref "LED107") (pin "4") (pinfunction "DIN_4") (pintype "unspecified"))
      (node (ref "LED108") (pin "2") (pinfunction "DOUT_2") (pintype "unspecified"))
    )
    (net (code "153") (name "Net-(LED108-DIN)") (class "Default")
      (node (ref "LED108") (pin "4") (pinfunction "DIN_4") (pintype "unspecified"))
      (node (ref "LED109") (pin "2") (pinfunction "DOUT_2") (pintype "unspecified"))
    )
    (net (code "154") (name "Net-(LED109-DIN)") (class "Default")
      (node (ref "LED109") (pin "4") (pinfunction "DIN_4") (pintype "unspecified"))
      (node (ref "LED110") (pin "2") (pinfunction "DOUT_2") (pintype "unspecified"))
    )
    (net (code "155") (name "Net-(LED110-DIN)") (class "Default")
      (node (ref "H20") (pin "2") (pinfunction "2_2") (pintype "input"))
      (node (ref "LED110") (pin "4") (pinfunction "DIN_4") (pintype "unspecified"))
      (node (ref "LED113") (pin "2") (pinfunction "DOUT_2") (pintype "unspecified"))
    )
    (net (code "156") (name "Net-(LED114-DIN)") (class "Default")
      (node (ref "H3") (pin "2") (pinfunction "2_2") (pintype "input"))
      (node (ref "LED114") (pin "4") (pinfunction "DIN_4") (pintype "unspecified"))
      (node (ref "LED3") (pin "2") (pinfunction "DOUT_2") (pintype "unspecified"))
    )
    (net (code "157") (name "Net-(LED114-DOUT)") (class "Default")
      (node (ref "H4") (pin "2") (pinfunction "2_2") (pintype "input"))
      (node (ref "LED114") (pin "2") (pinfunction "DOUT_2") (pintype "unspecified"))
      (node (ref "LED22") (pin "4") (pinfunction "DIN_4") (pintype "unspecified"))
    )
    (net (code "158") (name "Net-(LED116-+)") (class "Default")
      (node (ref "LED116") (pin "2") (pinfunction "+_2") (pintype "unspecified"))
      (node (ref "R13") (pin "2") (pinfunction "2_2") (pintype "unspecified"))
    )
    (net (code "159") (name "Net-(P3-Pad1)") (class "Default")
      (node (ref "P3") (pin "1") (pinfunction "1_1") (pintype "unspecified"))
      (node (ref "QBOOT") (pin "3") (pinfunction "3_3") (pintype "unspecified"))
    )
    (net (code "160") (name "Net-(P3-Pad2)") (class "Default")
      (node (ref "P3") (pin "2") (pinfunction "2_2") (pintype "unspecified"))
      (node (ref "QBOOT") (pin "1") (pinfunction "1_1") (pintype "unspecified"))
    )
    (net (code "161") (name "Net-(QBOOT-Pad2)") (class "Default")
      (node (ref "QBOOT") (pin "2") (pinfunction "2_2") (pintype "unspecified"))
      (node (ref "R11") (pin "2") (pinfunction "2_2") (pintype "input"))
    )
    (net (code "162") (name "Net-(QU1-USB_DM)") (class "Default")
      (node (ref "QU1") (pin "46") (pinfunction "USB_DM_46") (pintype "bidirectional"))
      (node (ref "R9") (pin "1") (pinfunction "1_1") (pintype "unspecified"))
    )
    (net (code "163") (name "Net-(QU1-USB_DP)") (class "Default")
      (node (ref "QU1") (pin "47") (pinfunction "USB_DP_47") (pintype "bidirectional"))
      (node (ref "R7") (pin "1") (pinfunction "1_1") (pintype "unspecified"))
    )
    (net (code "164") (name "Net-(U1-ADDR)") (class "Default")
      (node (ref "R1") (pin "1") (pinfunction "1_1") (pintype "unspecified"))
      (node (ref "U1") (pin "2") (pinfunction "ADDR_2") (pintype "unspecified"))
    )
    (net (code "165") (name "Net-(U1-DVI)") (class "Default")
      (node (ref "C7") (pin "1") (pinfunction "1_1") (pintype "input"))
      (node (ref "R2") (pin "1") (pinfunction "1_1") (pintype "unspecified"))
      (node (ref "U1") (pin "5") (pinfunction "DVI_5") (pintype "unspecified"))
    )
    (net (code "166") (name "Net-(U3-OSCI)") (class "Default")
      (node (ref "U3") (pin "1") (pinfunction "OSCI_1") (pintype "unspecified"))
      (node (ref "X1") (pin "1") (pinfunction "OSC1_1") (pintype "unspecified"))
    )
    (net (code "167") (name "Net-(U3-OSCO)") (class "Default")
      (node (ref "U3") (pin "2") (pinfunction "OSCO_2") (pintype "unspecified"))
      (node (ref "X1") (pin "2") (pinfunction "OSC2_2") (pintype "unspecified"))
    )
    (net (code "168") (name "Net-(U3-VBAT)") (class "Default")
      (node (ref "BT1") (pin "1") (pinfunction "1_1") (pintype "input"))
      (node (ref "BT2") (pin "1") (pinfunction "1_1") (pintype "input"))
      (node (ref "U3") (pin "3") (pinfunction "VBAT_3") (pintype "unspecified"))
    )
    (net (code "169") (name "Net-(U5-EN)") (class "Default")
      (node (ref "R8") (pin "1") (pinfunction "1_1") (pintype "input"))
      (node (ref "U5") (pin "3") (pinfunction "EN_3") (pintype "unspecified"))
    )
    (net (code "170") (name "Net-(U5-GPIO0)") (class "Default")
      (node (ref "ESPFLASH") (pin "4") (pinfunction "4_4") (pintype "unspecified"))
      (node (ref "R14") (pin "2") (pinfunction "2_2") (pintype "input"))
      (node (ref "U5") (pin "12") (pinfunction "GPIO0_12") (pintype "unspecified"))
    )
    (net (code "171") (name "Net-(U5-GPIO2)") (class "Default")
      (node (ref "R15") (pin "2") (pinfunction "2_2") (pintype "input"))
      (node (ref "U5") (pin "11") (pinfunction "GPIO2_11") (pintype "unspecified"))
    )
    (net (code "172") (name "Net-(U5-GPIO15)") (class "Default")
      (node (ref "R16") (pin "2") (pinfunction "2_2") (pintype "input"))
      (node (ref "U5") (pin "10") (pinfunction "GPIO15_10") (pintype "unspecified"))
    )
    (net (code "173") (name "Net-(U5-GPIO16)") (class "Default")
      (node (ref "ESPRST") (pin "3") (pinfunction "3_3") (pintype "unspecified"))
      (node (ref "JP14") (pin "1") (pinfunction "1_1") (pintype "bidirectional"))
      (node (ref "P2") (pin "5") (pinfunction "5_5") (pintype "unspecified"))
      (node (ref "R6") (pin "1") (pinfunction "1_1") (pintype "input"))
      (node (ref "U5") (pin "1") (pinfunction "RST_1") (pintype "unspecified"))
      (node (ref "U5") (pin "4") (pinfunction "GPIO16_4") (pintype "unspecified"))
    )
    (net (code "174") (name "Net-(U5-RXD0)") (class "Default")
      (node (ref "JP11") (pin "1") (pinfunction "1_1") (pintype "bidirectional"))
      (node (ref "P2") (pin "3") (pinfunction "3_3") (pintype "unspecified"))
      (node (ref "U5") (pin "15") (pinfunction "RXD0_15") (pintype "unspecified"))
    )
    (net (code "175") (name "Net-(U5-TXD0)") (class "Default")
      (node (ref "JP10") (pin "1") (pinfunction "1_1") (pintype "bidirectional"))
      (node (ref "P2") (pin "4") (pinfunction "4_4") (pintype "unspecified"))
      (node (ref "U5") (pin "16") (pinfunction "TXD0_16") (pintype "unspecified"))
    )
    (net (code "176") (name "Net-(U6-P2)") (class "Default")
      (node (ref "R20") (pin "1") (pinfunction "1_1") (pintype "input"))
      (node (ref "U6") (pin "7") (pinfunction "P2_7") (pintype "unspecified"))
      (node (ref "U9") (pin "2") (pinfunction "VOUT_2") (pintype "unspecified"))
    )
    (net (code "177") (name "Net-(U6-P3)") (class "Default")
      (node (ref "R18") (pin "1") (pinfunction "1_1") (pintype "input"))
      (node (ref "U6") (pin "8") (pinfunction "P3_8") (pintype "unspecified"))
      (node (ref "U8") (pin "2") (pinfunction "VOUT_2") (pintype "unspecified"))
    )
    (net (code "178") (name "Net-(U6-SCL)") (class "Default")
      (node (ref "JP9") (pin "1") (pinfunction "1_1") (pintype "bidirectional"))
      (node (ref "U6") (pin "15") (pinfunction "SCL_15") (pintype "unspecified"))
    )
    (net (code "179") (name "Net-(U6-SDA)") (class "Default")
      (node (ref "JP2") (pin "1") (pinfunction "1_1") (pintype "bidirectional"))
      (node (ref "U6") (pin "16") (pinfunction "SDA_16") (pintype "unspecified"))
    )
    (net (code "180") (name "Net-(U7-A)") (class "Default")
      (node (ref "JP8") (pin "1") (pinfunction "1_1") (pintype "bidirectional"))
      (node (ref "R10") (pin "2") (pinfunction "2_2") (pintype "input"))
      (node (ref "U7") (pin "3") (pinfunction "A_3") (pintype "unspecified"))
    )
    (net (code "181") (name "Net-(U7-B)") (class "Default")
      (node (ref "JP6") (pin "2") (pinfunction "2_2") (pintype "bidirectional"))
      (node (ref "JP7") (pin "2") (pinfunction "2_2") (pintype "bidirectional"))
      (node (ref "JP8") (pin "2") (pinfunction "2_2") (pintype "bidirectional"))
      (node (ref "U7") (pin "4") (pinfunction "B_4") (pintype "unspecified"))
    )
    (net (code "182") (name "Net-(U7-OE)") (class "Default")
      (node (ref "JP1") (pin "2") (pinfunction "2_2") (pintype "bidirectional"))
      (node (ref "U7") (pin "5") (pinfunction "OE_5") (pintype "unspecified"))
    )
    (net (code "183") (name "Net-(U10-VOUT)") (class "Default")
      (node (ref "R21") (pin "1") (pinfunction "1_1") (pintype "input"))
      (node (ref "U10") (pin "2") (pinfunction "VOUT_2") (pintype "unspecified"))
      (node (ref "U6") (pin "6") (pinfunction "P1_6") (pintype "unspecified"))
    )
    (net (code "184") (name "Net-(U11-VOUT)") (class "Default")
      (node (ref "R22") (pin "1") (pinfunction "1_1") (pintype "input"))
      (node (ref "U11") (pin "2") (pinfunction "VOUT_2") (pintype "unspecified"))
      (node (ref "U6") (pin "5") (pinfunction "P0_5") (pintype "unspecified"))
    )
    (net (code "185") (name "Net-(U12-#EN)") (class "Default")
      (node (ref "PWRRST") (pin "4") (pinfunction "4_4") (pintype "unspecified"))
      (node (ref "R23") (pin "2") (pinfunction "2_2") (pintype "input"))
      (node (ref "U12") (pin "3") (pinfunction "#EN_3") (pintype "unspecified"))
    )
    (net (code "186") (name "Net-(USB1-CC1)") (class "Default")
      (node (ref "R17") (pin "2") (pinfunction "2_2") (pintype "input"))
      (node (ref "USB1") (pin "A5") (pinfunction "CC1_A5") (pintype "unspecified"))
    )
    (net (code "187") (name "Net-(USB1-CC2)") (class "Default")
      (node (ref "R19") (pin "2") (pinfunction "2_2") (pintype "input"))
      (node (ref "USB1") (pin "B5") (pinfunction "CC2_B5") (pintype "unspecified"))
    )
    (net (code "188") (name "PCF_P4") (class "Default")
      (node (ref "R24") (pin "1") (pinfunction "1_1") (pintype "input"))
      (node (ref "U12") (pin "4") (pinfunction "#ACK_4") (pintype "unspecified"))
      (node (ref "U6") (pin "10") (pinfunction "P4_10") (pintype "unspecified"))
    )
    (net (code "189") (name "QSPI_CLK") (class "Default")
      (node (ref "QU1") (pin "52") (pinfunction "QSPI_SCLK_52") (pintype "output"))
      (node (ref "QU2") (pin "6") (pinfunction "CLK_6") (pintype "unspecified"))
    )
    (net (code "190") (name "QSPI_SD0") (class "Default")
      (node (ref "QU1") (pin "53") (pinfunction "QSPI_SD0_53") (pintype "bidirectional"))
      (node (ref "QU2") (pin "5") (pinfunction "DI(IO0)_5") (pintype "unspecified"))
    )
    (net (code "191") (name "QSPI_SD1") (class "Default")
      (node (ref "QU1") (pin "55") (pinfunction "QSPI_SD1_55") (pintype "bidirectional"))
      (node (ref "QU2") (pin "2") (pinfunction "DO(IO1)_2") (pintype "unspecified"))
    )
    (net (code "192") (name "QSPI_SD2") (class "Default")
      (node (ref "QU1") (pin "54") (pinfunction "QSPI_SD2_54") (pintype "bidirectional"))
      (node (ref "QU2") (pin "3") (pinfunction "WP#(IO2)_3") (pintype "unspecified"))
    )
    (net (code "193") (name "QSPI_SD3") (class "Default")
      (node (ref "QU1") (pin "51") (pinfunction "QSPI_SD3_51") (pintype "bidirectional"))
      (node (ref "QU2") (pin "7") (pinfunction "HOLD#_or_RESET#(IO3)_7") (pintype "unspecified"))
    )
    (net (code "194") (name "QSPI_SS") (class "Default")
      (node (ref "QU1") (pin "56") (pinfunction "QSPI_SS_56") (pintype "bidirectional"))
      (node (ref "QU2") (pin "1") (pinfunction "CS#_1") (pintype "unspecified"))
      (node (ref "R11") (pin "1") (pinfunction "1_1") (pintype "input"))
      (node (ref "R12") (pin "2") (pinfunction "2_2") (pintype "input"))
    )
    (net (code "195") (name "RUN") (class "Default")
      (node (ref "P1") (pin "2") (pinfunction "2_2") (pintype "unspecified"))
      (node (ref "QU1") (pin "26") (pinfunction "RUN_26") (pintype "input"))
      (node (ref "R5") (pin "1") (pinfunction "1_1") (pintype "input"))
      (node (ref "RPRST") (pin "2") (pinfunction "2_2") (pintype "unspecified"))
    )
    (net (code "196") (name "SWCLK") (class "Default")
      (node (ref "P1") (pin "4") (pinfunction "4_4") (pintype "unspecified"))
      (node (ref "QU1") (pin "24") (pinfunction "SWCLK_24") (pintype "output"))
    )
    (net (code "197") (name "SWD") (class "Default")
      (node (ref "P1") (pin "3") (pinfunction "3_3") (pintype "unspecified"))
      (node (ref "QU1") (pin "25") (pinfunction "SWD_25") (pintype "bidirectional"))
    )
    (net (code "198") (name "USB_D+") (class "Default")
      (node (ref "JP19") (pin "2") (pinfunction "2_2") (pintype "bidirectional"))
      (node (ref "R7") (pin "2") (pinfunction "2_2") (pintype "unspecified"))
      (node (ref "RPUSB") (pin "3") (pinfunction "3_3") (pintype "unspecified"))
    )
    (net (code "199") (name "USB_D+C") (class "Default")
      (node (ref "JP17") (pin "1") (pinfunction "1_1") (pintype "bidirectional"))
      (node (ref "RPUSB1") (pin "3") (pinfunction "3_3") (pintype "unspecified"))
      (node (ref "U12") (pin "7") (pinfunction "D+_7") (pintype "unspecified"))
      (node (ref "USB1") (pin "A6") (pinfunction "Dp1_A6") (pintype "unspecified"))
      (node (ref "USB1") (pin "B6") (pinfunction "Dp2_B6") (pintype "unspecified"))
    )
    (net (code "200") (name "USB_D-") (class "Default")
      (node (ref "JP18") (pin "2") (pinfunction "2_2") (pintype "bidirectional"))
      (node (ref "R9") (pin "2") (pinfunction "2_2") (pintype "unspecified"))
      (node (ref "RPUSB") (pin "2") (pinfunction "2_2") (pintype "unspecified"))
    )
    (net (code "201") (name "USB_D-C") (class "Default")
      (node (ref "JP16") (pin "1") (pinfunction "1_1") (pintype "bidirectional"))
      (node (ref "RPUSB1") (pin "2") (pinfunction "2_2") (pintype "unspecified"))
      (node (ref "U12") (pin "6") (pinfunction "D-_6") (pintype "unspecified"))
      (node (ref "USB1") (pin "A7") (pinfunction "Dn1_A7") (pintype "unspecified"))
      (node (ref "USB1") (pin "B7") (pinfunction "Dn2_B7") (pintype "unspecified"))
    )
    (net (code "202") (name "USB_VBUS") (class "Default")
      (node (ref "C137") (pin "1") (pinfunction "1_1") (pintype "input"))
      (node (ref "JP5") (pin "2") (pinfunction "2_2") (pintype "bidirectional"))
      (node (ref "RPUSB1") (pin "1") (pinfunction "1_1") (pintype "unspecified"))
      (node (ref "U12") (pin "10") (pinfunction "VBUS_10") (pintype "unspecified"))
      (node (ref "U12") (pin "9") (pinfunction "VBUS_9") (pintype "unspecified"))
      (node (ref "USB1") (pin "A4") (pinfunction "VBUS_A4") (pintype "unspecified"))
      (node (ref "USB1") (pin "B9") (pinfunction "VBUS_B9") (pintype "unspecified"))
    )
    (net (code "203") (name "VCC") (class "Default")
      (node (ref "C10") (pin "2") (pinfunction "2_2") (pintype "input"))
      (node (ref "C125") (pin "2") (pinfunction "2_2") (pintype "input"))
      (node (ref "C126") (pin "2") (pinfunction "2_2") (pintype "input"))
      (node (ref "C127") (pin "2") (pinfunction "2_2") (pintype "input"))
      (node (ref "C128") (pin "2") (pinfunction "2_2") (pintype "input"))
      (node (ref "C129") (pin "1") (pinfunction "1_1") (pintype "input"))
      (node (ref "C130") (pin "1") (pinfunction "1_1") (pintype "input"))
      (node (ref "C131") (pin "2") (pinfunction "2_2") (pintype "input"))
      (node (ref "C132") (pin "2") (pinfunction "2_2") (pintype "input"))
      (node (ref "C133") (pin "2") (pinfunction "2_2") (pintype "input"))
      (node (ref "C136") (pin "1") (pinfunction "1_1") (pintype "input"))
      (node (ref "C139") (pin "2") (pinfunction "2_2") (pintype "input"))
      (node (ref "C3") (pin "1") (pinfunction "1_1") (pintype "input"))
      (node (ref "C4") (pin "1") (pinfunction "1_1") (pintype "input"))
      (node (ref "C6") (pin "2") (pinfunction "2_2") (pintype "input"))
      (node (ref "C9") (pin "1") (pinfunction "1_1") (pintype "input"))
      (node (ref "H21") (pin "2") (pinfunction "2_2") (pintype "input"))
      (node (ref "JP1") (pin "1") (pinfunction "1_1") (pintype "bidirectional"))
      (node (ref "JP3") (pin "2") (pinfunction "2_2") (pintype "bidirectional"))
      (node (ref "P1") (pin "1") (pinfunction "1_1") (pintype "unspecified"))
      (node (ref "P2") (pin "2") (pinfunction "2_2") (pintype "unspecified"))
      (node (ref "QU1") (pin "1") (pinfunction "IOVDD_1") (pintype "bidirectional"))
      (node (ref "QU1") (pin "10") (pinfunction "IOVDD_10") (pintype "bidirectional"))
      (node (ref "QU1") (pin "22") (pinfunction "IOVDD_22") (pintype "bidirectional"))
      (node (ref "QU1") (pin "33") (pinfunction "IOVDD_33") (pintype "bidirectional"))
      (node (ref "QU1") (pin "42") (pinfunction "IOVDD_42") (pintype "bidirectional"))
      (node (ref "QU1") (pin "43") (pinfunction "ADC_AVDD_43") (pintype "bidirectional"))
      (node (ref "QU1") (pin "44") (pinfunction "VREG_IN_44") (pintype "bidirectional"))
      (node (ref "QU1") (pin "48") (pinfunction "USB_VDD_48") (pintype "bidirectional"))
      (node (ref "QU1") (pin "49") (pinfunction "IOVDD_49") (pintype "bidirectional"))
      (node (ref "QU2") (pin "8") (pinfunction "VCC_8") (pintype "unspecified"))
      (node (ref "R14") (pin "1") (pinfunction "1_1") (pintype "input"))
      (node (ref "R15") (pin "1") (pinfunction "1_1") (pintype "input"))
      (node (ref "R18") (pin "2") (pinfunction "2_2") (pintype "input"))
      (node (ref "R2") (pin "2") (pinfunction "2_2") (pintype "unspecified"))
      (node (ref "R20") (pin "2") (pinfunction "2_2") (pintype "input"))
      (node (ref "R21") (pin "2") (pinfunction "2_2") (pintype "input"))
      (node (ref "R22") (pin "2") (pinfunction "2_2") (pintype "input"))
      (node (ref "R24") (pin "2") (pinfunction "2_2") (pintype "input"))
      (node (ref "R25") (pin "1") (pinfunction "1_1") (pintype "unspecified"))
      (node (ref "R3") (pin "1") (pinfunction "1_1") (pintype "unspecified"))
      (node (ref "R4") (pin "1") (pinfunction "1_1") (pintype "unspecified"))
      (node (ref "R5") (pin "2") (pinfunction "2_2") (pintype "input"))
      (node (ref "R6") (pin "2") (pinfunction "2_2") (pintype "input"))
      (node (ref "R8") (pin "2") (pinfunction "2_2") (pintype "input"))
      (node (ref "U1") (pin "1") (pinfunction "VCC_1") (pintype "unspecified"))
      (node (ref "U10") (pin "1") (pinfunction "VCC_1") (pintype "unspecified"))
      (node (ref "U11") (pin "1") (pinfunction "VCC_1") (pintype "unspecified"))
      (node (ref "U2") (pin "2") (pinfunction "Out_2") (pintype "unspecified"))
      (node (ref "U3") (pin "10") (pinfunction "VDD_10") (pintype "unspecified"))
      (node (ref "U4") (pin "8") (pinfunction "VCC_8") (pintype "unspecified"))
      (node (ref "U5") (pin "8") (pinfunction "VCC_8") (pintype "unspecified"))
      (node (ref "U6") (pin "1") (pinfunction "VCC_1") (pintype "unspecified"))
      (node (ref "U7") (pin "6") (pinfunction "VCCB_6") (pintype "unspecified"))
      (node (ref "U8") (pin "1") (pinfunction "VCC_1") (pintype "unspecified"))
      (node (ref "U9") (pin "1") (pinfunction "VCC_1") (pintype "unspecified"))
    )
    (net (code "204") (name "XIN") (class "Default")
      (node (ref "C134") (pin "1") (pinfunction "1_1") (pintype "unspecified"))
      (node (ref "QU1") (pin "20") (pinfunction "XIN_20") (pintype "input"))
      (node (ref "QX1") (pin "1") (pinfunction "OSC1_1") (pintype "unspecified"))
    )
    (net (code "205") (name "XOUT") (class "Default")
      (node (ref "C135") (pin "2") (pinfunction "2_2") (pintype "unspecified"))
      (node (ref "QU1") (pin "21") (pinfunction "XOUT_21") (pintype "unspecified"))
      (node (ref "QX1") (pin "3") (pinfunction "OSC2_3") (pintype "unspecified"))
    )
    (net (code "206") (name "unconnected-(ESPFLASH-Pad1)") (class "Default")
      (node (ref "ESPFLASH") (pin "1") (pinfunction "1_1") (pintype "unspecified+no_connect"))
    )
    (net (code "207") (name "unconnected-(ESPRST-Pad4)") (class "Default")
      (node (ref "ESPRST") (pin "4") (pinfunction "4_4") (pintype "unspecified+no_connect"))
    )
    (net (code "208") (name "unconnected-(LED112-DOUT-Pad2)") (class "Default")
      (node (ref "LED112") (pin "2") (pinfunction "DOUT_2") (pintype "unspecified"))
    )
    (net (code "209") (name "unconnected-(PWRRST-Pad1)") (class "Default")
      (node (ref "PWRRST") (pin "1") (pinfunction "1_1") (pintype "unspecified+no_connect"))
    )
    (net (code "210") (name "unconnected-(PWRRST-Pad3)") (class "Default")
      (node (ref "PWRRST") (pin "3") (pinfunction "3_3") (pintype "unspecified+no_connect"))
    )
    (net (code "211") (name "unconnected-(QU2-EP-Pad9)") (class "Default")
      (node (ref "QU2") (pin "9") (pinfunction "EP_9") (pintype "unspecified"))
    )
    (net (code "212") (name "unconnected-(RPRST-Pad1)") (class "Default")
      (node (ref "RPRST") (pin "1") (pinfunction "1_1") (pintype "unspecified+no_connect"))
    )
    (net (code "213") (name "unconnected-(RPRST-Pad3)") (class "Default")
      (node (ref "RPRST") (pin "3") (pinfunction "3_3") (pintype "unspecified+no_connect"))
    )
    (net (code "214") (name "unconnected-(U1-EP-Pad7)") (class "Default")
      (node (ref "U1") (pin "7") (pinfunction "EP_7") (pintype "unspecified+no_connect"))
    )
    (net (code "215") (name "unconnected-(U2-TAB-Pad4)") (class "Default")
      (node (ref "U2") (pin "4") (pinfunction "TAB_4") (pintype "unspecified"))
    )
    (net (code "216") (name "unconnected-(U3-CLK-Pad8)") (class "Default")
      (node (ref "U3") (pin "8") (pinfunction "CLK_8") (pintype "unspecified+no_connect"))
    )
    (net (code "217") (name "unconnected-(U3-EP-Pad11)") (class "Default")
      (node (ref "U3") (pin "11") (pinfunction "EP_11") (pintype "unspecified+no_connect"))
    )
    (net (code "218") (name "unconnected-(U3-INTA#(CLK)-Pad9)") (class "Default")
      (node (ref "U3") (pin "9") (pinfunction "INTA#(CLK)_9") (pintype "unspecified+no_connect"))
    )
    (net (code "219") (name "unconnected-(U3-TS(CLK{slash}INTB)#-Pad4)") (class "Default")
      (node (ref "U3") (pin "4") (pinfunction "TS(CLK/INTB)#_4") (pintype "unspecified+no_connect"))
    )
    (net (code "220") (name "unconnected-(U4-E1-Pad1)") (class "Default")
      (node (ref "U4") (pin "1") (pinfunction "E1_1") (pintype "unspecified+no_connect"))
    )
    (net (code "221") (name "unconnected-(U4-E2-Pad2)") (class "Default")
      (node (ref "U4") (pin "2") (pinfunction "E2_2") (pintype "unspecified+no_connect"))
    )
    (net (code "222") (name "unconnected-(U4-E3-Pad3)") (class "Default")
      (node (ref "U4") (pin "3") (pinfunction "E3_3") (pintype "unspecified+no_connect"))
    )
    (net (code "223") (name "unconnected-(U4-WC#-Pad7)") (class "Default")
      (node (ref "U4") (pin "7") (pinfunction "WC#_7") (pintype "unspecified+no_connect"))
    )
    (net (code "224") (name "unconnected-(U5-ADC-Pad2)") (class "Default")
      (node (ref "U5") (pin "2") (pinfunction "ADC_2") (pintype "unspecified"))
    )
    (net (code "225") (name "unconnected-(U5-CS0-Pad17)") (class "Default")
      (node (ref "U5") (pin "17") (pinfunction "CS0_17") (pintype "unspecified"))
    )
    (net (code "226") (name "unconnected-(U5-GPIO4-Pad13)") (class "Default")
      (node (ref "U5") (pin "13") (pinfunction "GPIO4_13") (pintype "unspecified"))
    )
    (net (code "227") (name "unconnected-(U5-GPIO5-Pad14)") (class "Default")
      (node (ref "U5") (pin "14") (pinfunction "GPIO5_14") (pintype "unspecified"))
    )
    (net (code "228") (name "unconnected-(U5-GPIO9-Pad19)") (class "Default")
      (node (ref "U5") (pin "19") (pinfunction "GPIO9_19") (pintype "unspecified"))
    )
    (net (code "229") (name "unconnected-(U5-GPIO10-Pad20)") (class "Default")
      (node (ref "U5") (pin "20") (pinfunction "GPIO10_20") (pintype "unspecified"))
    )
    (net (code "230") (name "unconnected-(U5-GPIO12-Pad6)") (class "Default")
      (node (ref "U5") (pin "6") (pinfunction "GPIO12_6") (pintype "unspecified"))
    )
    (net (code "231") (name "unconnected-(U5-GPIO13-Pad7)") (class "Default")
      (node (ref "U5") (pin "7") (pinfunction "GPIO13_7") (pintype "unspecified"))
    )
    (net (code "232") (name "unconnected-(U5-GPIO14-Pad5)") (class "Default")
      (node (ref "U5") (pin "5") (pinfunction "GPIO14_5") (pintype "unspecified"))
    )
    (net (code "233") (name "unconnected-(U5-MISO-Pad18)") (class "Default")
      (node (ref "U5") (pin "18") (pinfunction "MISO_18") (pintype "unspecified"))
    )
    (net (code "234") (name "unconnected-(U5-MOSI-Pad21)") (class "Default")
      (node (ref "U5") (pin "21") (pinfunction "MOSI_21") (pintype "unspecified"))
    )
    (net (code "235") (name "unconnected-(U5-SCLK-Pad22)") (class "Default")
      (node (ref "U5") (pin "22") (pinfunction "SCLK_22") (pintype "unspecified"))
    )
    (net (code "236") (name "unconnected-(U6-INT#-Pad14)") (class "Default")
      (node (ref "U6") (pin "14") (pinfunction "INT#_14") (pintype "unspecified+no_connect"))
    )
    (net (code "237") (name "unconnected-(U6-P5-Pad11)") (class "Default")
      (node (ref "U6") (pin "11") (pinfunction "P5_11") (pintype "unspecified+no_connect"))
    )
    (net (code "238") (name "unconnected-(U6-P6-Pad12)") (class "Default")
      (node (ref "U6") (pin "12") (pinfunction "P6_12") (pintype "unspecified+no_connect"))
    )
    (net (code "239") (name "unconnected-(U12-ID-Pad5)") (class "Default")
      (node (ref "U12") (pin "5") (pinfunction "ID_5") (pintype "unspecified+no_connect"))
    )
    (net (code "240") (name "unconnected-(USB1-EH-Pad17)") (class "Default")
      (node (ref "USB1") (pin "17") (pinfunction "EH_17") (pintype "unspecified+no_connect"))
    )
    (net (code "241") (name "unconnected-(USB1-EH-Pad18)") (class "Default")
      (node (ref "USB1") (pin "18") (pinfunction "EH_18") (pintype "unspecified+no_connect"))
    )
    (net (code "242") (name "unconnected-(USB1-EH-Pad19)") (class "Default")
      (node (ref "USB1") (pin "19") (pinfunction "EH_19") (pintype "unspecified"))
    )
    (net (code "243") (name "unconnected-(USB1-EH-Pad20)") (class "Default")
      (node (ref "USB1") (pin "20") (pinfunction "EH_20") (pintype "unspecified"))
    )
    (net (code "244") (name "unconnected-(USB1-SBU1-PadA8)") (class "Default")
      (node (ref "USB1") (pin "A8") (pinfunction "SBU1_A8") (pintype "unspecified"))
    )
    (net (code "245") (name "unconnected-(USB1-SBU2-PadB8)") (class "Default")
      (node (ref "USB1") (pin "B8") (pinfunction "SBU2_B8") (pintype "unspecified"))
    )
    (net (code "246") (name "unconnected-(USB1-VBUS-PadA9)") (class "Default")
      (node (ref "USB1") (pin "A9") (pinfunction "VBUS_A9") (pintype "unspecified"))
    )
    (net (code "247") (name "unconnected-(USB1-VBUS-PadB4)") (class "Default")
      (node (ref "USB1") (pin "B4") (pinfunction "VBUS_B4") (pintype "unspecified"))
    )
  )
)
